# MAX2082_transceiver_V1_0.net
KiCad netlist of a schematic drawn in Altium Designer
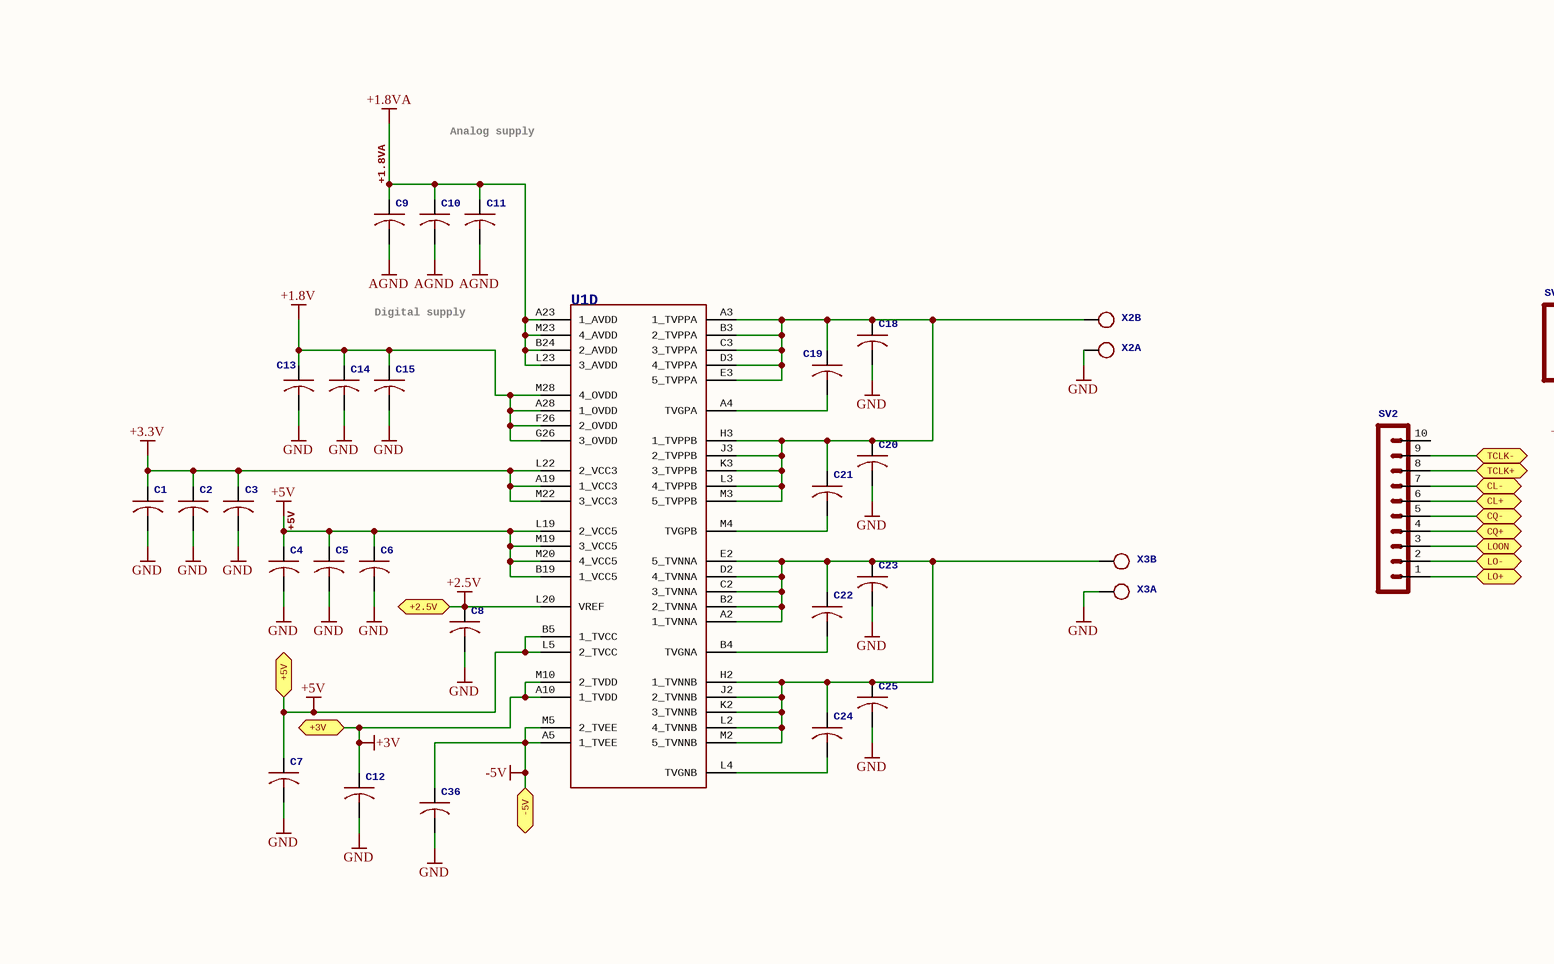
[diagram p0: MAX2082_transceiver_V1.0.SchDoc, top column 1 of 4]
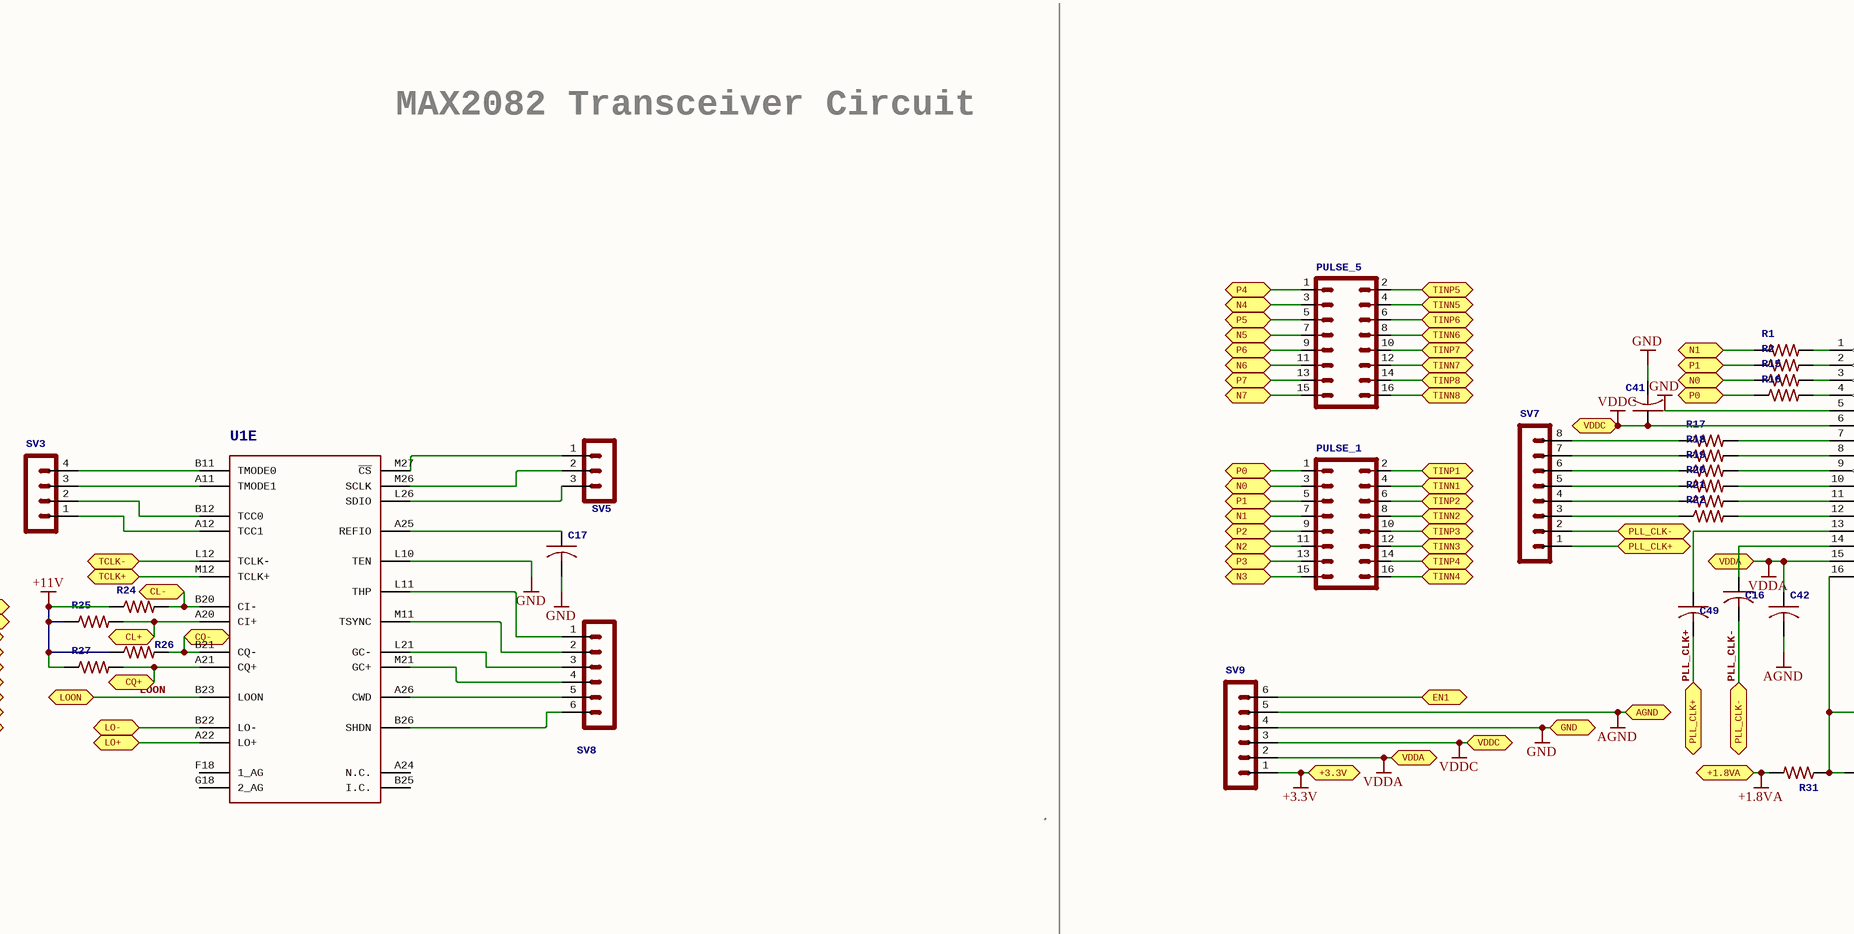
[diagram p1: MAX2082_transceiver_V1.0.SchDoc, top column 2 of 4]
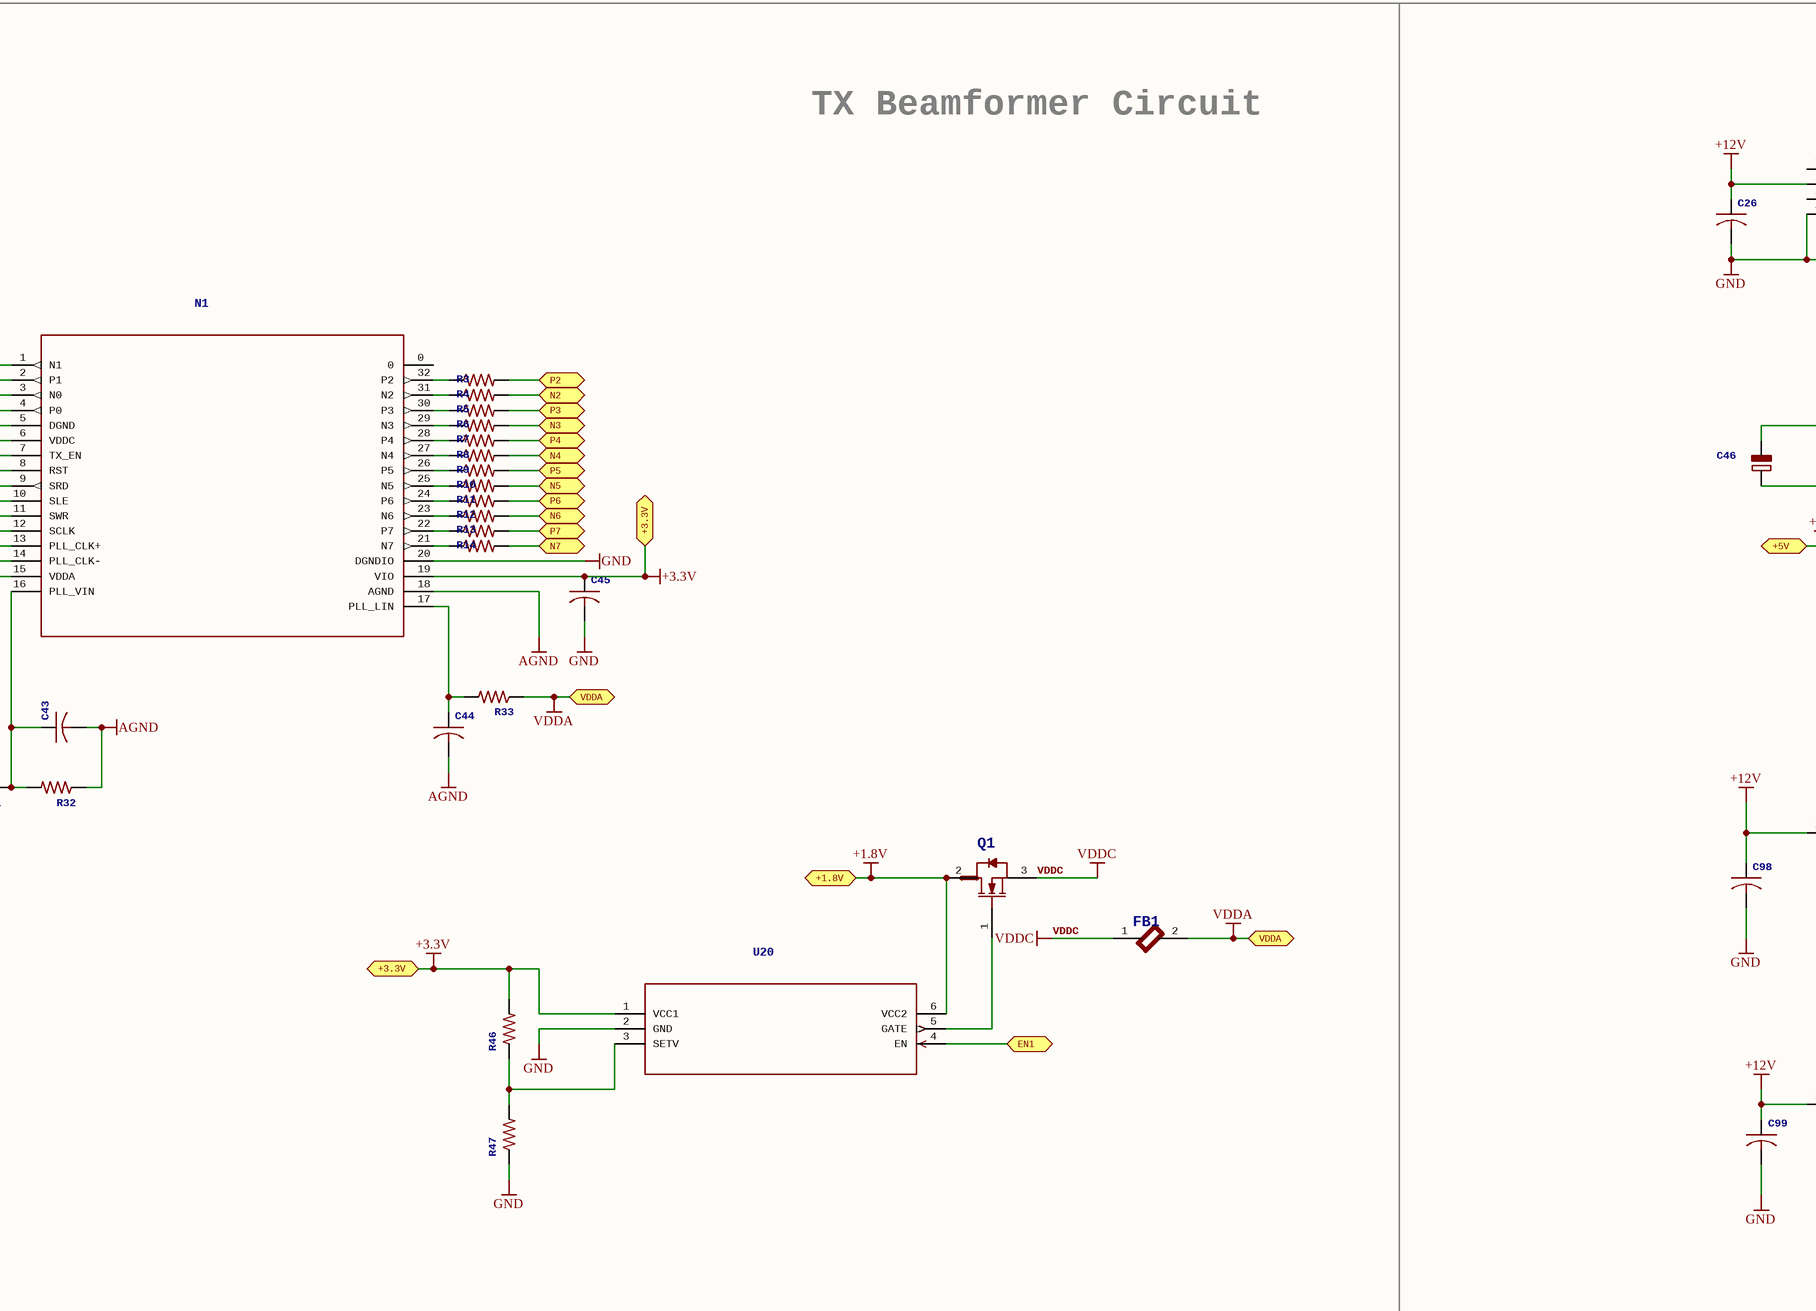
[diagram p2: MAX2082_transceiver_V1.0.SchDoc, top column 3 of 4]
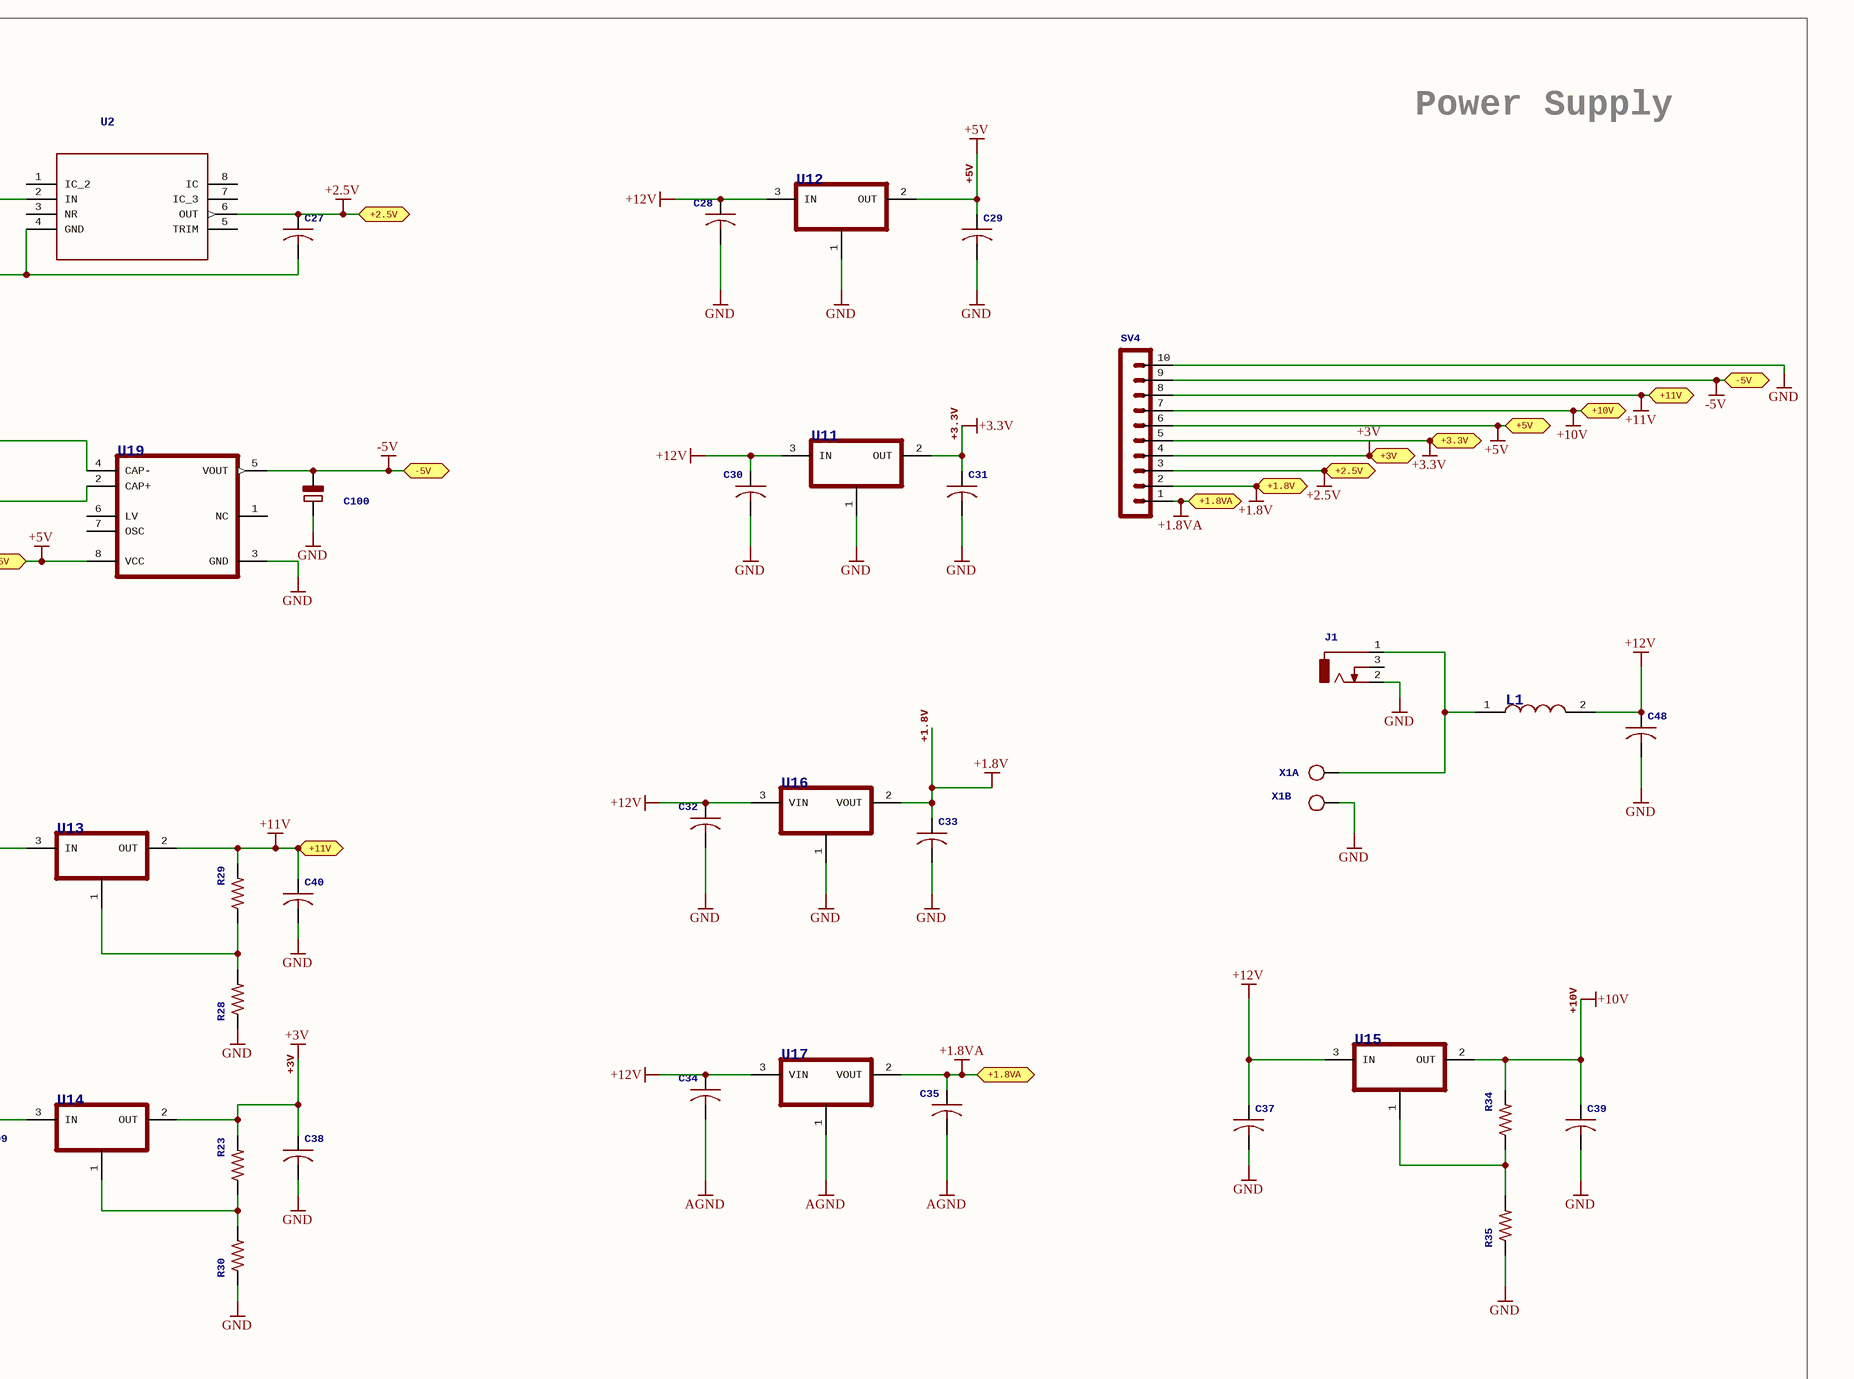
[diagram p3: MAX2082_transceiver_V1.0.SchDoc, top column 4 of 4]
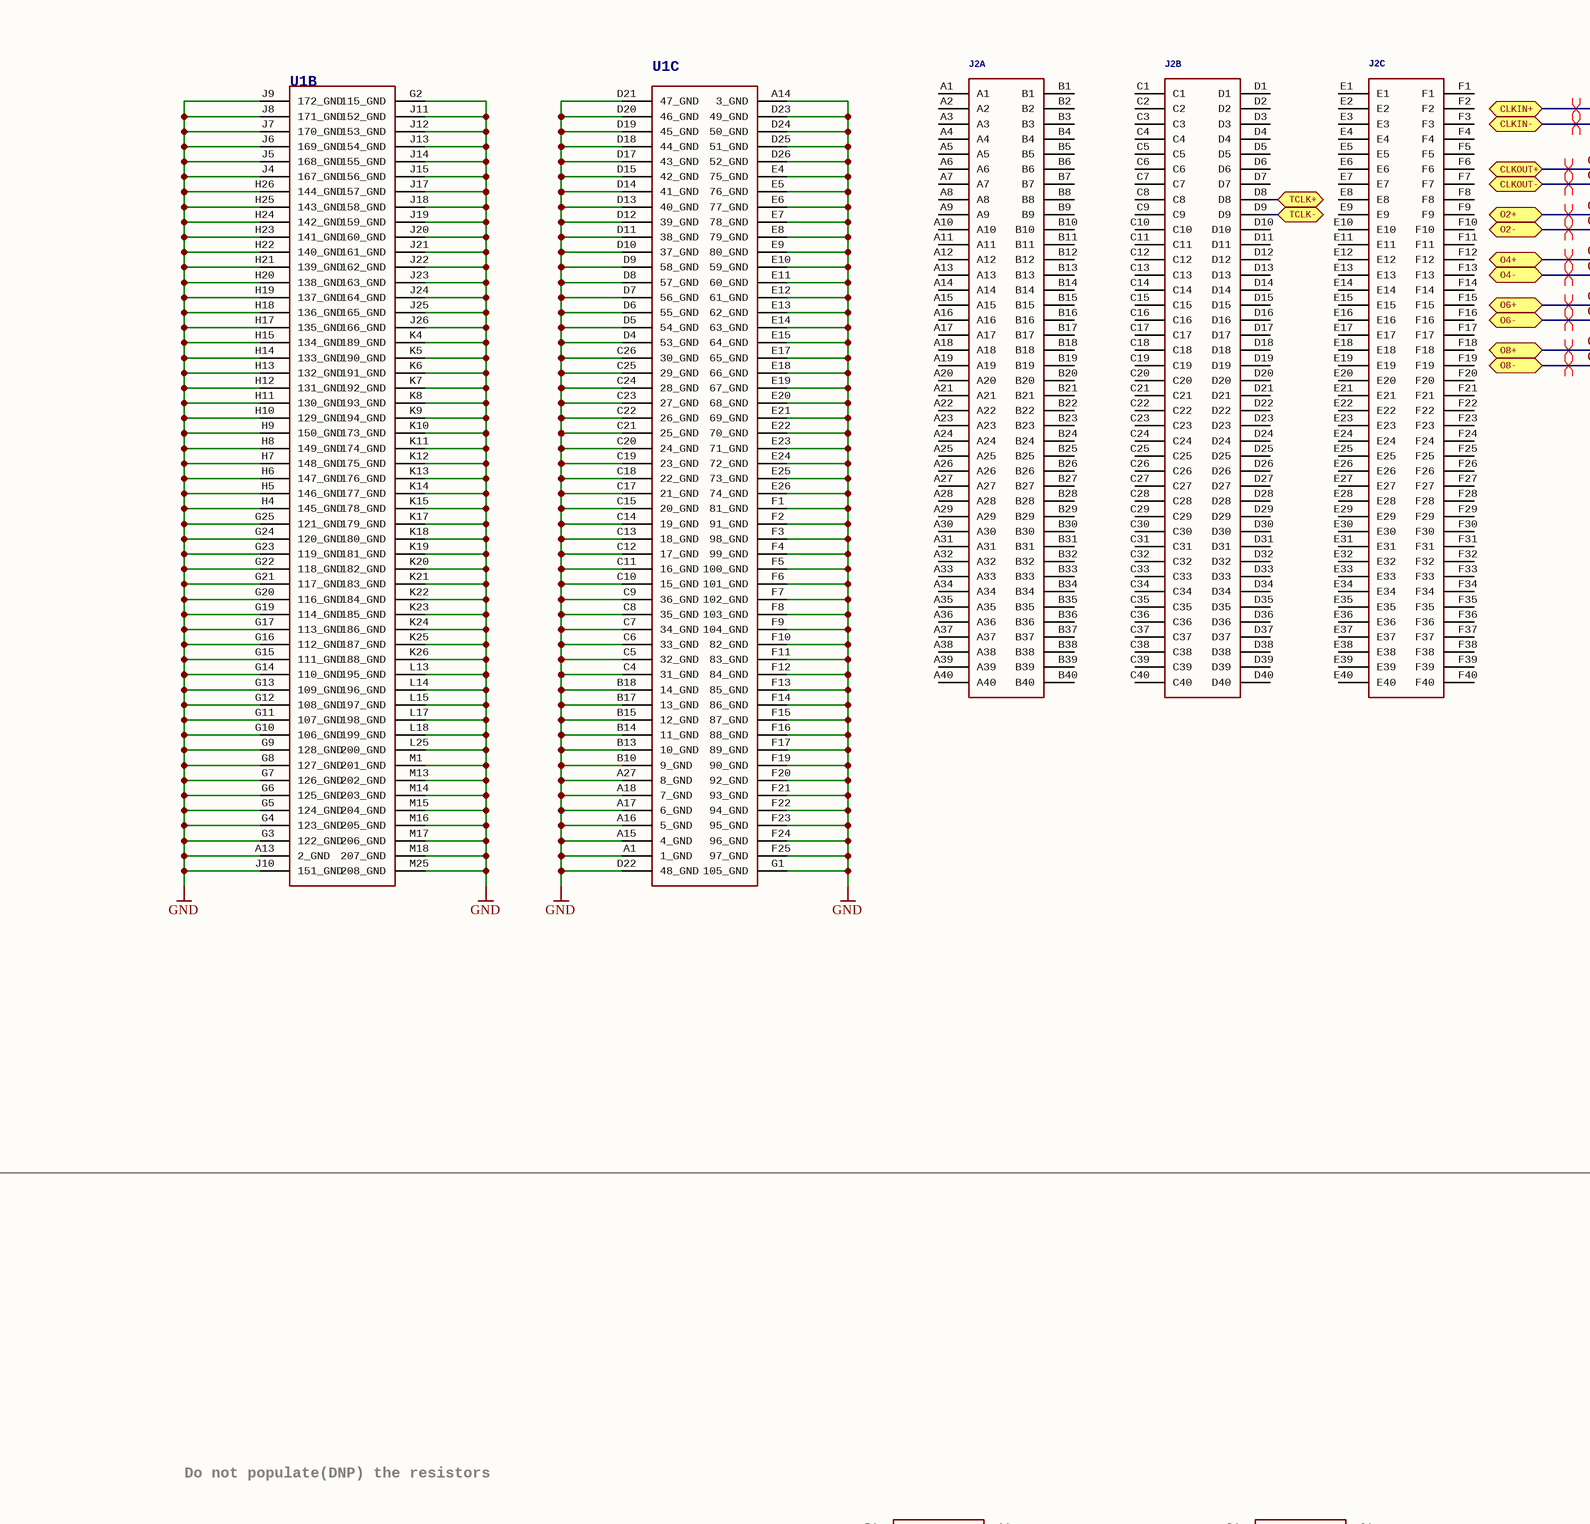
[diagram p4: MAX2082_transceiver_V1.0.SchDoc, centre column 1 of 4]
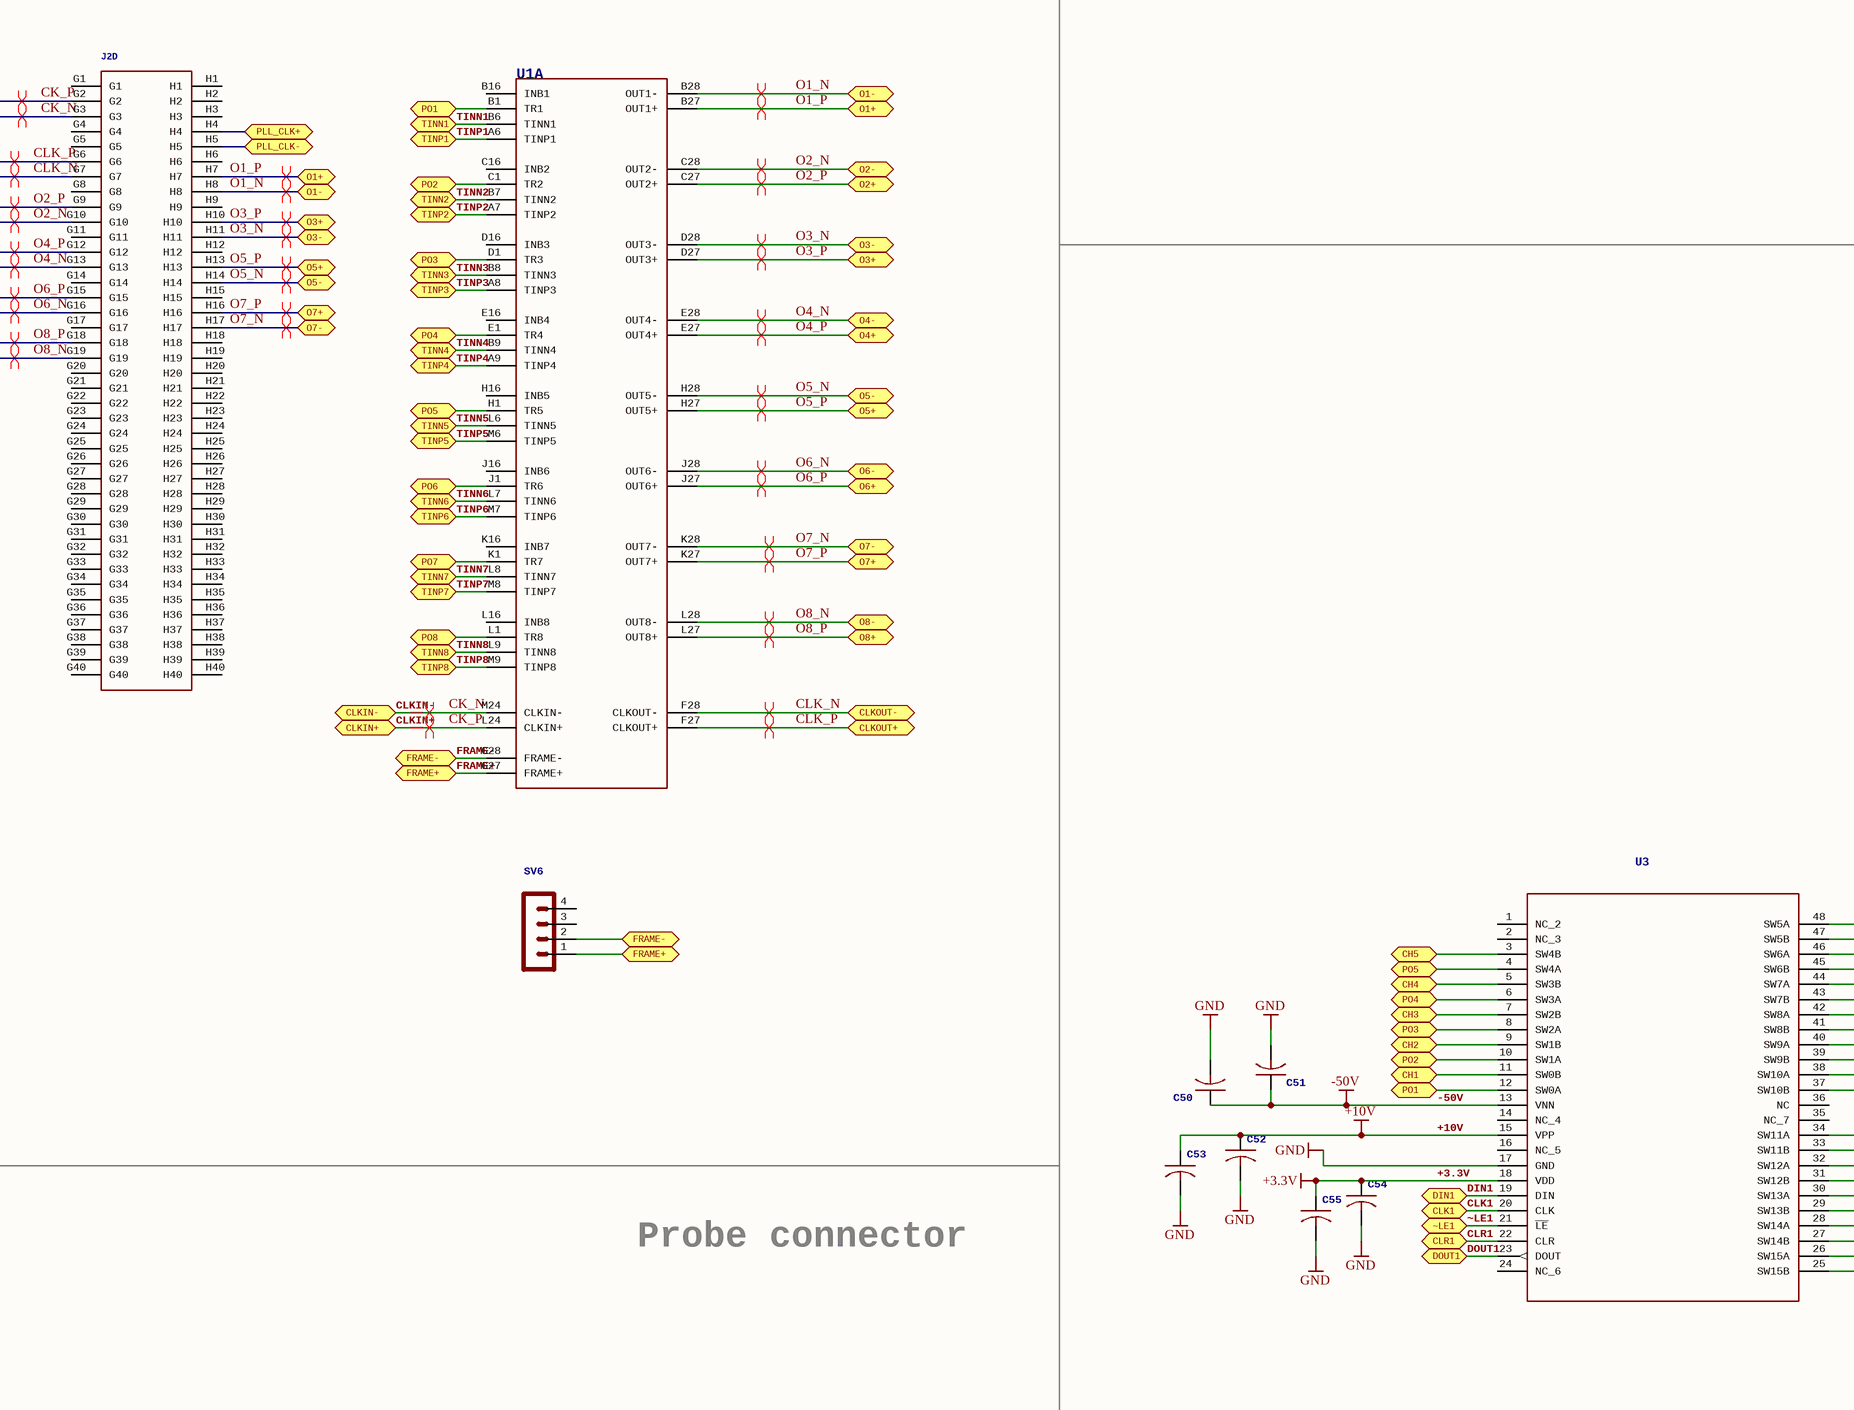
[diagram p5: MAX2082_transceiver_V1.0.SchDoc, centre column 2 of 4]
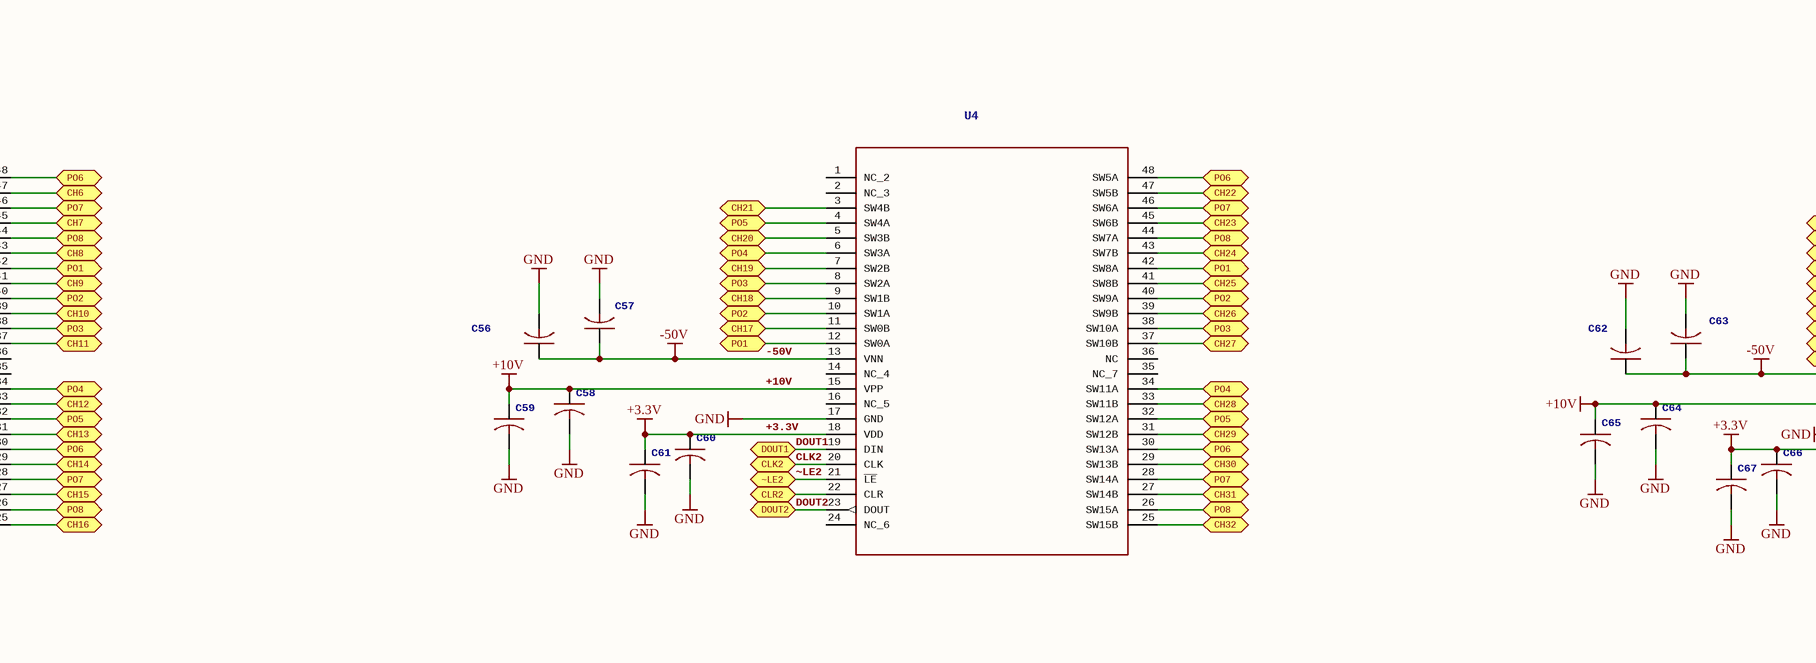
[diagram p6: MAX2082_transceiver_V1.0.SchDoc, centre column 3 of 4]
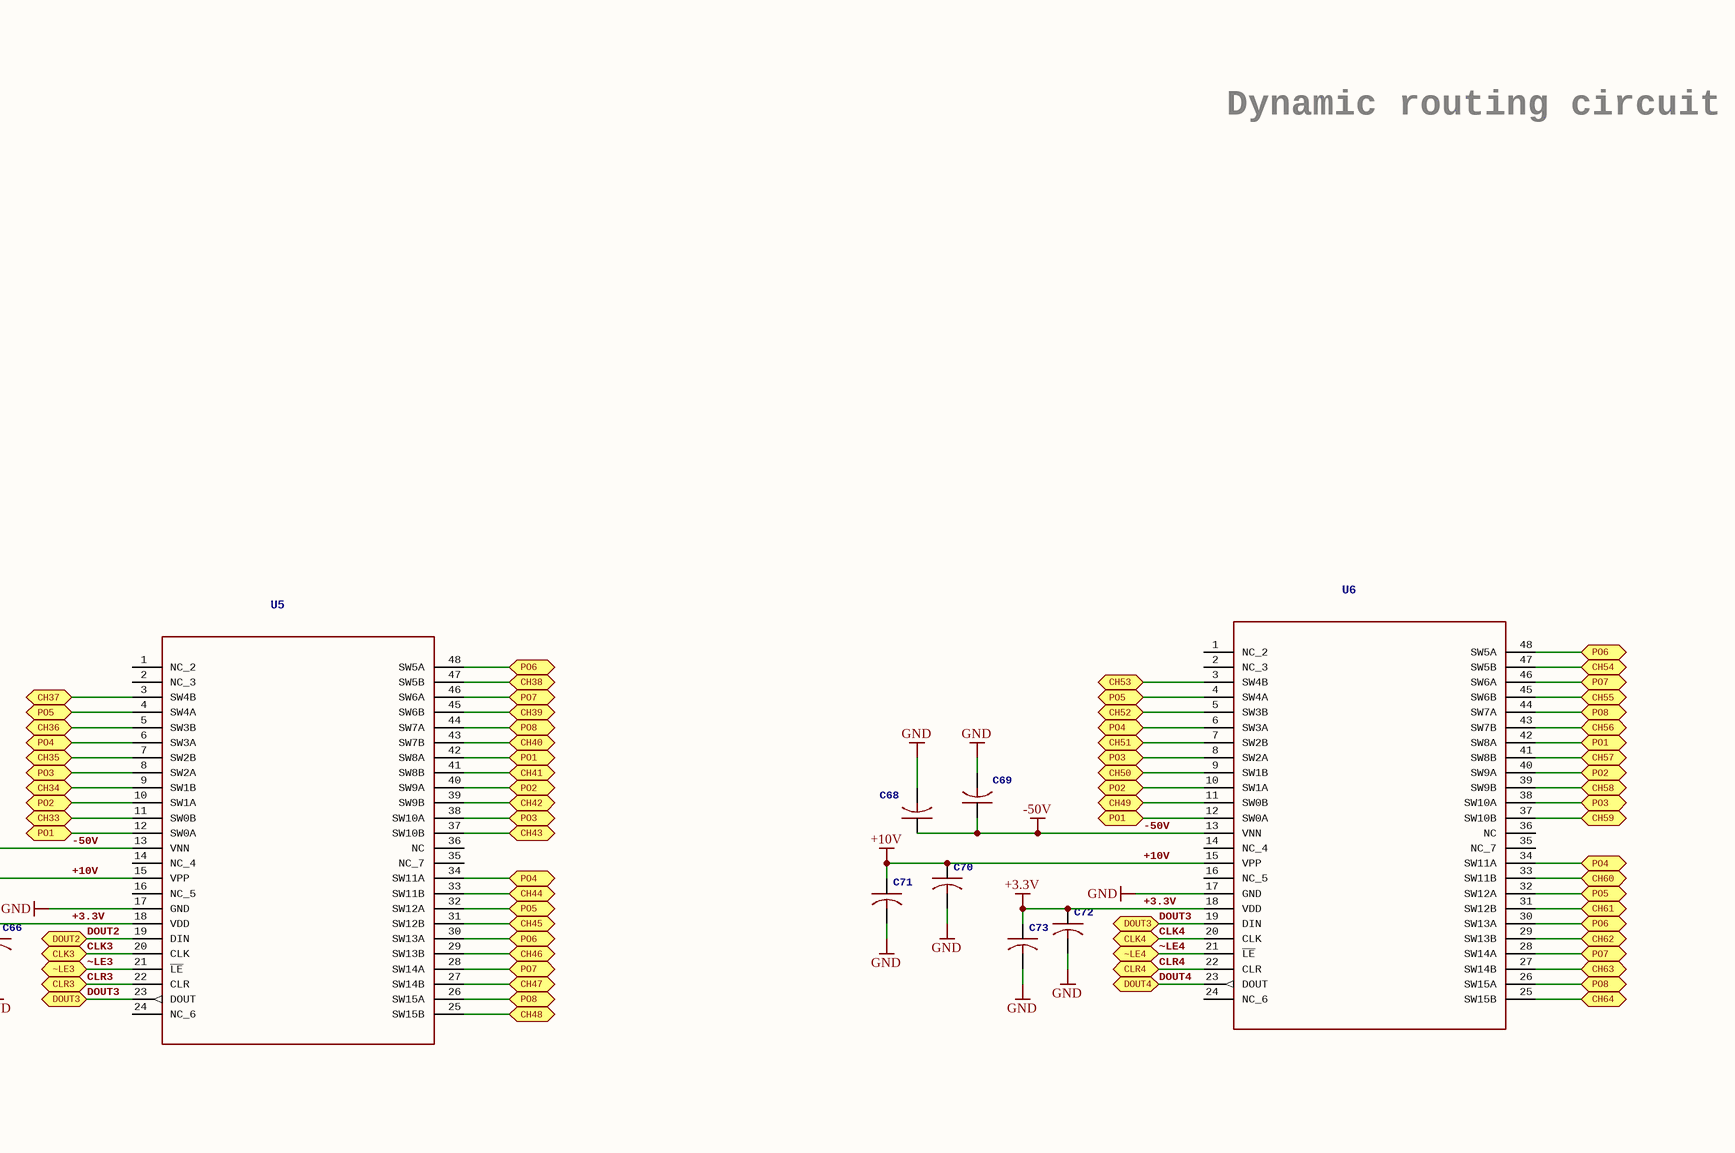
[diagram p7: MAX2082_transceiver_V1.0.SchDoc, centre column 4 of 4]
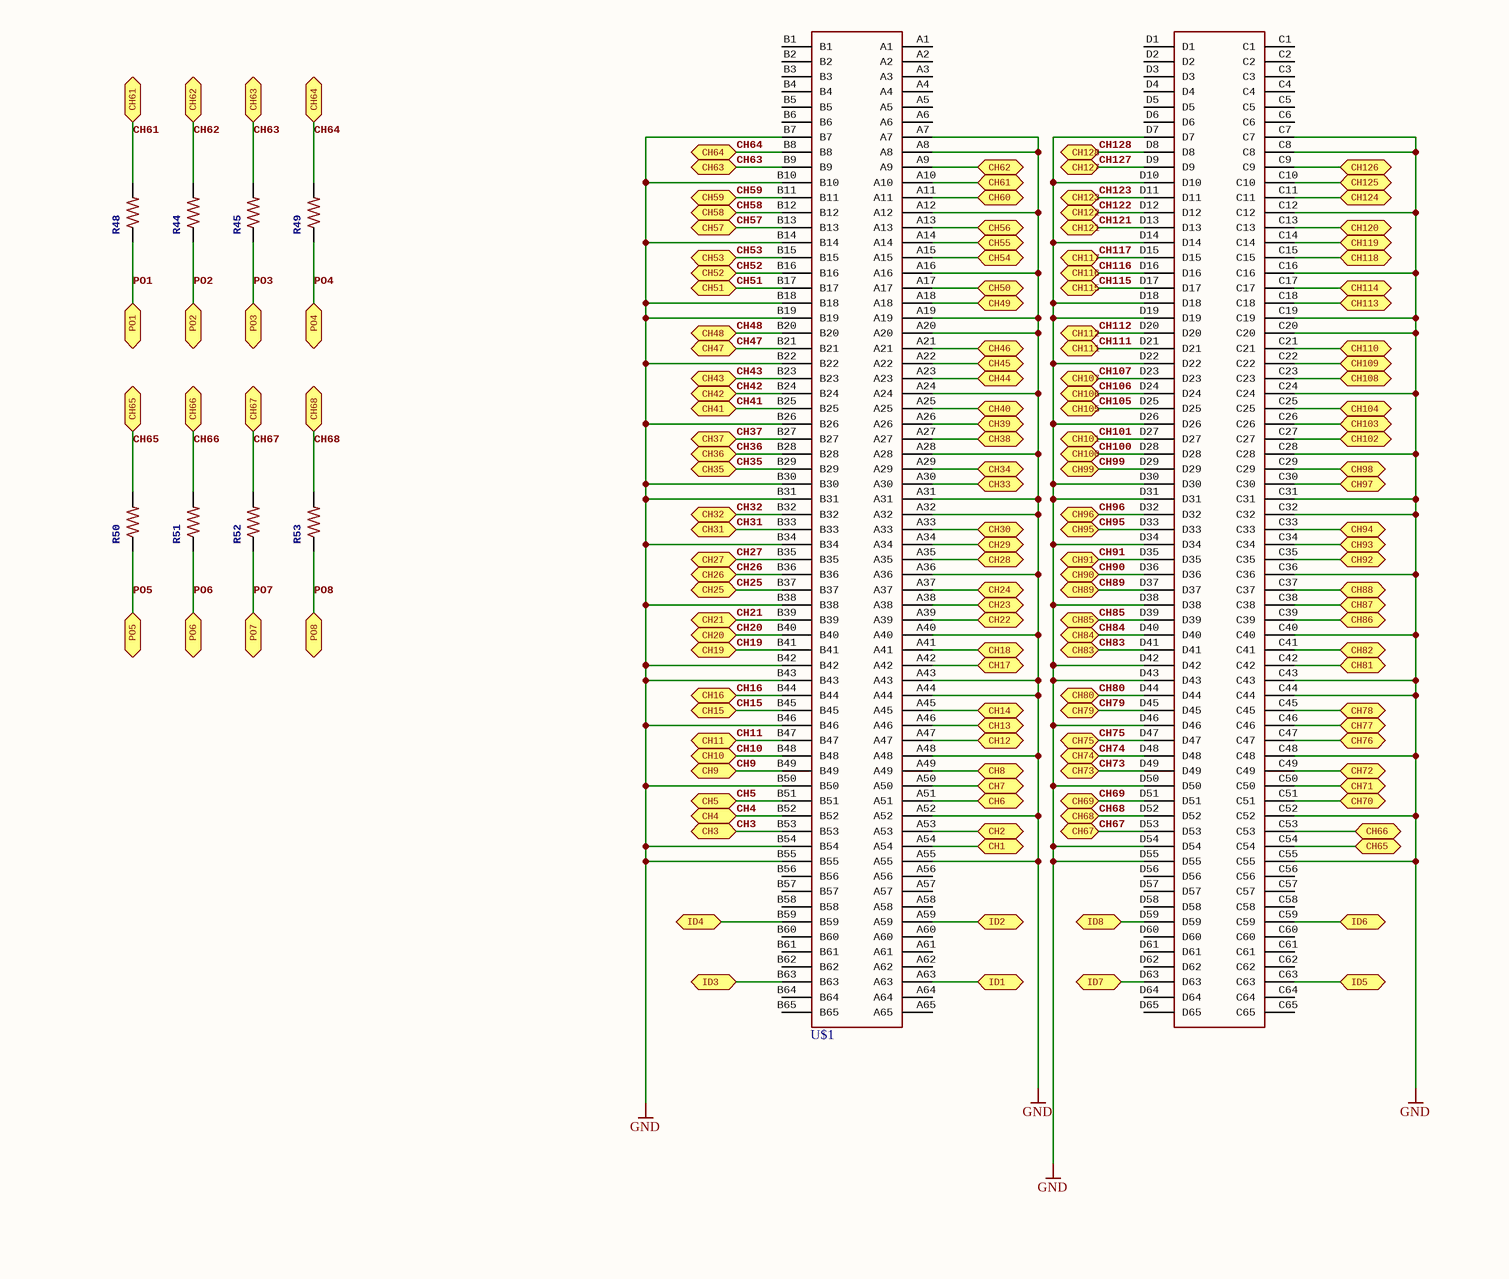
[diagram p8: MAX2082_transceiver_V1.0.SchDoc, bottom column 1 of 4]
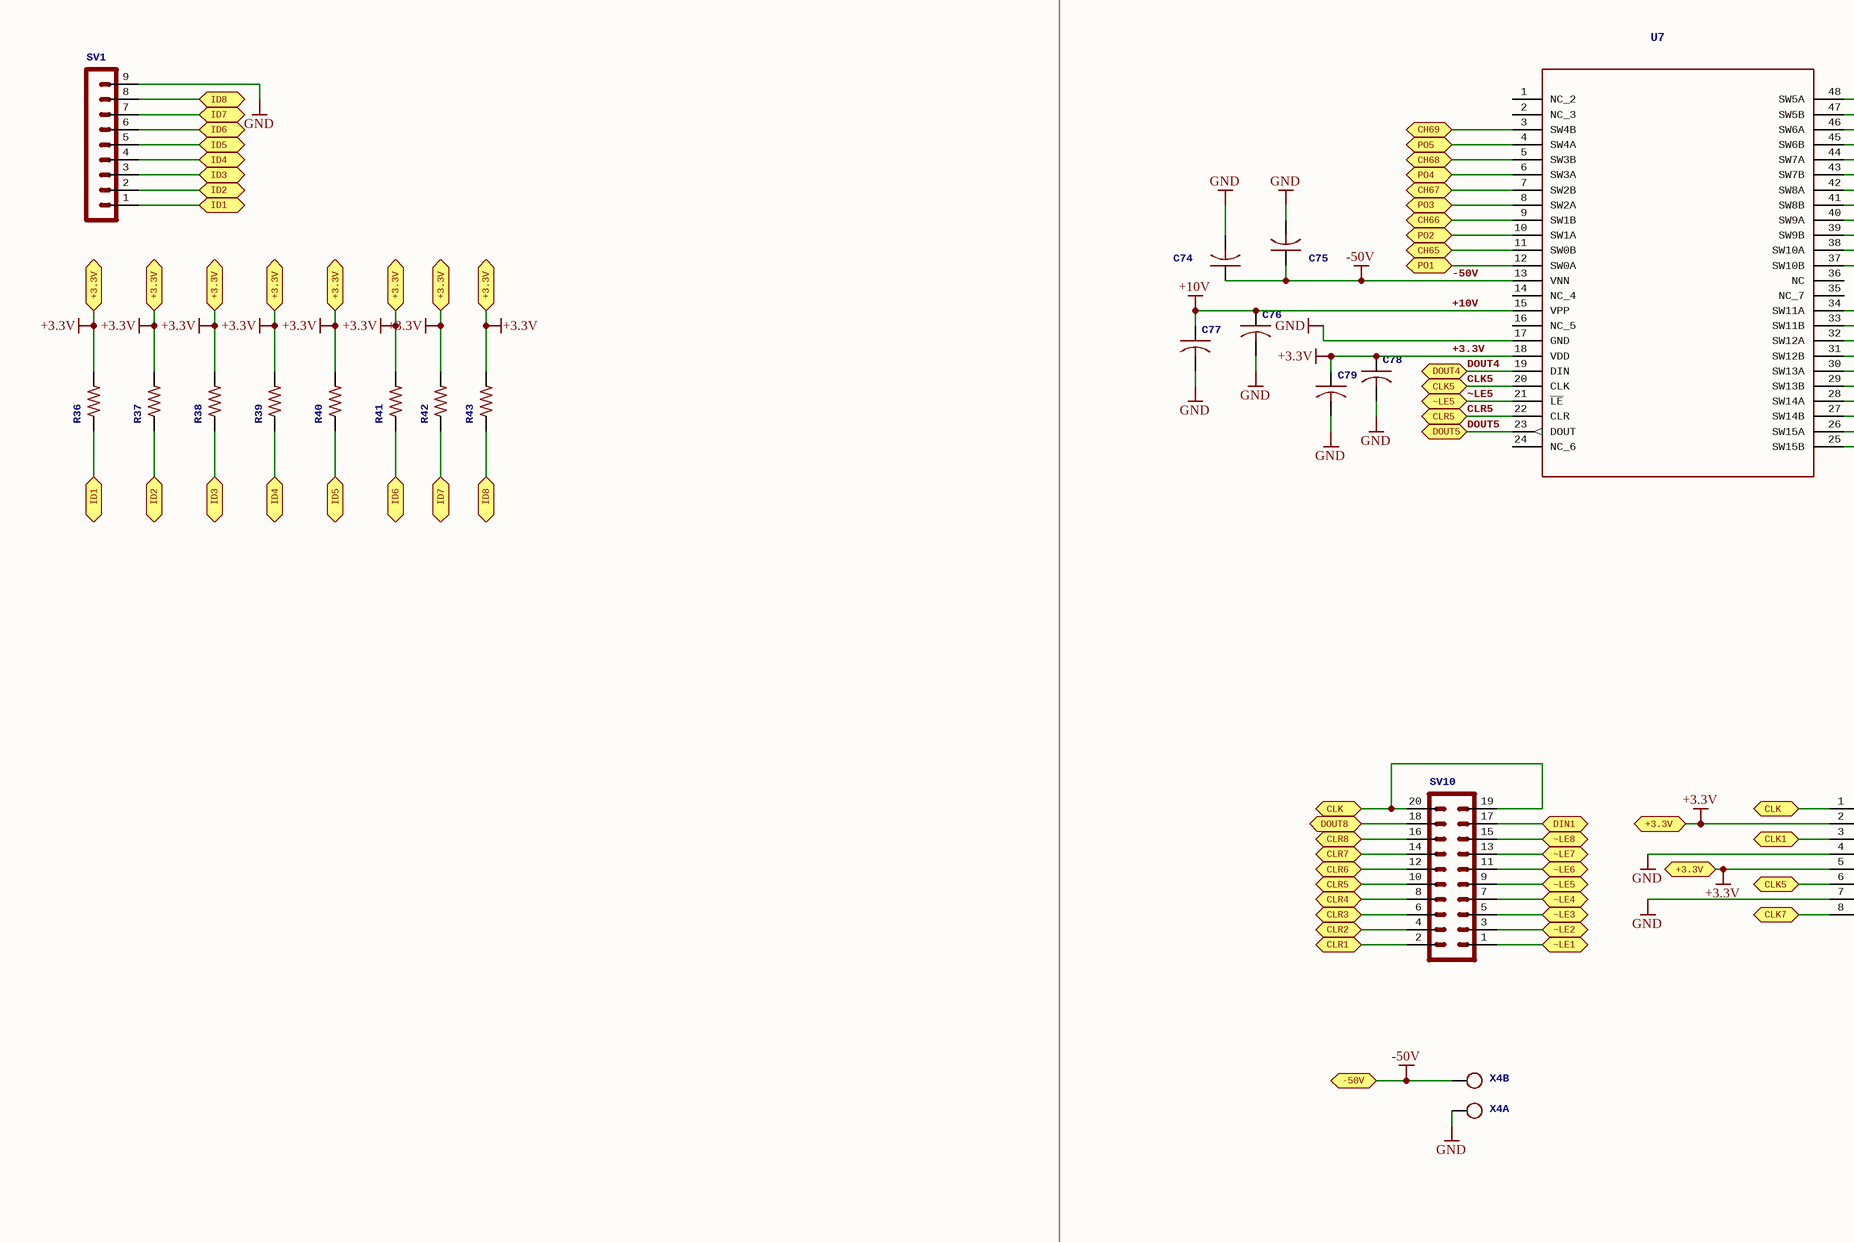
[diagram p9: MAX2082_transceiver_V1.0.SchDoc, bottom column 2 of 4]
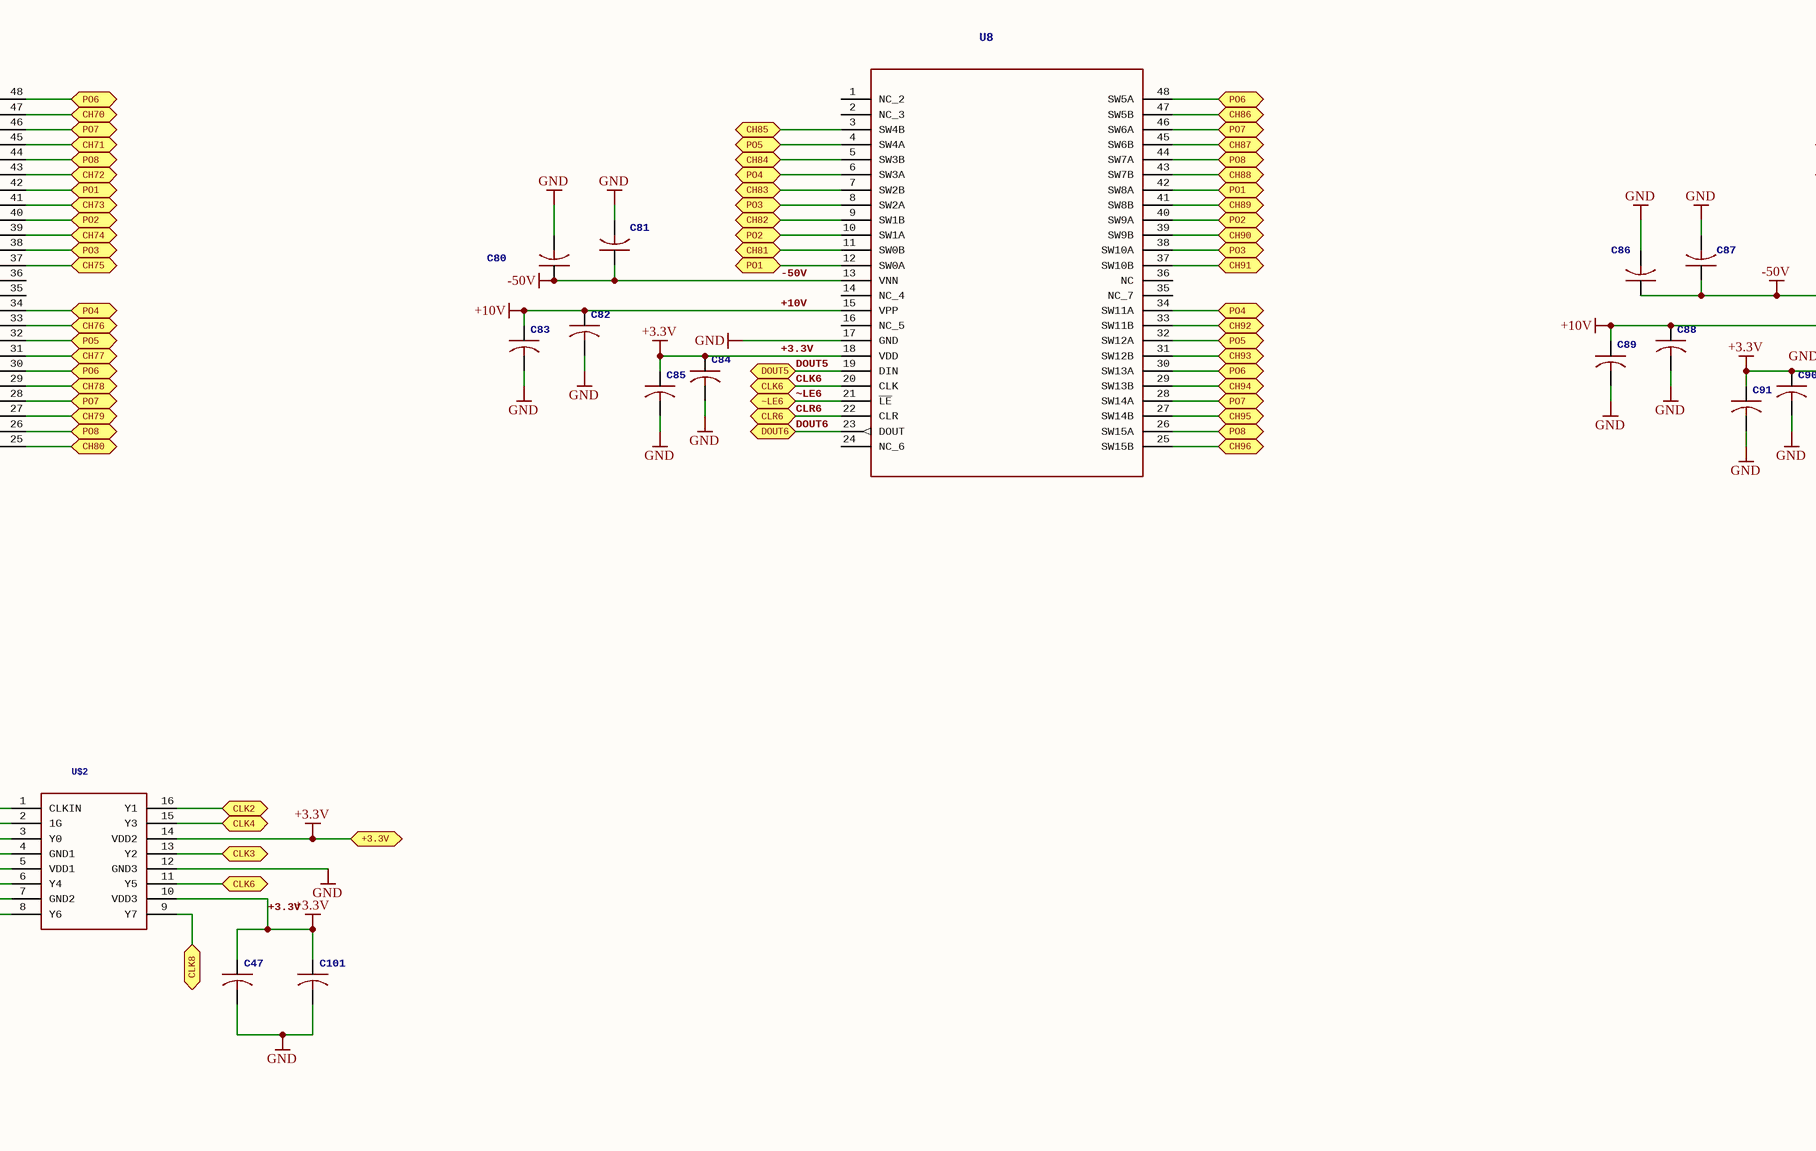
[diagram p10: MAX2082_transceiver_V1.0.SchDoc, bottom column 3 of 4]
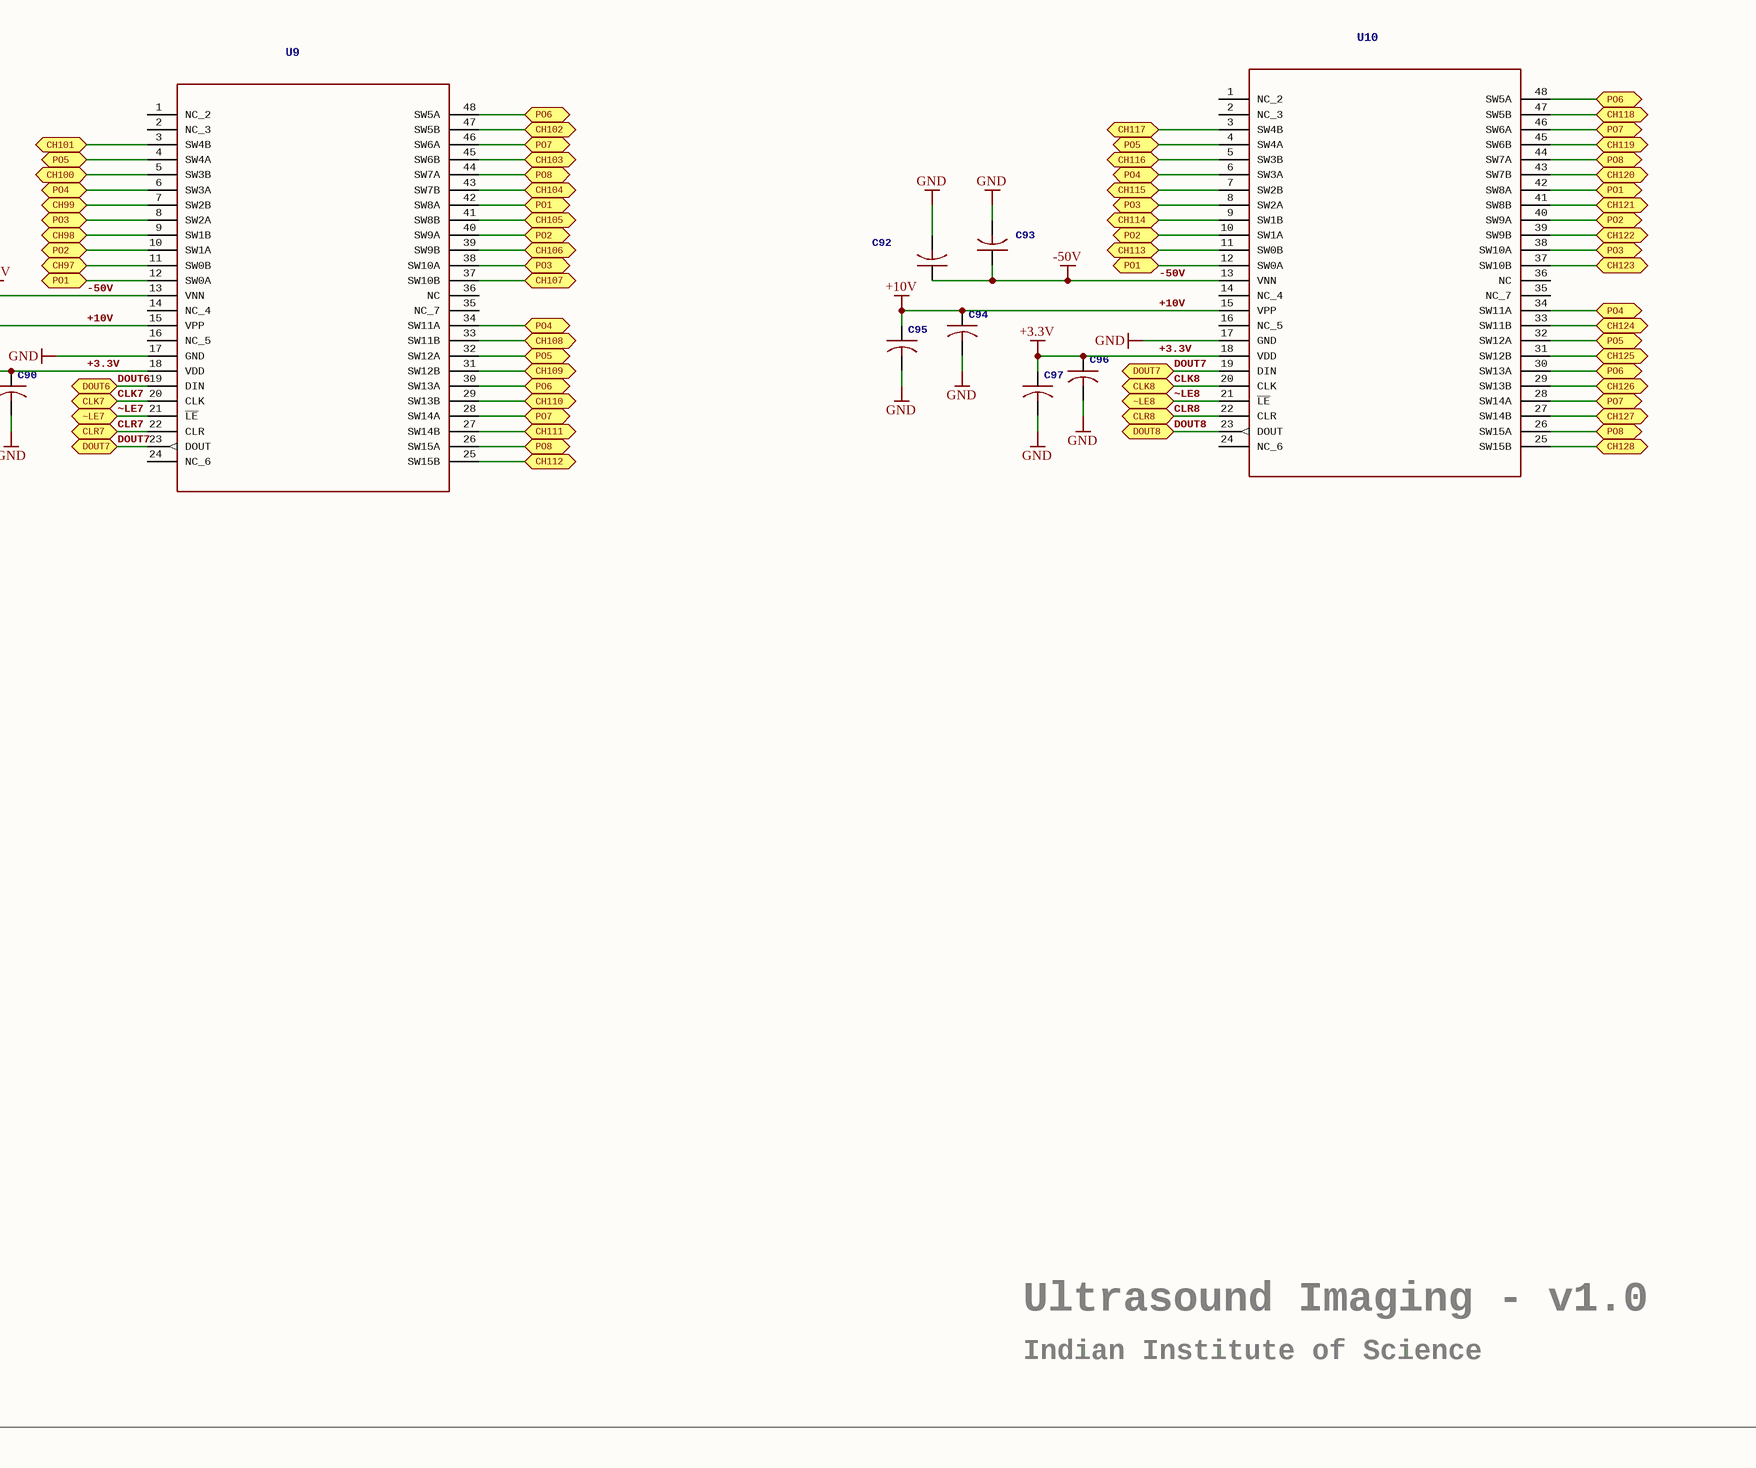
[diagram p11: MAX2082_transceiver_V1.0.SchDoc, bottom column 4 of 4]

(export (version "E")
  (design (tool "Eeschema 10.0.6"))
  (components
    (comp (ref "C1")
      (value "~")
      (footprint "C0805")
      (description "CAPACITOR, American symbol")
      (libsource (lib "rcl") (part "C-USC0805"))
    )
    (comp (ref "C2")
      (value "~")
      (footprint "C0805")
      (description "CAPACITOR, American symbol")
      (libsource (lib "rcl") (part "C-USC0805"))
    )
    (comp (ref "C3")
      (value "~")
      (footprint "C0805")
      (description "CAPACITOR, American symbol")
      (libsource (lib "rcl") (part "C-USC0805"))
    )
    (comp (ref "C4")
      (value "~")
      (footprint "C0805")
      (description "CAPACITOR, American symbol")
      (libsource (lib "rcl") (part "C-USC0805"))
    )
    (comp (ref "C5")
      (value "~")
      (footprint "C0805")
      (description "CAPACITOR, American symbol")
      (libsource (lib "rcl") (part "C-USC0805"))
    )
    (comp (ref "C6")
      (value "~")
      (footprint "C0805")
      (description "CAPACITOR, American symbol")
      (libsource (lib "rcl") (part "C-USC0805"))
    )
    (comp (ref "C7")
      (value "~")
      (footprint "C0805")
      (description "CAPACITOR, American symbol")
      (libsource (lib "rcl") (part "C-USC0805"))
    )
    (comp (ref "C8")
      (value "~")
      (footprint "C0805")
      (description "CAPACITOR, American symbol")
      (libsource (lib "rcl") (part "C-USC0805"))
    )
    (comp (ref "C9")
      (value "~")
      (footprint "C0805")
      (description "CAPACITOR, American symbol")
      (libsource (lib "rcl") (part "C-USC0805"))
    )
    (comp (ref "C10")
      (value "~")
      (footprint "C0805")
      (description "CAPACITOR, American symbol")
      (libsource (lib "rcl") (part "C-USC0805"))
    )
    (comp (ref "C11")
      (value "~")
      (footprint "C0805")
      (description "CAPACITOR, American symbol")
      (libsource (lib "rcl") (part "C-USC0805"))
    )
    (comp (ref "C12")
      (value "~")
      (footprint "C0805")
      (description "CAPACITOR, American symbol")
      (libsource (lib "rcl") (part "C-USC0805"))
    )
    (comp (ref "C13")
      (value "~")
      (footprint "C0805")
      (description "CAPACITOR, American symbol")
      (libsource (lib "rcl") (part "C-USC0805"))
    )
    (comp (ref "C14")
      (value "~")
      (footprint "C0805")
      (description "CAPACITOR, American symbol")
      (libsource (lib "rcl") (part "C-USC0805"))
    )
    (comp (ref "C15")
      (value "~")
      (footprint "C0805")
      (description "CAPACITOR, American symbol")
      (libsource (lib "rcl") (part "C-USC0805"))
    )
    (comp (ref "C16")
      (value "~")
      (footprint "C0805")
      (description "CAPACITOR, American symbol")
      (libsource (lib "rcl") (part "C-USC0805"))
    )
    (comp (ref "C17")
      (value "~")
      (footprint "C0805")
      (description "CAPACITOR, American symbol")
      (libsource (lib "rcl") (part "C-USC0805"))
    )
    (comp (ref "C18")
      (value "~")
      (footprint "C0805")
      (description "CAPACITOR, American symbol")
      (libsource (lib "rcl") (part "C-USC0805"))
    )
    (comp (ref "C19")
      (value "~")
      (footprint "C0805")
      (description "CAPACITOR, American symbol")
      (libsource (lib "rcl") (part "C-USC0805"))
    )
    (comp (ref "C20")
      (value "~")
      (footprint "C0805")
      (description "CAPACITOR, American symbol")
      (libsource (lib "rcl") (part "C-USC0805"))
    )
    (comp (ref "C21")
      (value "~")
      (footprint "C0805")
      (description "CAPACITOR, American symbol")
      (libsource (lib "rcl") (part "C-USC0805"))
    )
    (comp (ref "C22")
      (value "~")
      (footprint "C0805")
      (description "CAPACITOR, American symbol")
      (libsource (lib "rcl") (part "C-USC0805"))
    )
    (comp (ref "C23")
      (value "~")
      (footprint "C0805")
      (description "CAPACITOR, American symbol")
      (libsource (lib "rcl") (part "C-USC0805"))
    )
    (comp (ref "C24")
      (value "~")
      (footprint "C0805")
      (description "CAPACITOR, American symbol")
      (libsource (lib "rcl") (part "C-USC0805"))
    )
    (comp (ref "C25")
      (value "~")
      (footprint "C0805")
      (description "CAPACITOR, American symbol")
      (libsource (lib "rcl") (part "C-USC0805"))
    )
    (comp (ref "C26")
      (value "~")
      (footprint "C0805")
      (description "CAPACITOR, American symbol")
      (libsource (lib "rcl") (part "C-USC0805"))
    )
    (comp (ref "C27")
      (value "~")
      (footprint "C0805")
      (description "CAPACITOR, American symbol")
      (libsource (lib "rcl") (part "C-USC0805"))
    )
    (comp (ref "C28")
      (value "~")
      (footprint "C0805")
      (description "CAPACITOR, American symbol")
      (libsource (lib "") (part "C-USC0805_1"))
    )
    (comp (ref "C29")
      (value "~")
      (footprint "C0805")
      (description "CAPACITOR, American symbol")
      (libsource (lib "rcl") (part "C-USC0805"))
    )
    (comp (ref "C30")
      (value "~")
      (footprint "C0805")
      (description "CAPACITOR, American symbol")
      (libsource (lib "") (part "C-USC0805_1"))
    )
    (comp (ref "C31")
      (value "~")
      (footprint "C0805")
      (description "CAPACITOR, American symbol")
      (libsource (lib "rcl") (part "C-USC0805"))
    )
    (comp (ref "C32")
      (value "~")
      (footprint "C0805")
      (description "CAPACITOR, American symbol")
      (libsource (lib "") (part "C-USC0805_1"))
    )
    (comp (ref "C33")
      (value "~")
      (footprint "C0805")
      (description "CAPACITOR, American symbol")
      (libsource (lib "rcl") (part "C-USC0805"))
    )
    (comp (ref "C34")
      (value "~")
      (footprint "C0805")
      (description "CAPACITOR, American symbol")
      (libsource (lib "") (part "C-USC0805_1"))
    )
    (comp (ref "C35")
      (value "~")
      (footprint "C0805")
      (description "CAPACITOR, American symbol")
      (libsource (lib "") (part "C-USC0805_1"))
    )
    (comp (ref "C36")
      (value "~")
      (footprint "C0805")
      (description "CAPACITOR, American symbol")
      (libsource (lib "rcl") (part "C-USC0805"))
    )
    (comp (ref "C37")
      (value "~")
      (footprint "C0805")
      (description "CAPACITOR, American symbol")
      (libsource (lib "rcl") (part "C-USC0805"))
    )
    (comp (ref "C38")
      (value "~")
      (footprint "C0805")
      (description "CAPACITOR, American symbol")
      (libsource (lib "rcl") (part "C-USC0805"))
    )
    (comp (ref "C39")
      (value "~")
      (footprint "C0805")
      (description "CAPACITOR, American symbol")
      (libsource (lib "rcl") (part "C-USC0805"))
    )
    (comp (ref "C40")
      (value "~")
      (footprint "C0805")
      (description "CAPACITOR, American symbol")
      (libsource (lib "rcl") (part "C-USC0805"))
    )
    (comp (ref "C41")
      (value "~")
      (footprint "C0805")
      (description "CAPACITOR, American symbol")
      (libsource (lib "rcl") (part "C-USC0805"))
    )
    (comp (ref "C42")
      (value "~")
      (footprint "C0805")
      (description "CAPACITOR, American symbol")
      (libsource (lib "rcl") (part "C-USC0805"))
    )
    (comp (ref "C43")
      (value "~")
      (footprint "C0805")
      (description "CAPACITOR, American symbol")
      (libsource (lib "rcl") (part "C-USC0805"))
    )
    (comp (ref "C44")
      (value "~")
      (footprint "C0805")
      (description "CAPACITOR, American symbol")
      (libsource (lib "rcl") (part "C-USC0805"))
    )
    (comp (ref "C45")
      (value "~")
      (footprint "C0805")
      (description "CAPACITOR, American symbol")
      (libsource (lib "rcl") (part "C-USC0805"))
    )
    (comp (ref "C46")
      (value "~")
      (footprint "C46,C100")
      (description "POLARIZED CAPACITOR, European symbol")
      (libsource (lib "rcl") (part "CPOL-EUE2.5-6"))
    )
    (comp (ref "C47")
      (value "~")
      (footprint "C0805")
      (description "CAPACITOR, American symbol")
      (libsource (lib "rcl") (part "C-USC0805"))
    )
    (comp (ref "C48")
      (value "~")
      (footprint "C0805")
      (description "CAPACITOR, American symbol")
      (libsource (lib "rcl") (part "C-USC0805"))
    )
    (comp (ref "C49")
      (value "~")
      (footprint "C0805")
      (description "CAPACITOR, American symbol")
      (libsource (lib "rcl") (part "C-USC0805"))
    )
    (comp (ref "C50")
      (value "~")
      (footprint "C0805")
      (description "CAPACITOR, American symbol")
      (libsource (lib "rcl") (part "C-USC0805"))
    )
    (comp (ref "C51")
      (value "~")
      (footprint "C0805")
      (description "CAPACITOR, American symbol")
      (libsource (lib "rcl") (part "C-USC0805"))
    )
    (comp (ref "C52")
      (value "~")
      (footprint "C0805")
      (description "CAPACITOR, American symbol")
      (libsource (lib "rcl") (part "C-USC0805"))
    )
    (comp (ref "C53")
      (value "~")
      (footprint "C0805")
      (description "CAPACITOR, American symbol")
      (libsource (lib "rcl") (part "C-USC0805"))
    )
    (comp (ref "C54")
      (value "~")
      (footprint "C0805")
      (description "CAPACITOR, American symbol")
      (libsource (lib "rcl") (part "C-USC0805"))
    )
    (comp (ref "C55")
      (value "~")
      (footprint "C0805")
      (description "CAPACITOR, American symbol")
      (libsource (lib "rcl") (part "C-USC0805"))
    )
    (comp (ref "C56")
      (value "~")
      (footprint "C0805")
      (description "CAPACITOR, American symbol")
      (libsource (lib "rcl") (part "C-USC0805"))
    )
    (comp (ref "C57")
      (value "~")
      (footprint "C0805")
      (description "CAPACITOR, American symbol")
      (libsource (lib "rcl") (part "C-USC0805"))
    )
    (comp (ref "C58")
      (value "~")
      (footprint "C0805")
      (description "CAPACITOR, American symbol")
      (libsource (lib "rcl") (part "C-USC0805"))
    )
    (comp (ref "C59")
      (value "~")
      (footprint "C0805")
      (description "CAPACITOR, American symbol")
      (libsource (lib "rcl") (part "C-USC0805"))
    )
    (comp (ref "C60")
      (value "~")
      (footprint "C0805")
      (description "CAPACITOR, American symbol")
      (libsource (lib "rcl") (part "C-USC0805"))
    )
    (comp (ref "C61")
      (value "~")
      (footprint "C0805")
      (description "CAPACITOR, American symbol")
      (libsource (lib "rcl") (part "C-USC0805"))
    )
    (comp (ref "C62")
      (value "~")
      (footprint "C0805")
      (description "CAPACITOR, American symbol")
      (libsource (lib "rcl") (part "C-USC0805"))
    )
    (comp (ref "C63")
      (value "~")
      (footprint "C0805")
      (description "CAPACITOR, American symbol")
      (libsource (lib "rcl") (part "C-USC0805"))
    )
    (comp (ref "C64")
      (value "~")
      (footprint "C0805")
      (description "CAPACITOR, American symbol")
      (libsource (lib "rcl") (part "C-USC0805"))
    )
    (comp (ref "C65")
      (value "~")
      (footprint "C0805")
      (description "CAPACITOR, American symbol")
      (libsource (lib "rcl") (part "C-USC0805"))
    )
    (comp (ref "C66")
      (value "~")
      (footprint "C0805")
      (description "CAPACITOR, American symbol")
      (libsource (lib "rcl") (part "C-USC0805"))
    )
    (comp (ref "C67")
      (value "~")
      (footprint "C0805")
      (description "CAPACITOR, American symbol")
      (libsource (lib "rcl") (part "C-USC0805"))
    )
    (comp (ref "C68")
      (value "~")
      (footprint "C0805")
      (description "CAPACITOR, American symbol")
      (libsource (lib "rcl") (part "C-USC0805"))
    )
    (comp (ref "C69")
      (value "~")
      (footprint "C0805")
      (description "CAPACITOR, American symbol")
      (libsource (lib "rcl") (part "C-USC0805"))
    )
    (comp (ref "C70")
      (value "~")
      (footprint "C0805")
      (description "CAPACITOR, American symbol")
      (libsource (lib "rcl") (part "C-USC0805"))
    )
    (comp (ref "C71")
      (value "~")
      (footprint "C0805")
      (description "CAPACITOR, American symbol")
      (libsource (lib "rcl") (part "C-USC0805"))
    )
    (comp (ref "C72")
      (value "~")
      (footprint "C0805")
      (description "CAPACITOR, American symbol")
      (libsource (lib "rcl") (part "C-USC0805"))
    )
    (comp (ref "C73")
      (value "~")
      (footprint "C0805")
      (description "CAPACITOR, American symbol")
      (libsource (lib "rcl") (part "C-USC0805"))
    )
    (comp (ref "C74")
      (value "~")
      (footprint "C0805")
      (description "CAPACITOR, American symbol")
      (libsource (lib "rcl") (part "C-USC0805"))
    )
    (comp (ref "C75")
      (value "~")
      (footprint "C0805")
      (description "CAPACITOR, American symbol")
      (libsource (lib "rcl") (part "C-USC0805"))
    )
    (comp (ref "C76")
      (value "~")
      (footprint "C0805")
      (description "CAPACITOR, American symbol")
      (libsource (lib "rcl") (part "C-USC0805"))
    )
    (comp (ref "C77")
      (value "~")
      (footprint "C0805")
      (description "CAPACITOR, American symbol")
      (libsource (lib "rcl") (part "C-USC0805"))
    )
    (comp (ref "C78")
      (value "~")
      (footprint "C0805")
      (description "CAPACITOR, American symbol")
      (libsource (lib "rcl") (part "C-USC0805"))
    )
    (comp (ref "C79")
      (value "~")
      (footprint "C0805")
      (description "CAPACITOR, American symbol")
      (libsource (lib "rcl") (part "C-USC0805"))
    )
    (comp (ref "C80")
      (value "~")
      (footprint "C0805")
      (description "CAPACITOR, American symbol")
      (libsource (lib "rcl") (part "C-USC0805"))
    )
    (comp (ref "C81")
      (value "~")
      (footprint "C0805")
      (description "CAPACITOR, American symbol")
      (libsource (lib "rcl") (part "C-USC0805"))
    )
    (comp (ref "C82")
      (value "~")
      (footprint "C0805")
      (description "CAPACITOR, American symbol")
      (libsource (lib "rcl") (part "C-USC0805"))
    )
    (comp (ref "C83")
      (value "~")
      (footprint "C0805")
      (description "CAPACITOR, American symbol")
      (libsource (lib "rcl") (part "C-USC0805"))
    )
    (comp (ref "C84")
      (value "~")
      (footprint "C0805")
      (description "CAPACITOR, American symbol")
      (libsource (lib "rcl") (part "C-USC0805"))
    )
    (comp (ref "C85")
      (value "~")
      (footprint "C0805")
      (description "CAPACITOR, American symbol")
      (libsource (lib "rcl") (part "C-USC0805"))
    )
    (comp (ref "C86")
      (value "~")
      (footprint "C0805")
      (description "CAPACITOR, American symbol")
      (libsource (lib "rcl") (part "C-USC0805"))
    )
    (comp (ref "C87")
      (value "~")
      (footprint "C0805")
      (description "CAPACITOR, American symbol")
      (libsource (lib "rcl") (part "C-USC0805"))
    )
    (comp (ref "C88")
      (value "~")
      (footprint "C0805")
      (description "CAPACITOR, American symbol")
      (libsource (lib "rcl") (part "C-USC0805"))
    )
    (comp (ref "C89")
      (value "~")
      (footprint "C0805")
      (description "CAPACITOR, American symbol")
      (libsource (lib "rcl") (part "C-USC0805"))
    )
    (comp (ref "C90")
      (value "~")
      (footprint "C0805")
      (description "CAPACITOR, American symbol")
      (libsource (lib "rcl") (part "C-USC0805"))
    )
    (comp (ref "C91")
      (value "~")
      (footprint "C0805")
      (description "CAPACITOR, American symbol")
      (libsource (lib "rcl") (part "C-USC0805"))
    )
    (comp (ref "C92")
      (value "~")
      (footprint "C0805")
      (description "CAPACITOR, American symbol")
      (libsource (lib "rcl") (part "C-USC0805"))
    )
    (comp (ref "C93")
      (value "~")
      (footprint "C0805")
      (description "CAPACITOR, American symbol")
      (libsource (lib "rcl") (part "C-USC0805"))
    )
    (comp (ref "C94")
      (value "~")
      (footprint "C0805")
      (description "CAPACITOR, American symbol")
      (libsource (lib "rcl") (part "C-USC0805"))
    )
    (comp (ref "C95")
      (value "~")
      (footprint "C0805")
      (description "CAPACITOR, American symbol")
      (libsource (lib "rcl") (part "C-USC0805"))
    )
    (comp (ref "C96")
      (value "~")
      (footprint "C0805")
      (description "CAPACITOR, American symbol")
      (libsource (lib "rcl") (part "C-USC0805"))
    )
    (comp (ref "C97")
      (value "~")
      (footprint "C0805")
      (description "CAPACITOR, American symbol")
      (libsource (lib "rcl") (part "C-USC0805"))
    )
    (comp (ref "C98")
      (value "~")
      (footprint "C0805")
      (description "CAPACITOR, American symbol")
      (libsource (lib "rcl") (part "C-USC0805"))
    )
    (comp (ref "C99")
      (value "~")
      (footprint "C0805")
      (description "CAPACITOR, American symbol")
      (libsource (lib "rcl") (part "C-USC0805"))
    )
    (comp (ref "C100")
      (value "~")
      (footprint "C46,C100")
      (description "POLARIZED CAPACITOR, European symbol")
      (libsource (lib "rcl") (part "CPOL-EUE2.5-6"))
    )
    (comp (ref "C101")
      (value "~")
      (footprint "C0805")
      (description "CAPACITOR, American symbol")
      (libsource (lib "rcl") (part "C-USC0805"))
    )
    (comp (ref "FB1")
      (value "~")
      (footprint "FB1")
      (description "Chip bead for power line")
      (libsource (lib "TDK - MPZ1608S101ATAH0") (part "TDK_MPZ1608S101ATAH0TDK_MPZ1608S101ATAH0_0_0"))
    )
    (comp (ref "J1")
      (value "~")
      (footprint "J1")
      (description "DC POWER JACK   Source: DCJ0202.pdf")
      (libsource (lib "con-jack") (part "DCJ0202"))
    )
    (comp (ref "J2")
      (value "~")
      (footprint "J2")
      (description "Board-To-Board Connector, Vita 57 XMC, ASP Series, Surface Mount, Header, 400, 1.27 mm")
      (libsource (lib "ASP-134488-01") (part "ASP-134488-01"))
    )
    (comp (ref "L1")
      (value "~")
      (footprint "L1              0805")
      (description "PAS-IND-INDUCTOR-2")
      (libsource (lib "Wurth Electronics - 742792031") (part "WURTH_ELECTRONICS_742792031WURTH_ELECTRONICS_742792031_0_0"))
    )
    (comp (ref "N1") (value "~") (footprint "N1") (libsource (lib "LM96570") (part "LM96570SQE/NOPB")))
    (comp (ref "PULSE_1")
      (value "~")
      (footprint "PULSE_1,PULSE_5")
      (description "JUMPER")
      (libsource (lib "jumper") (part "JP8Q"))
    )
    (comp (ref "PULSE_5")
      (value "~")
      (footprint "PULSE_1,PULSE_5")
      (description "JUMPER")
      (libsource (lib "jumper") (part "JP8Q"))
    )
    (comp (ref "Q1")
      (value "~")
      (footprint "Q1               SOT-223")
      (description "ONSC-NMOS-G1D2S3D4-4")
      (libsource (lib "On Semiconductor - NTF3055L108T1G") (part "ON_SEMICONDUCTOR_NTF3055L108T1GON_SEMICONDUCTOR_NTF3055L108T1G_0_0"))
    )
    (comp (ref "R1")
      (value "~")
      (footprint "R0805")
      (description "RESISTOR, American symbol")
      (libsource (lib "rcl") (part "R-US_M0805"))
    )
    (comp (ref "R2")
      (value "~")
      (footprint "R0805")
      (description "RESISTOR, American symbol")
      (libsource (lib "rcl") (part "R-US_M0805"))
    )
    (comp (ref "R3")
      (value "~")
      (footprint "R0805")
      (description "RESISTOR, American symbol")
      (libsource (lib "rcl") (part "R-US_M0805"))
    )
    (comp (ref "R4")
      (value "~")
      (footprint "R0805")
      (description "RESISTOR, American symbol")
      (libsource (lib "rcl") (part "R-US_M0805"))
    )
    (comp (ref "R5")
      (value "~")
      (footprint "R0805")
      (description "RESISTOR, American symbol")
      (libsource (lib "rcl") (part "R-US_M0805"))
    )
    (comp (ref "R6")
      (value "~")
      (footprint "R0805")
      (description "RESISTOR, American symbol")
      (libsource (lib "rcl") (part "R-US_M0805"))
    )
    (comp (ref "R7")
      (value "~")
      (footprint "R0805")
      (description "RESISTOR, American symbol")
      (libsource (lib "rcl") (part "R-US_M0805"))
    )
    (comp (ref "R8")
      (value "~")
      (footprint "R0805")
      (description "RESISTOR, American symbol")
      (libsource (lib "rcl") (part "R-US_M0805"))
    )
    (comp (ref "R9")
      (value "~")
      (footprint "R0805")
      (description "RESISTOR, American symbol")
      (libsource (lib "rcl") (part "R-US_M0805"))
    )
    (comp (ref "R10")
      (value "~")
      (footprint "R0805")
      (description "RESISTOR, American symbol")
      (libsource (lib "rcl") (part "R-US_M0805"))
    )
    (comp (ref "R11")
      (value "~")
      (footprint "R0805")
      (description "RESISTOR, American symbol")
      (libsource (lib "rcl") (part "R-US_M0805"))
    )
    (comp (ref "R12")
      (value "~")
      (footprint "R0805")
      (description "RESISTOR, American symbol")
      (libsource (lib "rcl") (part "R-US_M0805"))
    )
    (comp (ref "R13")
      (value "~")
      (footprint "R0805")
      (description "RESISTOR, American symbol")
      (libsource (lib "rcl") (part "R-US_M0805"))
    )
    (comp (ref "R14")
      (value "~")
      (footprint "R0805")
      (description "RESISTOR, American symbol")
      (libsource (lib "rcl") (part "R-US_M0805"))
    )
    (comp (ref "R15")
      (value "~")
      (footprint "R0805")
      (description "RESISTOR, American symbol")
      (libsource (lib "rcl") (part "R-US_M0805"))
    )
    (comp (ref "R16")
      (value "~")
      (footprint "R0805")
      (description "RESISTOR, American symbol")
      (libsource (lib "rcl") (part "R-US_M0805"))
    )
    (comp (ref "R17")
      (value "~")
      (footprint "R0805")
      (description "RESISTOR, American symbol")
      (libsource (lib "rcl") (part "R-US_M0805"))
    )
    (comp (ref "R18")
      (value "~")
      (footprint "R0805")
      (description "RESISTOR, American symbol")
      (libsource (lib "rcl") (part "R-US_M0805"))
    )
    (comp (ref "R19")
      (value "~")
      (footprint "R0805")
      (description "RESISTOR, American symbol")
      (libsource (lib "rcl") (part "R-US_M0805"))
    )
    (comp (ref "R20")
      (value "~")
      (footprint "R0805")
      (description "RESISTOR, American symbol")
      (libsource (lib "rcl") (part "R-US_M0805"))
    )
    (comp (ref "R21")
      (value "~")
      (footprint "R0805")
      (description "RESISTOR, American symbol")
      (libsource (lib "rcl") (part "R-US_M0805"))
    )
    (comp (ref "R22")
      (value "~")
      (footprint "R0805")
      (description "RESISTOR, American symbol")
      (libsource (lib "rcl") (part "R-US_M0805"))
    )
    (comp (ref "R23")
      (value "~")
      (footprint "R0805")
      (description "RESISTOR, American symbol")
      (libsource (lib "rcl") (part "R-US_M0805"))
    )
    (comp (ref "R24")
      (value "~")
      (footprint "R0805")
      (description "RESISTOR, American symbol")
      (libsource (lib "rcl") (part "R-US_M0805"))
    )
    (comp (ref "R25")
      (value "~")
      (footprint "R0805")
      (description "RESISTOR, American symbol")
      (libsource (lib "rcl") (part "R-US_M0805"))
    )
    (comp (ref "R26")
      (value "~")
      (footprint "R0805")
      (description "RESISTOR, American symbol")
      (libsource (lib "rcl") (part "R-US_M0805"))
    )
    (comp (ref "R27")
      (value "~")
      (footprint "R0805")
      (description "RESISTOR, American symbol")
      (libsource (lib "rcl") (part "R-US_M0805"))
    )
    (comp (ref "R28")
      (value "~")
      (footprint "R0805")
      (description "RESISTOR, American symbol")
      (libsource (lib "rcl") (part "R-US_M0805"))
    )
    (comp (ref "R29")
      (value "~")
      (footprint "R0805")
      (description "RESISTOR, American symbol")
      (libsource (lib "rcl") (part "R-US_M0805"))
    )
    (comp (ref "R30")
      (value "~")
      (footprint "R0805")
      (description "RESISTOR, American symbol")
      (libsource (lib "rcl") (part "R-US_M0805"))
    )
    (comp (ref "R31")
      (value "~")
      (footprint "R0805")
      (description "RESISTOR, American symbol")
      (libsource (lib "rcl") (part "R-US_M0805"))
    )
    (comp (ref "R32")
      (value "~")
      (footprint "R0805")
      (description "RESISTOR, American symbol")
      (libsource (lib "rcl") (part "R-US_M0805"))
    )
    (comp (ref "R33")
      (value "~")
      (footprint "R0805")
      (description "RESISTOR, American symbol")
      (libsource (lib "rcl") (part "R-US_M0805"))
    )
    (comp (ref "R34")
      (value "~")
      (footprint "R0805")
      (description "RESISTOR, American symbol")
      (libsource (lib "rcl") (part "R-US_M0805"))
    )
    (comp (ref "R35")
      (value "~")
      (footprint "R0805")
      (description "RESISTOR, American symbol")
      (libsource (lib "rcl") (part "R-US_M0805"))
    )
    (comp (ref "R36")
      (value "~")
      (footprint "R0805")
      (description "RESISTOR, American symbol")
      (libsource (lib "rcl") (part "R-US_M0805"))
    )
    (comp (ref "R37")
      (value "~")
      (footprint "R0805")
      (description "RESISTOR, American symbol")
      (libsource (lib "rcl") (part "R-US_M0805"))
    )
    (comp (ref "R38")
      (value "~")
      (footprint "R0805")
      (description "RESISTOR, American symbol")
      (libsource (lib "rcl") (part "R-US_M0805"))
    )
    (comp (ref "R39")
      (value "~")
      (footprint "R0805")
      (description "RESISTOR, American symbol")
      (libsource (lib "rcl") (part "R-US_M0805"))
    )
    (comp (ref "R40")
      (value "~")
      (footprint "R0805")
      (description "RESISTOR, American symbol")
      (libsource (lib "rcl") (part "R-US_M0805"))
    )
    (comp (ref "R41")
      (value "~")
      (footprint "R0805")
      (description "RESISTOR, American symbol")
      (libsource (lib "rcl") (part "R-US_M0805"))
    )
    (comp (ref "R42")
      (value "~")
      (footprint "R0805")
      (description "RESISTOR, American symbol")
      (libsource (lib "rcl") (part "R-US_M0805"))
    )
    (comp (ref "R43")
      (value "~")
      (footprint "R0805")
      (description "RESISTOR, American symbol")
      (libsource (lib "rcl") (part "R-US_M0805"))
    )
    (comp (ref "R44")
      (value "~")
      (footprint "R0805")
      (description "RESISTOR, American symbol")
      (libsource (lib "rcl") (part "R-US_M0805"))
    )
    (comp (ref "R45")
      (value "~")
      (footprint "R0805")
      (description "RESISTOR, American symbol")
      (libsource (lib "rcl") (part "R-US_M0805"))
    )
    (comp (ref "R46")
      (value "~")
      (footprint "R0805")
      (description "RESISTOR, American symbol")
      (libsource (lib "rcl") (part "R-US_M0805"))
    )
    (comp (ref "R47")
      (value "~")
      (footprint "R0805")
      (description "RESISTOR, American symbol")
      (libsource (lib "rcl") (part "R-US_M0805"))
    )
    (comp (ref "R48")
      (value "~")
      (footprint "R0805")
      (description "RESISTOR, American symbol")
      (libsource (lib "rcl") (part "R-US_M0805"))
    )
    (comp (ref "R49")
      (value "~")
      (footprint "R0805")
      (description "RESISTOR, American symbol")
      (libsource (lib "rcl") (part "R-US_M0805"))
    )
    (comp (ref "R50")
      (value "~")
      (footprint "R0805")
      (description "RESISTOR, American symbol")
      (libsource (lib "rcl") (part "R-US_M0805"))
    )
    (comp (ref "R51")
      (value "~")
      (footprint "R0805")
      (description "RESISTOR, American symbol")
      (libsource (lib "rcl") (part "R-US_M0805"))
    )
    (comp (ref "R52")
      (value "~")
      (footprint "R0805")
      (description "RESISTOR, American symbol")
      (libsource (lib "rcl") (part "R-US_M0805"))
    )
    (comp (ref "R53")
      (value "~")
      (footprint "R0805")
      (description "RESISTOR, American symbol")
      (libsource (lib "rcl") (part "R-US_M0805"))
    )
    (comp (ref "SV1")
      (value "~")
      (footprint "SV1")
      (description "PIN HEADER")
      (libsource (lib "con-lstb") (part "MA09-1"))
    )
    (comp (ref "SV2")
      (value "~")
      (footprint "SV2,SV4")
      (description "PIN HEADER")
      (libsource (lib "con-lstb") (part "MA10-1"))
    )
    (comp (ref "SV3")
      (value "~")
      (footprint "SV3,SV6")
      (description "PIN HEADER")
      (libsource (lib "con-lstb") (part "MA04-1"))
    )
    (comp (ref "SV4")
      (value "~")
      (footprint "SV2,SV4")
      (description "PIN HEADER")
      (libsource (lib "con-lstb") (part "MA10-1"))
    )
    (comp (ref "SV5")
      (value "~")
      (footprint "SV5")
      (description "PIN HEADER")
      (libsource (lib "con-lstb") (part "MA03-1"))
    )
    (comp (ref "SV6")
      (value "~")
      (footprint "SV3,SV6")
      (description "PIN HEADER")
      (libsource (lib "con-lstb") (part "MA04-1"))
    )
    (comp (ref "SV7")
      (value "~")
      (footprint "SV7")
      (description "PIN HEADER")
      (libsource (lib "con-lstb") (part "MA08-1"))
    )
    (comp (ref "SV8")
      (value "~")
      (footprint "SV8,SV9")
      (description "PIN HEADER")
      (libsource (lib "con-lstb") (part "MA06-1"))
    )
    (comp (ref "SV9")
      (value "~")
      (footprint "SV8,SV9")
      (description "PIN HEADER")
      (libsource (lib "con-lstb") (part "MA06-1"))
    )
    (comp (ref "SV10")
      (value "~")
      (footprint "SV10")
      (description "PIN HEADER")
      (libsource (lib "con-lstb") (part "MA10-2"))
    )
    (comp (ref "U$1")
      (value "~")
      (footprint "U$1")
      (description "TE Connectivity AMP Connectors 6565204-1")
      (libsource (lib "Probe_connector") (part "PROBE_CONNECTOR"))
    )
    (comp (ref "U$2")
      (value "~")
      (footprint "U$2          TSSOP-16")
      (libsource (lib "5PB1108PGGI") (part "5PB1108PGGI"))
    )
    (comp (ref "U1")
      (value "~")
      (footprint "U1")
      (description "IC TXRX RS232 5V 336CSBGA")
      (libsource (lib "Maxim Electronics - MAX2082CXD+") (part "MAXIM_ELECTRONICS_MAX2082CXD+MAXIM_ELECTRONICS_MAX2082CXD+_0_0"))
    )
    (comp (ref "U2")
      (value "~")
      (footprint "U2")
      (libsource (lib "MAX6225") (part "MAX6225BCSA+21-0041B_8-M"))
    )
    (comp (ref "U3")
      (value "~")
      (footprint "U3 to U10                           TQFP48")
      (libsource (lib "MAX4968") (part "MAX4968AECM+21-0054G_48-M"))
    )
    (comp (ref "U4")
      (value "~")
      (footprint "U3 to U10                           TQFP48")
      (libsource (lib "MAX4968") (part "MAX4968AECM+21-0054G_48-M"))
    )
    (comp (ref "U5")
      (value "~")
      (footprint "U3 to U10                           TQFP48")
      (libsource (lib "MAX4968") (part "MAX4968AECM+21-0054G_48-M"))
    )
    (comp (ref "U6")
      (value "~")
      (footprint "U3 to U10                           TQFP48")
      (libsource (lib "MAX4968") (part "MAX4968AECM+21-0054G_48-M"))
    )
    (comp (ref "U7")
      (value "~")
      (footprint "U3 to U10                           TQFP48")
      (libsource (lib "MAX4968") (part "MAX4968AECM+21-0054G_48-M"))
    )
    (comp (ref "U8")
      (value "~")
      (footprint "U3 to U10                           TQFP48")
      (libsource (lib "MAX4968") (part "MAX4968AECM+21-0054G_48-M"))
    )
    (comp (ref "U9")
      (value "~")
      (footprint "U3 to U10                           TQFP48")
      (libsource (lib "MAX4968") (part "MAX4968AECM+21-0054G_48-M"))
    )
    (comp (ref "U10")
      (value "~")
      (footprint "U3 to U10                           TQFP48")
      (libsource (lib "MAX4968") (part "MAX4968AECM+21-0054G_48-M"))
    )
    (comp (ref "U11")
      (value "~")
      (footprint "U11 to U15 ,U16 ,U17       TO-220")
      (description "PM-REG-LM1086-SIL3")
      (libsource (lib "NOPB") (part "TI_NATIONAL_SEMICONDUCTOR_LM1117T-3.3-NOPBTI_NATIONAL_SEMICONDUCTOR_LM1117T-3.3-NOPB_0_0"))
    )
    (comp (ref "U12")
      (value "~")
      (footprint "U11 to U15 ,U16 ,U17       TO-220")
      (description "PM-REG-LM1086-SIL3")
      (libsource (lib "NOPB") (part "TI_NATIONAL_SEMICONDUCTOR_LM1117T-5.0-NOPBTI_NATIONAL_SEMICONDUCTOR_LM1117T-5.0-NOPB_0_0"))
    )
    (comp (ref "U13")
      (value "~")
      (footprint "U11 to U15 ,U16 ,U17       TO-220")
      (description "PM-REG-LM1086ADJ-SIL3")
      (libsource (lib "NOPB") (part "TI_NATIONAL_SEMICONDUCTOR_LM1117T-ADJ-NOPBTI_NATIONAL_SEMICONDUCTOR_LM1117T-ADJ-NOPB_0_0"))
    )
    (comp (ref "U14")
      (value "~")
      (footprint "U11 to U15 ,U16 ,U17       TO-220")
      (description "PM-REG-LM1086ADJ-SIL3")
      (libsource (lib "NOPB") (part "TI_NATIONAL_SEMICONDUCTOR_LM1117T-ADJ-NOPBTI_NATIONAL_SEMICONDUCTOR_LM1117T-ADJ-NOPB_0_0"))
    )
    (comp (ref "U15")
      (value "~")
      (footprint "U11 to U15 ,U16 ,U17       TO-220")
      (description "PM-REG-LM1086ADJ-SIL3")
      (libsource (lib "NOPB") (part "TI_NATIONAL_SEMICONDUCTOR_LM1117T-ADJ-NOPBTI_NATIONAL_SEMICONDUCTOR_LM1117T-ADJ-NOPB_0_0"))
    )
    (comp (ref "U16")
      (value "~")
      (footprint "U11 to U15 ,U16 ,U17       TO-220")
      (description "PM-REG-LD1117V-SIL3")
      (libsource (lib "STMicroelectronics - LD1117V18") (part "STMICROELECTRONICS_LD1117V18STMICROELECTRONICS_LD1117V18_0_0"))
    )
    (comp (ref "U17")
      (value "~")
      (footprint "U11 to U15 ,U16 ,U17       TO-220")
      (description "PM-REG-LD1117V-SIL3")
      (libsource (lib "STMicroelectronics - LD1117V18") (part "STMICROELECTRONICS_LD1117V18STMICROELECTRONICS_LD1117V18_0_0"))
    )
    (comp (ref "U19")
      (value "~")
      (footprint "U19")
      (description "TI-7660-8")
      (libsource (lib "Texas Instruments - TL7660CDGKR") (part "TEXAS_INSTRUMENTS_TL7660CDGKRTEXAS_INSTRUMENTS_TL7660CDGKR_0_1"))
    )
    (comp (ref "U20")
      (value "~")
      (footprint "U20                SOT23-6")
      (libsource (lib "MAX6819") (part "MAX6819UT+T21-0058I-L"))
    )
    (comp (ref "X1")
      (value "~")
      (footprint "X1 to X4")
      (description "CONNECTOR")
      (libsource (lib "con-ptr500") (part "AK500/2"))
    )
    (comp (ref "X2")
      (value "~")
      (footprint "X1 to X4")
      (description "CONNECTOR")
      (libsource (lib "") (part "AK500/2_1"))
    )
    (comp (ref "X3")
      (value "~")
      (footprint "X1 to X4")
      (description "CONNECTOR")
      (libsource (lib "") (part "AK500/2_1"))
    )
    (comp (ref "X4")
      (value "~")
      (footprint "X1 to X4")
      (description "CONNECTOR")
      (libsource (lib "") (part "AK500/2_2"))
    )
  )
  (nets
    (net (code "1") (name "+1.8V") (class "Default")
      (node (ref "C13") (pin "1") (pinfunction "1_1") (pintype "passive"))
      (node (ref "C14") (pin "1") (pinfunction "1_1") (pintype "passive"))
      (node (ref "C15") (pin "1") (pinfunction "1_1") (pintype "passive"))
      (node (ref "C33") (pin "1") (pinfunction "1_1") (pintype "passive"))
      (node (ref "Q1") (pin "2") (pinfunction "1_D_2") (pintype "passive"))
      (node (ref "SV4") (pin "2") (pinfunction "2_2") (pintype "passive"))
      (node (ref "U1") (pin "A28") (pinfunction "1_OVDD_A28") (pintype "passive"))
      (node (ref "U1") (pin "F26") (pinfunction "2_OVDD_F26") (pintype "passive"))
      (node (ref "U1") (pin "G26") (pinfunction "3_OVDD_G26") (pintype "passive"))
      (node (ref "U1") (pin "M28") (pinfunction "4_OVDD_M28") (pintype "passive"))
      (node (ref "U16") (pin "2") (pinfunction "VOUT_2") (pintype "power_in"))
      (node (ref "U20") (pin "6") (pinfunction "VCC2_6") (pintype "power_in"))
    )
    (net (code "2") (name "+1.8VA") (class "Default")
      (node (ref "C10") (pin "1") (pinfunction "1_1") (pintype "passive"))
      (node (ref "C11") (pin "1") (pinfunction "1_1") (pintype "passive"))
      (node (ref "C35") (pin "1") (pinfunction "1_1") (pintype "passive"))
      (node (ref "C9") (pin "1") (pinfunction "1_1") (pintype "passive"))
      (node (ref "R31") (pin "2") (pinfunction "2_2") (pintype "passive"))
      (node (ref "SV4") (pin "1") (pinfunction "1_1") (pintype "passive"))
      (node (ref "U1") (pin "A23") (pinfunction "1_AVDD_A23") (pintype "passive"))
      (node (ref "U1") (pin "B24") (pinfunction "2_AVDD_B24") (pintype "passive"))
      (node (ref "U1") (pin "L23") (pinfunction "3_AVDD_L23") (pintype "passive"))
      (node (ref "U1") (pin "M23") (pinfunction "4_AVDD_M23") (pintype "passive"))
      (node (ref "U17") (pin "2") (pinfunction "VOUT_2") (pintype "power_in"))
    )
    (net (code "3") (name "+2.5V") (class "Default")
      (node (ref "C27") (pin "1") (pinfunction "1_1") (pintype "passive"))
      (node (ref "C8") (pin "1") (pinfunction "1_1") (pintype "passive"))
      (node (ref "SV4") (pin "3") (pinfunction "3_3") (pintype "passive"))
      (node (ref "U1") (pin "L20") (pinfunction "VREF_L20") (pintype "passive"))
      (node (ref "U2") (pin "6") (pinfunction "OUT_6") (pintype "output"))
    )
    (net (code "4") (name "+3.3V") (class "Default")
      (node (ref "C1") (pin "1") (pinfunction "1_1") (pintype "passive"))
      (node (ref "C101") (pin "1") (pinfunction "1_1") (pintype "passive"))
      (node (ref "C2") (pin "1") (pinfunction "1_1") (pintype "passive"))
      (node (ref "C3") (pin "1") (pinfunction "1_1") (pintype "passive"))
      (node (ref "C31") (pin "1") (pinfunction "1_1") (pintype "passive"))
      (node (ref "C45") (pin "1") (pinfunction "1_1") (pintype "passive"))
      (node (ref "C47") (pin "1") (pinfunction "1_1") (pintype "passive"))
      (node (ref "C54") (pin "1") (pinfunction "1_1") (pintype "passive"))
      (node (ref "C55") (pin "1") (pinfunction "1_1") (pintype "passive"))
      (node (ref "C60") (pin "1") (pinfunction "1_1") (pintype "passive"))
      (node (ref "C61") (pin "1") (pinfunction "1_1") (pintype "passive"))
      (node (ref "C66") (pin "1") (pinfunction "1_1") (pintype "passive"))
      (node (ref "C67") (pin "1") (pinfunction "1_1") (pintype "passive"))
      (node (ref "C72") (pin "1") (pinfunction "1_1") (pintype "passive"))
      (node (ref "C73") (pin "1") (pinfunction "1_1") (pintype "passive"))
      (node (ref "C78") (pin "1") (pinfunction "1_1") (pintype "passive"))
      (node (ref "C79") (pin "1") (pinfunction "1_1") (pintype "passive"))
      (node (ref "C84") (pin "1") (pinfunction "1_1") (pintype "passive"))
      (node (ref "C85") (pin "1") (pinfunction "1_1") (pintype "passive"))
      (node (ref "C90") (pin "1") (pinfunction "1_1") (pintype "passive"))
      (node (ref "C91") (pin "1") (pinfunction "1_1") (pintype "passive"))
      (node (ref "C96") (pin "1") (pinfunction "1_1") (pintype "passive"))
      (node (ref "C97") (pin "1") (pinfunction "1_1") (pintype "passive"))
      (node (ref "N1") (pin "19") (pinfunction "VIO_19") (pintype "power_in"))
      (node (ref "R36") (pin "2") (pinfunction "2_2") (pintype "passive"))
      (node (ref "R37") (pin "2") (pinfunction "2_2") (pintype "passive"))
      (node (ref "R38") (pin "2") (pinfunction "2_2") (pintype "passive"))
      (node (ref "R39") (pin "2") (pinfunction "2_2") (pintype "passive"))
      (node (ref "R40") (pin "2") (pinfunction "2_2") (pintype "passive"))
      (node (ref "R41") (pin "2") (pinfunction "2_2") (pintype "passive"))
      (node (ref "R42") (pin "2") (pinfunction "2_2") (pintype "passive"))
      (node (ref "R43") (pin "2") (pinfunction "2_2") (pintype "passive"))
      (node (ref "R46") (pin "2") (pinfunction "2_2") (pintype "passive"))
      (node (ref "SV4") (pin "5") (pinfunction "5_5") (pintype "passive"))
      (node (ref "SV9") (pin "1") (pinfunction "1_1") (pintype "passive"))
      (node (ref "U$2") (pin "10") (pinfunction "VDD3_10") (pintype "passive"))
      (node (ref "U$2") (pin "14") (pinfunction "VDD2_14") (pintype "passive"))
      (node (ref "U$2") (pin "2") (pinfunction "1G_2") (pintype "passive"))
      (node (ref "U$2") (pin "5") (pinfunction "VDD1_5") (pintype "passive"))
      (node (ref "U1") (pin "A19") (pinfunction "1_VCC3_A19") (pintype "passive"))
      (node (ref "U1") (pin "L22") (pinfunction "2_VCC3_L22") (pintype "passive"))
      (node (ref "U1") (pin "M22") (pinfunction "3_VCC3_M22") (pintype "passive"))
      (node (ref "U10") (pin "18") (pinfunction "VDD_18") (pintype "power_in"))
      (node (ref "U11") (pin "2") (pinfunction "OUT_2") (pintype "power_in"))
      (node (ref "U20") (pin "1") (pinfunction "VCC1_1") (pintype "power_in"))
      (node (ref "U3") (pin "18") (pinfunction "VDD_18") (pintype "power_in"))
      (node (ref "U4") (pin "18") (pinfunction "VDD_18") (pintype "power_in"))
      (node (ref "U5") (pin "18") (pinfunction "VDD_18") (pintype "power_in"))
      (node (ref "U6") (pin "18") (pinfunction "VDD_18") (pintype "power_in"))
      (node (ref "U7") (pin "18") (pinfunction "VDD_18") (pintype "power_in"))
      (node (ref "U8") (pin "18") (pinfunction "VDD_18") (pintype "power_in"))
      (node (ref "U9") (pin "18") (pinfunction "VDD_18") (pintype "power_in"))
    )
    (net (code "5") (name "+3V") (class "Default")
      (node (ref "C12") (pin "1") (pinfunction "1_1") (pintype "passive"))
      (node (ref "C38") (pin "1") (pinfunction "1_1") (pintype "passive"))
      (node (ref "R23") (pin "2") (pinfunction "2_2") (pintype "passive"))
      (node (ref "SV4") (pin "4") (pinfunction "4_4") (pintype "passive"))
      (node (ref "U1") (pin "A10") (pinfunction "1_TVDD_A10") (pintype "passive"))
      (node (ref "U1") (pin "M10") (pinfunction "2_TVDD_M10") (pintype "passive"))
      (node (ref "U14") (pin "2") (pinfunction "OUT_2") (pintype "power_in"))
    )
    (net (code "6") (name "+5V") (class "Default")
      (node (ref "C29") (pin "1") (pinfunction "1_1") (pintype "passive"))
      (node (ref "C4") (pin "1") (pinfunction "1_1") (pintype "passive"))
      (node (ref "C5") (pin "1") (pinfunction "1_1") (pintype "passive"))
      (node (ref "C6") (pin "1") (pinfunction "1_1") (pintype "passive"))
      (node (ref "C7") (pin "1") (pinfunction "1_1") (pintype "passive"))
      (node (ref "SV4") (pin "6") (pinfunction "6_6") (pintype "passive"))
      (node (ref "U1") (pin "B19") (pinfunction "1_VCC5_B19") (pintype "passive"))
      (node (ref "U1") (pin "B5") (pinfunction "1_TVCC_B5") (pintype "passive"))
      (node (ref "U1") (pin "L19") (pinfunction "2_VCC5_L19") (pintype "passive"))
      (node (ref "U1") (pin "L5") (pinfunction "2_TVCC_L5") (pintype "passive"))
      (node (ref "U1") (pin "M19") (pinfunction "3_VCC5_M19") (pintype "passive"))
      (node (ref "U1") (pin "M20") (pinfunction "4_VCC5_M20") (pintype "passive"))
      (node (ref "U12") (pin "2") (pinfunction "OUT_2") (pintype "power_in"))
      (node (ref "U19") (pin "8") (pinfunction "VCC_8") (pintype "power_in"))
    )
    (net (code "7") (name "+10V") (class "Default")
      (node (ref "C39") (pin "1") (pinfunction "1_1") (pintype "passive"))
      (node (ref "C52") (pin "1") (pinfunction "1_1") (pintype "passive"))
      (node (ref "C53") (pin "1") (pinfunction "1_1") (pintype "passive"))
      (node (ref "C58") (pin "1") (pinfunction "1_1") (pintype "passive"))
      (node (ref "C59") (pin "1") (pinfunction "1_1") (pintype "passive"))
      (node (ref "C64") (pin "1") (pinfunction "1_1") (pintype "passive"))
      (node (ref "C65") (pin "1") (pinfunction "1_1") (pintype "passive"))
      (node (ref "C70") (pin "1") (pinfunction "1_1") (pintype "passive"))
      (node (ref "C71") (pin "1") (pinfunction "1_1") (pintype "passive"))
      (node (ref "C76") (pin "1") (pinfunction "1_1") (pintype "passive"))
      (node (ref "C77") (pin "1") (pinfunction "1_1") (pintype "passive"))
      (node (ref "C82") (pin "1") (pinfunction "1_1") (pintype "passive"))
      (node (ref "C83") (pin "1") (pinfunction "1_1") (pintype "passive"))
      (node (ref "C88") (pin "1") (pinfunction "1_1") (pintype "passive"))
      (node (ref "C89") (pin "1") (pinfunction "1_1") (pintype "passive"))
      (node (ref "C94") (pin "1") (pinfunction "1_1") (pintype "passive"))
      (node (ref "C95") (pin "1") (pinfunction "1_1") (pintype "passive"))
      (node (ref "R34") (pin "2") (pinfunction "2_2") (pintype "passive"))
      (node (ref "SV4") (pin "7") (pinfunction "7_7") (pintype "passive"))
      (node (ref "U10") (pin "15") (pinfunction "VPP_15") (pintype "power_in"))
      (node (ref "U15") (pin "2") (pinfunction "OUT_2") (pintype "power_in"))
      (node (ref "U3") (pin "15") (pinfunction "VPP_15") (pintype "power_in"))
      (node (ref "U4") (pin "15") (pinfunction "VPP_15") (pintype "power_in"))
      (node (ref "U5") (pin "15") (pinfunction "VPP_15") (pintype "power_in"))
      (node (ref "U6") (pin "15") (pinfunction "VPP_15") (pintype "power_in"))
      (node (ref "U7") (pin "15") (pinfunction "VPP_15") (pintype "power_in"))
      (node (ref "U8") (pin "15") (pinfunction "VPP_15") (pintype "power_in"))
      (node (ref "U9") (pin "15") (pinfunction "VPP_15") (pintype "power_in"))
    )
    (net (code "8") (name "+11V") (class "Default")
      (node (ref "C40") (pin "1") (pinfunction "1_1") (pintype "passive"))
      (node (ref "R24") (pin "1") (pinfunction "1_1") (pintype "passive"))
      (node (ref "R25") (pin "1") (pinfunction "1_1") (pintype "passive"))
      (node (ref "R26") (pin "1") (pinfunction "1_1") (pintype "passive"))
      (node (ref "R27") (pin "1") (pinfunction "1_1") (pintype "passive"))
      (node (ref "R29") (pin "2") (pinfunction "2_2") (pintype "passive"))
      (node (ref "SV4") (pin "8") (pinfunction "8_8") (pintype "passive"))
      (node (ref "U13") (pin "2") (pinfunction "OUT_2") (pintype "power_in"))
    )
    (net (code "9") (name "+12V") (class "Default")
      (node (ref "C26") (pin "1") (pinfunction "1_1") (pintype "passive"))
      (node (ref "C28") (pin "1") (pinfunction "1_1") (pintype "passive"))
      (node (ref "C30") (pin "1") (pinfunction "1_1") (pintype "passive"))
      (node (ref "C32") (pin "1") (pinfunction "1_1") (pintype "passive"))
      (node (ref "C34") (pin "1") (pinfunction "1_1") (pintype "passive"))
      (node (ref "C37") (pin "1") (pinfunction "1_1") (pintype "passive"))
      (node (ref "C48") (pin "1") (pinfunction "1_1") (pintype "passive"))
      (node (ref "C98") (pin "1") (pinfunction "1_1") (pintype "passive"))
      (node (ref "C99") (pin "1") (pinfunction "1_1") (pintype "passive"))
      (node (ref "L1") (pin "2") (pinfunction "2_2") (pintype "passive"))
      (node (ref "U11") (pin "3") (pinfunction "IN_3") (pintype "power_in"))
      (node (ref "U12") (pin "3") (pinfunction "IN_3") (pintype "power_in"))
      (node (ref "U13") (pin "3") (pinfunction "IN_3") (pintype "power_in"))
      (node (ref "U14") (pin "3") (pinfunction "IN_3") (pintype "power_in"))
      (node (ref "U15") (pin "3") (pinfunction "IN_3") (pintype "power_in"))
      (node (ref "U16") (pin "3") (pinfunction "VIN_3") (pintype "power_in"))
      (node (ref "U17") (pin "3") (pinfunction "VIN_3") (pintype "power_in"))
      (node (ref "U2") (pin "2") (pinfunction "IN_2") (pintype "passive"))
    )
    (net (code "10") (name "-5V") (class "Default")
      (node (ref "C100") (pin "2") (pinfunction "-_2") (pintype "passive"))
      (node (ref "C36") (pin "1") (pinfunction "1_1") (pintype "passive"))
      (node (ref "SV4") (pin "9") (pinfunction "9_9") (pintype "passive"))
      (node (ref "U1") (pin "A5") (pinfunction "1_TVEE_A5") (pintype "passive"))
      (node (ref "U1") (pin "M5") (pinfunction "2_TVEE_M5") (pintype "passive"))
      (node (ref "U19") (pin "5") (pinfunction "VOUT_5") (pintype "output"))
    )
    (net (code "11") (name "-50V") (class "Default")
      (node (ref "C50") (pin "1") (pinfunction "1_1") (pintype "passive"))
      (node (ref "C51") (pin "1") (pinfunction "1_1") (pintype "passive"))
      (node (ref "C56") (pin "1") (pinfunction "1_1") (pintype "passive"))
      (node (ref "C57") (pin "1") (pinfunction "1_1") (pintype "passive"))
      (node (ref "C62") (pin "1") (pinfunction "1_1") (pintype "passive"))
      (node (ref "C63") (pin "1") (pinfunction "1_1") (pintype "passive"))
      (node (ref "C68") (pin "1") (pinfunction "1_1") (pintype "passive"))
      (node (ref "C69") (pin "1") (pinfunction "1_1") (pintype "passive"))
      (node (ref "C74") (pin "1") (pinfunction "1_1") (pintype "passive"))
      (node (ref "C75") (pin "1") (pinfunction "1_1") (pintype "passive"))
      (node (ref "C80") (pin "1") (pinfunction "1_1") (pintype "passive"))
      (node (ref "C81") (pin "1") (pinfunction "1_1") (pintype "passive"))
      (node (ref "C86") (pin "1") (pinfunction "1_1") (pintype "passive"))
      (node (ref "C87") (pin "1") (pinfunction "1_1") (pintype "passive"))
      (node (ref "C92") (pin "1") (pinfunction "1_1") (pintype "passive"))
      (node (ref "C93") (pin "1") (pinfunction "1_1") (pintype "passive"))
      (node (ref "U10") (pin "13") (pinfunction "VNN_13") (pintype "passive"))
      (node (ref "U3") (pin "13") (pinfunction "VNN_13") (pintype "passive"))
      (node (ref "U4") (pin "13") (pinfunction "VNN_13") (pintype "passive"))
      (node (ref "U5") (pin "13") (pinfunction "VNN_13") (pintype "passive"))
      (node (ref "U6") (pin "13") (pinfunction "VNN_13") (pintype "passive"))
      (node (ref "U7") (pin "13") (pinfunction "VNN_13") (pintype "passive"))
      (node (ref "U8") (pin "13") (pinfunction "VNN_13") (pintype "passive"))
      (node (ref "U9") (pin "13") (pinfunction "VNN_13") (pintype "passive"))
      (node (ref "X4") (pin "2") (pinfunction "KL_2") (pintype "passive"))
    )
    (net (code "12") (name "/CH1") (class "Default")
      (node (ref "U$1") (pin "A54") (pinfunction "A54_A54") (pintype "passive"))
      (node (ref "U3") (pin "11") (pinfunction "SW0B_11") (pintype "passive"))
    )
    (net (code "13") (name "/CH2") (class "Default")
      (node (ref "U$1") (pin "A53") (pinfunction "A53_A53") (pintype "passive"))
      (node (ref "U3") (pin "9") (pinfunction "SW1B_9") (pintype "passive"))
    )
    (net (code "14") (name "/CH3") (class "Default")
      (node (ref "U$1") (pin "B53") (pinfunction "B53_B53") (pintype "passive"))
      (node (ref "U3") (pin "7") (pinfunction "SW2B_7") (pintype "passive"))
    )
    (net (code "15") (name "/CH4") (class "Default")
      (node (ref "U$1") (pin "B52") (pinfunction "B52_B52") (pintype "passive"))
      (node (ref "U3") (pin "5") (pinfunction "SW3B_5") (pintype "passive"))
    )
    (net (code "16") (name "/CH5") (class "Default")
      (node (ref "U$1") (pin "B51") (pinfunction "B51_B51") (pintype "passive"))
      (node (ref "U3") (pin "3") (pinfunction "SW4B_3") (pintype "passive"))
    )
    (net (code "17") (name "/CH6") (class "Default")
      (node (ref "U$1") (pin "A51") (pinfunction "A51_A51") (pintype "passive"))
      (node (ref "U3") (pin "47") (pinfunction "SW5B_47") (pintype "passive"))
    )
    (net (code "18") (name "/CH7") (class "Default")
      (node (ref "U$1") (pin "A50") (pinfunction "A50_A50") (pintype "passive"))
      (node (ref "U3") (pin "45") (pinfunction "SW6B_45") (pintype "passive"))
    )
    (net (code "19") (name "/CH8") (class "Default")
      (node (ref "U$1") (pin "A49") (pinfunction "A49_A49") (pintype "passive"))
      (node (ref "U3") (pin "43") (pinfunction "SW7B_43") (pintype "passive"))
    )
    (net (code "20") (name "/CH9") (class "Default")
      (node (ref "U$1") (pin "B49") (pinfunction "B49_B49") (pintype "passive"))
      (node (ref "U3") (pin "41") (pinfunction "SW8B_41") (pintype "passive"))
    )
    (net (code "21") (name "/CH10") (class "Default")
      (node (ref "U$1") (pin "B48") (pinfunction "B48_B48") (pintype "passive"))
      (node (ref "U3") (pin "39") (pinfunction "SW9B_39") (pintype "passive"))
    )
    (net (code "22") (name "/CH11") (class "Default")
      (node (ref "U$1") (pin "B47") (pinfunction "B47_B47") (pintype "passive"))
      (node (ref "U3") (pin "37") (pinfunction "SW10B_37") (pintype "passive"))
    )
    (net (code "23") (name "/CH12") (class "Default")
      (node (ref "U$1") (pin "A47") (pinfunction "A47_A47") (pintype "passive"))
      (node (ref "U3") (pin "33") (pinfunction "SW11B_33") (pintype "passive"))
    )
    (net (code "24") (name "/CH13") (class "Default")
      (node (ref "U$1") (pin "A46") (pinfunction "A46_A46") (pintype "passive"))
      (node (ref "U3") (pin "31") (pinfunction "SW12B_31") (pintype "passive"))
    )
    (net (code "25") (name "/CH14") (class "Default")
      (node (ref "U$1") (pin "A45") (pinfunction "A45_A45") (pintype "passive"))
      (node (ref "U3") (pin "29") (pinfunction "SW13B_29") (pintype "passive"))
    )
    (net (code "26") (name "/CH15") (class "Default")
      (node (ref "U$1") (pin "B45") (pinfunction "B45_B45") (pintype "passive"))
      (node (ref "U3") (pin "27") (pinfunction "SW14B_27") (pintype "passive"))
    )
    (net (code "27") (name "/CH16") (class "Default")
      (node (ref "U$1") (pin "B44") (pinfunction "B44_B44") (pintype "passive"))
      (node (ref "U3") (pin "25") (pinfunction "SW15B_25") (pintype "passive"))
    )
    (net (code "28") (name "/CH17") (class "Default")
      (node (ref "U$1") (pin "A42") (pinfunction "A42_A42") (pintype "passive"))
      (node (ref "U4") (pin "11") (pinfunction "SW0B_11") (pintype "passive"))
    )
    (net (code "29") (name "/CH18") (class "Default")
      (node (ref "U$1") (pin "A41") (pinfunction "A41_A41") (pintype "passive"))
      (node (ref "U4") (pin "9") (pinfunction "SW1B_9") (pintype "passive"))
    )
    (net (code "30") (name "/CH19") (class "Default")
      (node (ref "U$1") (pin "B41") (pinfunction "B41_B41") (pintype "passive"))
      (node (ref "U4") (pin "7") (pinfunction "SW2B_7") (pintype "passive"))
    )
    (net (code "31") (name "/CH20") (class "Default")
      (node (ref "U$1") (pin "B40") (pinfunction "B40_B40") (pintype "passive"))
      (node (ref "U4") (pin "5") (pinfunction "SW3B_5") (pintype "passive"))
    )
    (net (code "32") (name "/CH21") (class "Default")
      (node (ref "U$1") (pin "B39") (pinfunction "B39_B39") (pintype "passive"))
      (node (ref "U4") (pin "3") (pinfunction "SW4B_3") (pintype "passive"))
    )
    (net (code "33") (name "/CH22") (class "Default")
      (node (ref "U$1") (pin "A39") (pinfunction "A39_A39") (pintype "passive"))
      (node (ref "U4") (pin "47") (pinfunction "SW5B_47") (pintype "passive"))
    )
    (net (code "34") (name "/CH23") (class "Default")
      (node (ref "U$1") (pin "A38") (pinfunction "A38_A38") (pintype "passive"))
      (node (ref "U4") (pin "45") (pinfunction "SW6B_45") (pintype "passive"))
    )
    (net (code "35") (name "/CH24") (class "Default")
      (node (ref "U$1") (pin "A37") (pinfunction "A37_A37") (pintype "passive"))
      (node (ref "U4") (pin "43") (pinfunction "SW7B_43") (pintype "passive"))
    )
    (net (code "36") (name "/CH25") (class "Default")
      (node (ref "U$1") (pin "B37") (pinfunction "B37_B37") (pintype "passive"))
      (node (ref "U4") (pin "41") (pinfunction "SW8B_41") (pintype "passive"))
    )
    (net (code "37") (name "/CH26") (class "Default")
      (node (ref "U$1") (pin "B36") (pinfunction "B36_B36") (pintype "passive"))
      (node (ref "U4") (pin "39") (pinfunction "SW9B_39") (pintype "passive"))
    )
    (net (code "38") (name "/CH27") (class "Default")
      (node (ref "U$1") (pin "B35") (pinfunction "B35_B35") (pintype "passive"))
      (node (ref "U4") (pin "37") (pinfunction "SW10B_37") (pintype "passive"))
    )
    (net (code "39") (name "/CH28") (class "Default")
      (node (ref "U$1") (pin "A35") (pinfunction "A35_A35") (pintype "passive"))
      (node (ref "U4") (pin "33") (pinfunction "SW11B_33") (pintype "passive"))
    )
    (net (code "40") (name "/CH29") (class "Default")
      (node (ref "U$1") (pin "A34") (pinfunction "A34_A34") (pintype "passive"))
      (node (ref "U4") (pin "31") (pinfunction "SW12B_31") (pintype "passive"))
    )
    (net (code "41") (name "/CH30") (class "Default")
      (node (ref "U$1") (pin "A33") (pinfunction "A33_A33") (pintype "passive"))
      (node (ref "U4") (pin "29") (pinfunction "SW13B_29") (pintype "passive"))
    )
    (net (code "42") (name "/CH31") (class "Default")
      (node (ref "U$1") (pin "B33") (pinfunction "B33_B33") (pintype "passive"))
      (node (ref "U4") (pin "27") (pinfunction "SW14B_27") (pintype "passive"))
    )
    (net (code "43") (name "/CH32") (class "Default")
      (node (ref "U$1") (pin "B32") (pinfunction "B32_B32") (pintype "passive"))
      (node (ref "U4") (pin "25") (pinfunction "SW15B_25") (pintype "passive"))
    )
    (net (code "44") (name "/CH33") (class "Default")
      (node (ref "U$1") (pin "A30") (pinfunction "A30_A30") (pintype "passive"))
      (node (ref "U5") (pin "11") (pinfunction "SW0B_11") (pintype "passive"))
    )
    (net (code "45") (name "/CH34") (class "Default")
      (node (ref "U$1") (pin "A29") (pinfunction "A29_A29") (pintype "passive"))
      (node (ref "U5") (pin "9") (pinfunction "SW1B_9") (pintype "passive"))
    )
    (net (code "46") (name "/CH35") (class "Default")
      (node (ref "U$1") (pin "B29") (pinfunction "B29_B29") (pintype "passive"))
      (node (ref "U5") (pin "7") (pinfunction "SW2B_7") (pintype "passive"))
    )
    (net (code "47") (name "/CH36") (class "Default")
      (node (ref "U$1") (pin "B28") (pinfunction "B28_B28") (pintype "passive"))
      (node (ref "U5") (pin "5") (pinfunction "SW3B_5") (pintype "passive"))
    )
    (net (code "48") (name "/CH37") (class "Default")
      (node (ref "U$1") (pin "B27") (pinfunction "B27_B27") (pintype "passive"))
      (node (ref "U5") (pin "3") (pinfunction "SW4B_3") (pintype "passive"))
    )
    (net (code "49") (name "/CH38") (class "Default")
      (node (ref "U$1") (pin "A27") (pinfunction "A27_A27") (pintype "passive"))
      (node (ref "U5") (pin "47") (pinfunction "SW5B_47") (pintype "passive"))
    )
    (net (code "50") (name "/CH39") (class "Default")
      (node (ref "U$1") (pin "A26") (pinfunction "A26_A26") (pintype "passive"))
      (node (ref "U5") (pin "45") (pinfunction "SW6B_45") (pintype "passive"))
    )
    (net (code "51") (name "/CH40") (class "Default")
      (node (ref "U$1") (pin "A25") (pinfunction "A25_A25") (pintype "passive"))
      (node (ref "U5") (pin "43") (pinfunction "SW7B_43") (pintype "passive"))
    )
    (net (code "52") (name "/CH41") (class "Default")
      (node (ref "U$1") (pin "B25") (pinfunction "B25_B25") (pintype "passive"))
      (node (ref "U5") (pin "41") (pinfunction "SW8B_41") (pintype "passive"))
    )
    (net (code "53") (name "/CH42") (class "Default")
      (node (ref "U$1") (pin "B24") (pinfunction "B24_B24") (pintype "passive"))
      (node (ref "U5") (pin "39") (pinfunction "SW9B_39") (pintype "passive"))
    )
    (net (code "54") (name "/CH43") (class "Default")
      (node (ref "U$1") (pin "B23") (pinfunction "B23_B23") (pintype "passive"))
      (node (ref "U5") (pin "37") (pinfunction "SW10B_37") (pintype "passive"))
    )
    (net (code "55") (name "/CH44") (class "Default")
      (node (ref "U$1") (pin "A23") (pinfunction "A23_A23") (pintype "passive"))
      (node (ref "U5") (pin "33") (pinfunction "SW11B_33") (pintype "passive"))
    )
    (net (code "56") (name "/CH45") (class "Default")
      (node (ref "U$1") (pin "A22") (pinfunction "A22_A22") (pintype "passive"))
      (node (ref "U5") (pin "31") (pinfunction "SW12B_31") (pintype "passive"))
    )
    (net (code "57") (name "/CH46") (class "Default")
      (node (ref "U$1") (pin "A21") (pinfunction "A21_A21") (pintype "passive"))
      (node (ref "U5") (pin "29") (pinfunction "SW13B_29") (pintype "passive"))
    )
    (net (code "58") (name "/CH47") (class "Default")
      (node (ref "U$1") (pin "B21") (pinfunction "B21_B21") (pintype "passive"))
      (node (ref "U5") (pin "27") (pinfunction "SW14B_27") (pintype "passive"))
    )
    (net (code "59") (name "/CH48") (class "Default")
      (node (ref "U$1") (pin "B20") (pinfunction "B20_B20") (pintype "passive"))
      (node (ref "U5") (pin "25") (pinfunction "SW15B_25") (pintype "passive"))
    )
    (net (code "60") (name "/CH49") (class "Default")
      (node (ref "U$1") (pin "A18") (pinfunction "A18_A18") (pintype "passive"))
      (node (ref "U6") (pin "11") (pinfunction "SW0B_11") (pintype "passive"))
    )
    (net (code "61") (name "/CH50") (class "Default")
      (node (ref "U$1") (pin "A17") (pinfunction "A17_A17") (pintype "passive"))
      (node (ref "U6") (pin "9") (pinfunction "SW1B_9") (pintype "passive"))
    )
    (net (code "62") (name "/CH51") (class "Default")
      (node (ref "U$1") (pin "B17") (pinfunction "B17_B17") (pintype "passive"))
      (node (ref "U6") (pin "7") (pinfunction "SW2B_7") (pintype "passive"))
    )
    (net (code "63") (name "/CH52") (class "Default")
      (node (ref "U$1") (pin "B16") (pinfunction "B16_B16") (pintype "passive"))
      (node (ref "U6") (pin "5") (pinfunction "SW3B_5") (pintype "passive"))
    )
    (net (code "64") (name "/CH53") (class "Default")
      (node (ref "U$1") (pin "B15") (pinfunction "B15_B15") (pintype "passive"))
      (node (ref "U6") (pin "3") (pinfunction "SW4B_3") (pintype "passive"))
    )
    (net (code "65") (name "/CH54") (class "Default")
      (node (ref "U$1") (pin "A15") (pinfunction "A15_A15") (pintype "passive"))
      (node (ref "U6") (pin "47") (pinfunction "SW5B_47") (pintype "passive"))
    )
    (net (code "66") (name "/CH55") (class "Default")
      (node (ref "U$1") (pin "A14") (pinfunction "A14_A14") (pintype "passive"))
      (node (ref "U6") (pin "45") (pinfunction "SW6B_45") (pintype "passive"))
    )
    (net (code "67") (name "/CH56") (class "Default")
      (node (ref "U$1") (pin "A13") (pinfunction "A13_A13") (pintype "passive"))
      (node (ref "U6") (pin "43") (pinfunction "SW7B_43") (pintype "passive"))
    )
    (net (code "68") (name "/CH57") (class "Default")
      (node (ref "U$1") (pin "B13") (pinfunction "B13_B13") (pintype "passive"))
      (node (ref "U6") (pin "41") (pinfunction "SW8B_41") (pintype "passive"))
    )
    (net (code "69") (name "/CH58") (class "Default")
      (node (ref "U$1") (pin "B12") (pinfunction "B12_B12") (pintype "passive"))
      (node (ref "U6") (pin "39") (pinfunction "SW9B_39") (pintype "passive"))
    )
    (net (code "70") (name "/CH59") (class "Default")
      (node (ref "U$1") (pin "B11") (pinfunction "B11_B11") (pintype "passive"))
      (node (ref "U6") (pin "37") (pinfunction "SW10B_37") (pintype "passive"))
    )
    (net (code "71") (name "/CH60") (class "Default")
      (node (ref "U$1") (pin "A11") (pinfunction "A11_A11") (pintype "passive"))
      (node (ref "U6") (pin "33") (pinfunction "SW11B_33") (pintype "passive"))
    )
    (net (code "72") (name "/CH61") (class "Default")
      (node (ref "R48") (pin "2") (pinfunction "2_2") (pintype "passive"))
      (node (ref "U$1") (pin "A10") (pinfunction "A10_A10") (pintype "passive"))
      (node (ref "U6") (pin "31") (pinfunction "SW12B_31") (pintype "passive"))
    )
    (net (code "73") (name "/CH62") (class "Default")
      (node (ref "R44") (pin "2") (pinfunction "2_2") (pintype "passive"))
      (node (ref "U$1") (pin "A9") (pinfunction "A9_A9") (pintype "passive"))
      (node (ref "U6") (pin "29") (pinfunction "SW13B_29") (pintype "passive"))
    )
    (net (code "74") (name "/CH63") (class "Default")
      (node (ref "R45") (pin "2") (pinfunction "2_2") (pintype "passive"))
      (node (ref "U$1") (pin "B9") (pinfunction "B9_B9") (pintype "passive"))
      (node (ref "U6") (pin "27") (pinfunction "SW14B_27") (pintype "passive"))
    )
    (net (code "75") (name "/CH64") (class "Default")
      (node (ref "R49") (pin "2") (pinfunction "2_2") (pintype "passive"))
      (node (ref "U$1") (pin "B8") (pinfunction "B8_B8") (pintype "passive"))
      (node (ref "U6") (pin "25") (pinfunction "SW15B_25") (pintype "passive"))
    )
    (net (code "76") (name "/CH65") (class "Default")
      (node (ref "R50") (pin "2") (pinfunction "2_2") (pintype "passive"))
      (node (ref "U$1") (pin "C54") (pinfunction "C54_C54") (pintype "passive"))
      (node (ref "U7") (pin "11") (pinfunction "SW0B_11") (pintype "passive"))
    )
    (net (code "77") (name "/CH66") (class "Default")
      (node (ref "R51") (pin "2") (pinfunction "2_2") (pintype "passive"))
      (node (ref "U$1") (pin "C53") (pinfunction "C53_C53") (pintype "passive"))
      (node (ref "U7") (pin "9") (pinfunction "SW1B_9") (pintype "passive"))
    )
    (net (code "78") (name "/CH67") (class "Default")
      (node (ref "R52") (pin "2") (pinfunction "2_2") (pintype "passive"))
      (node (ref "U$1") (pin "D53") (pinfunction "D53_D53") (pintype "passive"))
      (node (ref "U7") (pin "7") (pinfunction "SW2B_7") (pintype "passive"))
    )
    (net (code "79") (name "/CH68") (class "Default")
      (node (ref "R53") (pin "2") (pinfunction "2_2") (pintype "passive"))
      (node (ref "U$1") (pin "D52") (pinfunction "D52_D52") (pintype "passive"))
      (node (ref "U7") (pin "5") (pinfunction "SW3B_5") (pintype "passive"))
    )
    (net (code "80") (name "/CH69") (class "Default")
      (node (ref "U$1") (pin "D51") (pinfunction "D51_D51") (pintype "passive"))
      (node (ref "U7") (pin "3") (pinfunction "SW4B_3") (pintype "passive"))
    )
    (net (code "81") (name "/CH70") (class "Default")
      (node (ref "U$1") (pin "C51") (pinfunction "C51_C51") (pintype "passive"))
      (node (ref "U7") (pin "47") (pinfunction "SW5B_47") (pintype "passive"))
    )
    (net (code "82") (name "/CH71") (class "Default")
      (node (ref "U$1") (pin "C50") (pinfunction "C50_C50") (pintype "passive"))
      (node (ref "U7") (pin "45") (pinfunction "SW6B_45") (pintype "passive"))
    )
    (net (code "83") (name "/CH72") (class "Default")
      (node (ref "U$1") (pin "C49") (pinfunction "C49_C49") (pintype "passive"))
      (node (ref "U7") (pin "43") (pinfunction "SW7B_43") (pintype "passive"))
    )
    (net (code "84") (name "/CH73") (class "Default")
      (node (ref "U$1") (pin "D49") (pinfunction "D49_D49") (pintype "passive"))
      (node (ref "U7") (pin "41") (pinfunction "SW8B_41") (pintype "passive"))
    )
    (net (code "85") (name "/CH74") (class "Default")
      (node (ref "U$1") (pin "D48") (pinfunction "D48_D48") (pintype "passive"))
      (node (ref "U7") (pin "39") (pinfunction "SW9B_39") (pintype "passive"))
    )
    (net (code "86") (name "/CH75") (class "Default")
      (node (ref "U$1") (pin "D47") (pinfunction "D47_D47") (pintype "passive"))
      (node (ref "U7") (pin "37") (pinfunction "SW10B_37") (pintype "passive"))
    )
    (net (code "87") (name "/CH76") (class "Default")
      (node (ref "U$1") (pin "C47") (pinfunction "C47_C47") (pintype "passive"))
      (node (ref "U7") (pin "33") (pinfunction "SW11B_33") (pintype "passive"))
    )
    (net (code "88") (name "/CH77") (class "Default")
      (node (ref "U$1") (pin "C46") (pinfunction "C46_C46") (pintype "passive"))
      (node (ref "U7") (pin "31") (pinfunction "SW12B_31") (pintype "passive"))
    )
    (net (code "89") (name "/CH78") (class "Default")
      (node (ref "U$1") (pin "C45") (pinfunction "C45_C45") (pintype "passive"))
      (node (ref "U7") (pin "29") (pinfunction "SW13B_29") (pintype "passive"))
    )
    (net (code "90") (name "/CH79") (class "Default")
      (node (ref "U$1") (pin "D45") (pinfunction "D45_D45") (pintype "passive"))
      (node (ref "U7") (pin "27") (pinfunction "SW14B_27") (pintype "passive"))
    )
    (net (code "91") (name "/CH80") (class "Default")
      (node (ref "U$1") (pin "D44") (pinfunction "D44_D44") (pintype "passive"))
      (node (ref "U7") (pin "25") (pinfunction "SW15B_25") (pintype "passive"))
    )
    (net (code "92") (name "/CH81") (class "Default")
      (node (ref "U$1") (pin "C42") (pinfunction "C42_C42") (pintype "passive"))
      (node (ref "U8") (pin "11") (pinfunction "SW0B_11") (pintype "passive"))
    )
    (net (code "93") (name "/CH82") (class "Default")
      (node (ref "U$1") (pin "C41") (pinfunction "C41_C41") (pintype "passive"))
      (node (ref "U8") (pin "9") (pinfunction "SW1B_9") (pintype "passive"))
    )
    (net (code "94") (name "/CH83") (class "Default")
      (node (ref "U$1") (pin "D41") (pinfunction "D41_D41") (pintype "passive"))
      (node (ref "U8") (pin "7") (pinfunction "SW2B_7") (pintype "passive"))
    )
    (net (code "95") (name "/CH84") (class "Default")
      (node (ref "U$1") (pin "D40") (pinfunction "D40_D40") (pintype "passive"))
      (node (ref "U8") (pin "5") (pinfunction "SW3B_5") (pintype "passive"))
    )
    (net (code "96") (name "/CH85") (class "Default")
      (node (ref "U$1") (pin "D39") (pinfunction "D39_D39") (pintype "passive"))
      (node (ref "U8") (pin "3") (pinfunction "SW4B_3") (pintype "passive"))
    )
    (net (code "97") (name "/CH86") (class "Default")
      (node (ref "U$1") (pin "C39") (pinfunction "C39_C39") (pintype "passive"))
      (node (ref "U8") (pin "47") (pinfunction "SW5B_47") (pintype "passive"))
    )
    (net (code "98") (name "/CH87") (class "Default")
      (node (ref "U$1") (pin "C38") (pinfunction "C38_C38") (pintype "passive"))
      (node (ref "U8") (pin "45") (pinfunction "SW6B_45") (pintype "passive"))
    )
    (net (code "99") (name "/CH88") (class "Default")
      (node (ref "U$1") (pin "C37") (pinfunction "C37_C37") (pintype "passive"))
      (node (ref "U8") (pin "43") (pinfunction "SW7B_43") (pintype "passive"))
    )
    (net (code "100") (name "/CH89") (class "Default")
      (node (ref "U$1") (pin "D37") (pinfunction "D37_D37") (pintype "passive"))
      (node (ref "U8") (pin "41") (pinfunction "SW8B_41") (pintype "passive"))
    )
    (net (code "101") (name "/CH90") (class "Default")
      (node (ref "U$1") (pin "D36") (pinfunction "D36_D36") (pintype "passive"))
      (node (ref "U8") (pin "39") (pinfunction "SW9B_39") (pintype "passive"))
    )
    (net (code "102") (name "/CH91") (class "Default")
      (node (ref "U$1") (pin "D35") (pinfunction "D35_D35") (pintype "passive"))
      (node (ref "U8") (pin "37") (pinfunction "SW10B_37") (pintype "passive"))
    )
    (net (code "103") (name "/CH92") (class "Default")
      (node (ref "U$1") (pin "C35") (pinfunction "C35_C35") (pintype "passive"))
      (node (ref "U8") (pin "33") (pinfunction "SW11B_33") (pintype "passive"))
    )
    (net (code "104") (name "/CH93") (class "Default")
      (node (ref "U$1") (pin "C34") (pinfunction "C34_C34") (pintype "passive"))
      (node (ref "U8") (pin "31") (pinfunction "SW12B_31") (pintype "passive"))
    )
    (net (code "105") (name "/CH94") (class "Default")
      (node (ref "U$1") (pin "C33") (pinfunction "C33_C33") (pintype "passive"))
      (node (ref "U8") (pin "29") (pinfunction "SW13B_29") (pintype "passive"))
    )
    (net (code "106") (name "/CH95") (class "Default")
      (node (ref "U$1") (pin "D33") (pinfunction "D33_D33") (pintype "passive"))
      (node (ref "U8") (pin "27") (pinfunction "SW14B_27") (pintype "passive"))
    )
    (net (code "107") (name "/CH96") (class "Default")
      (node (ref "U$1") (pin "D32") (pinfunction "D32_D32") (pintype "passive"))
      (node (ref "U8") (pin "25") (pinfunction "SW15B_25") (pintype "passive"))
    )
    (net (code "108") (name "/CH97") (class "Default")
      (node (ref "U$1") (pin "C30") (pinfunction "C30_C30") (pintype "passive"))
      (node (ref "U9") (pin "11") (pinfunction "SW0B_11") (pintype "passive"))
    )
    (net (code "109") (name "/CH98") (class "Default")
      (node (ref "U$1") (pin "C29") (pinfunction "C29_C29") (pintype "passive"))
      (node (ref "U9") (pin "9") (pinfunction "SW1B_9") (pintype "passive"))
    )
    (net (code "110") (name "/CH99") (class "Default")
      (node (ref "U$1") (pin "D29") (pinfunction "D29_D29") (pintype "passive"))
      (node (ref "U9") (pin "7") (pinfunction "SW2B_7") (pintype "passive"))
    )
    (net (code "111") (name "/CH100") (class "Default")
      (node (ref "U$1") (pin "D28") (pinfunction "D28_D28") (pintype "passive"))
      (node (ref "U9") (pin "5") (pinfunction "SW3B_5") (pintype "passive"))
    )
    (net (code "112") (name "/CH101") (class "Default")
      (node (ref "U$1") (pin "D27") (pinfunction "D27_D27") (pintype "passive"))
      (node (ref "U9") (pin "3") (pinfunction "SW4B_3") (pintype "passive"))
    )
    (net (code "113") (name "/CH102") (class "Default")
      (node (ref "U$1") (pin "C27") (pinfunction "C27_C27") (pintype "passive"))
      (node (ref "U9") (pin "47") (pinfunction "SW5B_47") (pintype "passive"))
    )
    (net (code "114") (name "/CH103") (class "Default")
      (node (ref "U$1") (pin "C26") (pinfunction "C26_C26") (pintype "passive"))
      (node (ref "U9") (pin "45") (pinfunction "SW6B_45") (pintype "passive"))
    )
    (net (code "115") (name "/CH104") (class "Default")
      (node (ref "U$1") (pin "C25") (pinfunction "C25_C25") (pintype "passive"))
      (node (ref "U9") (pin "43") (pinfunction "SW7B_43") (pintype "passive"))
    )
    (net (code "116") (name "/CH105") (class "Default")
      (node (ref "U$1") (pin "D25") (pinfunction "D25_D25") (pintype "passive"))
      (node (ref "U9") (pin "41") (pinfunction "SW8B_41") (pintype "passive"))
    )
    (net (code "117") (name "/CH106") (class "Default")
      (node (ref "U$1") (pin "D24") (pinfunction "D24_D24") (pintype "passive"))
      (node (ref "U9") (pin "39") (pinfunction "SW9B_39") (pintype "passive"))
    )
    (net (code "118") (name "/CH107") (class "Default")
      (node (ref "U$1") (pin "D23") (pinfunction "D23_D23") (pintype "passive"))
      (node (ref "U9") (pin "37") (pinfunction "SW10B_37") (pintype "passive"))
    )
    (net (code "119") (name "/CH108") (class "Default")
      (node (ref "U$1") (pin "C23") (pinfunction "C23_C23") (pintype "passive"))
      (node (ref "U9") (pin "33") (pinfunction "SW11B_33") (pintype "passive"))
    )
    (net (code "120") (name "/CH109") (class "Default")
      (node (ref "U$1") (pin "C22") (pinfunction "C22_C22") (pintype "passive"))
      (node (ref "U9") (pin "31") (pinfunction "SW12B_31") (pintype "passive"))
    )
    (net (code "121") (name "/CH110") (class "Default")
      (node (ref "U$1") (pin "C21") (pinfunction "C21_C21") (pintype "passive"))
      (node (ref "U9") (pin "29") (pinfunction "SW13B_29") (pintype "passive"))
    )
    (net (code "122") (name "/CH111") (class "Default")
      (node (ref "U$1") (pin "D21") (pinfunction "D21_D21") (pintype "passive"))
      (node (ref "U9") (pin "27") (pinfunction "SW14B_27") (pintype "passive"))
    )
    (net (code "123") (name "/CH112") (class "Default")
      (node (ref "U$1") (pin "D20") (pinfunction "D20_D20") (pintype "passive"))
      (node (ref "U9") (pin "25") (pinfunction "SW15B_25") (pintype "passive"))
    )
    (net (code "124") (name "/CH113") (class "Default")
      (node (ref "U$1") (pin "C18") (pinfunction "C18_C18") (pintype "passive"))
      (node (ref "U10") (pin "11") (pinfunction "SW0B_11") (pintype "passive"))
    )
    (net (code "125") (name "/CH114") (class "Default")
      (node (ref "U$1") (pin "C17") (pinfunction "C17_C17") (pintype "passive"))
      (node (ref "U10") (pin "9") (pinfunction "SW1B_9") (pintype "passive"))
    )
    (net (code "126") (name "/CH115") (class "Default")
      (node (ref "U$1") (pin "D17") (pinfunction "D17_D17") (pintype "passive"))
      (node (ref "U10") (pin "7") (pinfunction "SW2B_7") (pintype "passive"))
    )
    (net (code "127") (name "/CH116") (class "Default")
      (node (ref "U$1") (pin "D16") (pinfunction "D16_D16") (pintype "passive"))
      (node (ref "U10") (pin "5") (pinfunction "SW3B_5") (pintype "passive"))
    )
    (net (code "128") (name "/CH117") (class "Default")
      (node (ref "U$1") (pin "D15") (pinfunction "D15_D15") (pintype "passive"))
      (node (ref "U10") (pin "3") (pinfunction "SW4B_3") (pintype "passive"))
    )
    (net (code "129") (name "/CH118") (class "Default")
      (node (ref "U$1") (pin "C15") (pinfunction "C15_C15") (pintype "passive"))
      (node (ref "U10") (pin "47") (pinfunction "SW5B_47") (pintype "passive"))
    )
    (net (code "130") (name "/CH119") (class "Default")
      (node (ref "U$1") (pin "C14") (pinfunction "C14_C14") (pintype "passive"))
      (node (ref "U10") (pin "45") (pinfunction "SW6B_45") (pintype "passive"))
    )
    (net (code "131") (name "/CH120") (class "Default")
      (node (ref "U$1") (pin "C13") (pinfunction "C13_C13") (pintype "passive"))
      (node (ref "U10") (pin "43") (pinfunction "SW7B_43") (pintype "passive"))
    )
    (net (code "132") (name "/CH121") (class "Default")
      (node (ref "U$1") (pin "D13") (pinfunction "D13_D13") (pintype "passive"))
      (node (ref "U10") (pin "41") (pinfunction "SW8B_41") (pintype "passive"))
    )
    (net (code "133") (name "/CH122") (class "Default")
      (node (ref "U$1") (pin "D12") (pinfunction "D12_D12") (pintype "passive"))
      (node (ref "U10") (pin "39") (pinfunction "SW9B_39") (pintype "passive"))
    )
    (net (code "134") (name "/CH123") (class "Default")
      (node (ref "U$1") (pin "D11") (pinfunction "D11_D11") (pintype "passive"))
      (node (ref "U10") (pin "37") (pinfunction "SW10B_37") (pintype "passive"))
    )
    (net (code "135") (name "/CH124") (class "Default")
      (node (ref "U$1") (pin "C11") (pinfunction "C11_C11") (pintype "passive"))
      (node (ref "U10") (pin "33") (pinfunction "SW11B_33") (pintype "passive"))
    )
    (net (code "136") (name "/CH125") (class "Default")
      (node (ref "U$1") (pin "C10") (pinfunction "C10_C10") (pintype "passive"))
      (node (ref "U10") (pin "31") (pinfunction "SW12B_31") (pintype "passive"))
    )
    (net (code "137") (name "/CH126") (class "Default")
      (node (ref "U$1") (pin "C9") (pinfunction "C9_C9") (pintype "passive"))
      (node (ref "U10") (pin "29") (pinfunction "SW13B_29") (pintype "passive"))
    )
    (net (code "138") (name "/CH127") (class "Default")
      (node (ref "U$1") (pin "D9") (pinfunction "D9_D9") (pintype "passive"))
      (node (ref "U10") (pin "27") (pinfunction "SW14B_27") (pintype "passive"))
    )
    (net (code "139") (name "/CH128") (class "Default")
      (node (ref "U$1") (pin "D8") (pinfunction "D8_D8") (pintype "passive"))
      (node (ref "U10") (pin "25") (pinfunction "SW15B_25") (pintype "passive"))
    )
    (net (code "140") (name "/CK_N") (class "Default")
      (node (ref "J2") (pin "G3") (pinfunction "G3_G3") (pintype "passive"))
      (node (ref "U1") (pin "M24") (pinfunction "CLKIN-_M24") (pintype "passive"))
    )
    (net (code "141") (name "/CK_P") (class "Default")
      (node (ref "J2") (pin "G2") (pinfunction "G2_G2") (pintype "passive"))
      (node (ref "U1") (pin "L24") (pinfunction "CLKIN+_L24") (pintype "passive"))
    )
    (net (code "142") (name "/CL+") (class "Default")
      (node (ref "R25") (pin "2") (pinfunction "2_2") (pintype "passive"))
      (node (ref "SV2") (pin "6") (pinfunction "6_6") (pintype "passive"))
      (node (ref "U1") (pin "A20") (pinfunction "CI+_A20") (pintype "passive"))
    )
    (net (code "143") (name "/CL-") (class "Default")
      (node (ref "R24") (pin "2") (pinfunction "2_2") (pintype "passive"))
      (node (ref "SV2") (pin "7") (pinfunction "7_7") (pintype "passive"))
      (node (ref "U1") (pin "B20") (pinfunction "CI-_B20") (pintype "passive"))
    )
    (net (code "144") (name "/CLK") (class "Default")
      (node (ref "SV10") (pin "19") (pinfunction "19_19") (pintype "passive"))
      (node (ref "SV10") (pin "20") (pinfunction "20_20") (pintype "passive"))
      (node (ref "U$2") (pin "1") (pinfunction "CLKIN_1") (pintype "passive"))
    )
    (net (code "145") (name "/CLK1") (class "Default")
      (node (ref "U$2") (pin "3") (pinfunction "Y0_3") (pintype "passive"))
      (node (ref "U3") (pin "20") (pinfunction "CLK_20") (pintype "passive"))
    )
    (net (code "146") (name "/CLK2") (class "Default")
      (node (ref "U$2") (pin "16") (pinfunction "Y1_16") (pintype "passive"))
      (node (ref "U4") (pin "20") (pinfunction "CLK_20") (pintype "passive"))
    )
    (net (code "147") (name "/CLK3") (class "Default")
      (node (ref "U$2") (pin "13") (pinfunction "Y2_13") (pintype "passive"))
      (node (ref "U5") (pin "20") (pinfunction "CLK_20") (pintype "passive"))
    )
    (net (code "148") (name "/CLK4") (class "Default")
      (node (ref "U$2") (pin "15") (pinfunction "Y3_15") (pintype "passive"))
      (node (ref "U6") (pin "20") (pinfunction "CLK_20") (pintype "passive"))
    )
    (net (code "149") (name "/CLK5") (class "Default")
      (node (ref "U$2") (pin "6") (pinfunction "Y4_6") (pintype "passive"))
      (node (ref "U7") (pin "20") (pinfunction "CLK_20") (pintype "passive"))
    )
    (net (code "150") (name "/CLK6") (class "Default")
      (node (ref "U$2") (pin "11") (pinfunction "Y5_11") (pintype "passive"))
      (node (ref "U8") (pin "20") (pinfunction "CLK_20") (pintype "passive"))
    )
    (net (code "151") (name "/CLK7") (class "Default")
      (node (ref "U$2") (pin "8") (pinfunction "Y6_8") (pintype "passive"))
      (node (ref "U9") (pin "20") (pinfunction "CLK_20") (pintype "passive"))
    )
    (net (code "152") (name "/CLK8") (class "Default")
      (node (ref "U$2") (pin "9") (pinfunction "Y7_9") (pintype "passive"))
      (node (ref "U10") (pin "20") (pinfunction "CLK_20") (pintype "passive"))
    )
    (net (code "153") (name "/CLK_N") (class "Default")
      (node (ref "J2") (pin "G7") (pinfunction "G7_G7") (pintype "passive"))
      (node (ref "U1") (pin "F28") (pinfunction "CLKOUT-_F28") (pintype "passive"))
    )
    (net (code "154") (name "/CLK_P") (class "Default")
      (node (ref "J2") (pin "G6") (pinfunction "G6_G6") (pintype "passive"))
      (node (ref "U1") (pin "F27") (pinfunction "CLKOUT+_F27") (pintype "passive"))
    )
    (net (code "155") (name "/CLR1") (class "Default")
      (node (ref "SV10") (pin "2") (pinfunction "2_2") (pintype "passive"))
      (node (ref "U3") (pin "22") (pinfunction "CLR_22") (pintype "passive"))
    )
    (net (code "156") (name "/CLR2") (class "Default")
      (node (ref "SV10") (pin "4") (pinfunction "4_4") (pintype "passive"))
      (node (ref "U4") (pin "22") (pinfunction "CLR_22") (pintype "passive"))
    )
    (net (code "157") (name "/CLR3") (class "Default")
      (node (ref "SV10") (pin "6") (pinfunction "6_6") (pintype "passive"))
      (node (ref "U5") (pin "22") (pinfunction "CLR_22") (pintype "passive"))
    )
    (net (code "158") (name "/CLR4") (class "Default")
      (node (ref "SV10") (pin "8") (pinfunction "8_8") (pintype "passive"))
      (node (ref "U6") (pin "22") (pinfunction "CLR_22") (pintype "passive"))
    )
    (net (code "159") (name "/CLR5") (class "Default")
      (node (ref "SV10") (pin "10") (pinfunction "10_10") (pintype "passive"))
      (node (ref "U7") (pin "22") (pinfunction "CLR_22") (pintype "passive"))
    )
    (net (code "160") (name "/CLR6") (class "Default")
      (node (ref "SV10") (pin "12") (pinfunction "12_12") (pintype "passive"))
      (node (ref "U8") (pin "22") (pinfunction "CLR_22") (pintype "passive"))
    )
    (net (code "161") (name "/CLR7") (class "Default")
      (node (ref "SV10") (pin "14") (pinfunction "14_14") (pintype "passive"))
      (node (ref "U9") (pin "22") (pinfunction "CLR_22") (pintype "passive"))
    )
    (net (code "162") (name "/CLR8") (class "Default")
      (node (ref "SV10") (pin "16") (pinfunction "16_16") (pintype "passive"))
      (node (ref "U10") (pin "22") (pinfunction "CLR_22") (pintype "passive"))
    )
    (net (code "163") (name "/CQ+") (class "Default")
      (node (ref "R27") (pin "2") (pinfunction "2_2") (pintype "passive"))
      (node (ref "SV2") (pin "4") (pinfunction "4_4") (pintype "passive"))
      (node (ref "U1") (pin "A21") (pinfunction "CQ+_A21") (pintype "passive"))
    )
    (net (code "164") (name "/CQ-") (class "Default")
      (node (ref "R26") (pin "2") (pinfunction "2_2") (pintype "passive"))
      (node (ref "SV2") (pin "5") (pinfunction "5_5") (pintype "passive"))
      (node (ref "U1") (pin "B21") (pinfunction "CQ-_B21") (pintype "passive"))
    )
    (net (code "165") (name "/DIN1") (class "Default")
      (node (ref "SV10") (pin "17") (pinfunction "17_17") (pintype "passive"))
      (node (ref "U3") (pin "19") (pinfunction "DIN_19") (pintype "passive"))
    )
    (net (code "166") (name "/DOUT1") (class "Default")
      (node (ref "U3") (pin "23") (pinfunction "DOUT_23") (pintype "output"))
      (node (ref "U4") (pin "19") (pinfunction "DIN_19") (pintype "passive"))
    )
    (net (code "167") (name "/DOUT2") (class "Default")
      (node (ref "U4") (pin "23") (pinfunction "DOUT_23") (pintype "output"))
      (node (ref "U5") (pin "19") (pinfunction "DIN_19") (pintype "passive"))
    )
    (net (code "168") (name "/DOUT3") (class "Default")
      (node (ref "U5") (pin "23") (pinfunction "DOUT_23") (pintype "output"))
      (node (ref "U6") (pin "19") (pinfunction "DIN_19") (pintype "passive"))
    )
    (net (code "169") (name "/DOUT4") (class "Default")
      (node (ref "U6") (pin "23") (pinfunction "DOUT_23") (pintype "output"))
      (node (ref "U7") (pin "19") (pinfunction "DIN_19") (pintype "passive"))
    )
    (net (code "170") (name "/DOUT5") (class "Default")
      (node (ref "U7") (pin "23") (pinfunction "DOUT_23") (pintype "output"))
      (node (ref "U8") (pin "19") (pinfunction "DIN_19") (pintype "passive"))
    )
    (net (code "171") (name "/DOUT6") (class "Default")
      (node (ref "U8") (pin "23") (pinfunction "DOUT_23") (pintype "output"))
      (node (ref "U9") (pin "19") (pinfunction "DIN_19") (pintype "passive"))
    )
    (net (code "172") (name "/DOUT7") (class "Default")
      (node (ref "U10") (pin "19") (pinfunction "DIN_19") (pintype "passive"))
      (node (ref "U9") (pin "23") (pinfunction "DOUT_23") (pintype "output"))
    )
    (net (code "173") (name "/DOUT8") (class "Default")
      (node (ref "SV10") (pin "18") (pinfunction "18_18") (pintype "passive"))
      (node (ref "U10") (pin "23") (pinfunction "DOUT_23") (pintype "output"))
    )
    (net (code "174") (name "/EN1") (class "Default")
      (node (ref "SV9") (pin "6") (pinfunction "6_6") (pintype "passive"))
      (node (ref "U20") (pin "4") (pinfunction "EN_4") (pintype "passive"))
    )
    (net (code "175") (name "/FRAME+") (class "Default")
      (node (ref "SV6") (pin "1") (pinfunction "1_1") (pintype "passive"))
      (node (ref "U1") (pin "G27") (pinfunction "FRAME+_G27") (pintype "passive"))
    )
    (net (code "176") (name "/FRAME-") (class "Default")
      (node (ref "SV6") (pin "2") (pinfunction "2_2") (pintype "passive"))
      (node (ref "U1") (pin "G28") (pinfunction "FRAME-_G28") (pintype "passive"))
    )
    (net (code "177") (name "/ID1") (class "Default")
      (node (ref "R36") (pin "1") (pinfunction "1_1") (pintype "passive"))
      (node (ref "SV1") (pin "1") (pinfunction "1_1") (pintype "passive"))
      (node (ref "U$1") (pin "A63") (pinfunction "A63_A63") (pintype "passive"))
    )
    (net (code "178") (name "/ID2") (class "Default")
      (node (ref "R37") (pin "1") (pinfunction "1_1") (pintype "passive"))
      (node (ref "SV1") (pin "2") (pinfunction "2_2") (pintype "passive"))
      (node (ref "U$1") (pin "A59") (pinfunction "A59_A59") (pintype "passive"))
    )
    (net (code "179") (name "/ID3") (class "Default")
      (node (ref "R38") (pin "1") (pinfunction "1_1") (pintype "passive"))
      (node (ref "SV1") (pin "3") (pinfunction "3_3") (pintype "passive"))
      (node (ref "U$1") (pin "B63") (pinfunction "B63_B63") (pintype "passive"))
    )
    (net (code "180") (name "/ID4") (class "Default")
      (node (ref "R39") (pin "1") (pinfunction "1_1") (pintype "passive"))
      (node (ref "SV1") (pin "4") (pinfunction "4_4") (pintype "passive"))
      (node (ref "U$1") (pin "B59") (pinfunction "B59_B59") (pintype "passive"))
    )
    (net (code "181") (name "/ID5") (class "Default")
      (node (ref "R40") (pin "1") (pinfunction "1_1") (pintype "passive"))
      (node (ref "SV1") (pin "5") (pinfunction "5_5") (pintype "passive"))
      (node (ref "U$1") (pin "C63") (pinfunction "C63_C63") (pintype "passive"))
    )
    (net (code "182") (name "/ID6") (class "Default")
      (node (ref "R41") (pin "1") (pinfunction "1_1") (pintype "passive"))
      (node (ref "SV1") (pin "6") (pinfunction "6_6") (pintype "passive"))
      (node (ref "U$1") (pin "C59") (pinfunction "C59_C59") (pintype "passive"))
    )
    (net (code "183") (name "/ID7") (class "Default")
      (node (ref "R42") (pin "1") (pinfunction "1_1") (pintype "passive"))
      (node (ref "SV1") (pin "7") (pinfunction "7_7") (pintype "passive"))
      (node (ref "U$1") (pin "D63") (pinfunction "D63_D63") (pintype "passive"))
    )
    (net (code "184") (name "/ID8") (class "Default")
      (node (ref "R43") (pin "1") (pinfunction "1_1") (pintype "passive"))
      (node (ref "SV1") (pin "8") (pinfunction "8_8") (pintype "passive"))
      (node (ref "U$1") (pin "D59") (pinfunction "D59_D59") (pintype "passive"))
    )
    (net (code "185") (name "/LO+") (class "Default")
      (node (ref "SV2") (pin "1") (pinfunction "1_1") (pintype "passive"))
      (node (ref "U1") (pin "A22") (pinfunction "LO+_A22") (pintype "passive"))
    )
    (net (code "186") (name "/LO-") (class "Default")
      (node (ref "SV2") (pin "2") (pinfunction "2_2") (pintype "passive"))
      (node (ref "U1") (pin "B22") (pinfunction "LO-_B22") (pintype "passive"))
    )
    (net (code "187") (name "/LOON") (class "Default")
      (node (ref "SV2") (pin "3") (pinfunction "3_3") (pintype "passive"))
      (node (ref "U1") (pin "B23") (pinfunction "LOON_B23") (pintype "passive"))
    )
    (net (code "188") (name "/N0") (class "Default")
      (node (ref "PULSE_1") (pin "3") (pinfunction "3_3") (pintype "passive"))
      (node (ref "R15") (pin "1") (pinfunction "1_1") (pintype "passive"))
    )
    (net (code "189") (name "/N1") (class "Default")
      (node (ref "PULSE_1") (pin "7") (pinfunction "7_7") (pintype "passive"))
      (node (ref "R1") (pin "1") (pinfunction "1_1") (pintype "passive"))
    )
    (net (code "190") (name "/N2") (class "Default")
      (node (ref "PULSE_1") (pin "11") (pinfunction "11_11") (pintype "passive"))
      (node (ref "R4") (pin "2") (pinfunction "2_2") (pintype "passive"))
    )
    (net (code "191") (name "/N3") (class "Default")
      (node (ref "PULSE_1") (pin "15") (pinfunction "15_15") (pintype "passive"))
      (node (ref "R6") (pin "2") (pinfunction "2_2") (pintype "passive"))
    )
    (net (code "192") (name "/N4") (class "Default")
      (node (ref "PULSE_5") (pin "3") (pinfunction "3_3") (pintype "passive"))
      (node (ref "R8") (pin "2") (pinfunction "2_2") (pintype "passive"))
    )
    (net (code "193") (name "/N5") (class "Default")
      (node (ref "PULSE_5") (pin "7") (pinfunction "7_7") (pintype "passive"))
      (node (ref "R10") (pin "2") (pinfunction "2_2") (pintype "passive"))
    )
    (net (code "194") (name "/N6") (class "Default")
      (node (ref "PULSE_5") (pin "11") (pinfunction "11_11") (pintype "passive"))
      (node (ref "R12") (pin "2") (pinfunction "2_2") (pintype "passive"))
    )
    (net (code "195") (name "/N7") (class "Default")
      (node (ref "PULSE_5") (pin "15") (pinfunction "15_15") (pintype "passive"))
      (node (ref "R14") (pin "2") (pinfunction "2_2") (pintype "passive"))
    )
    (net (code "196") (name "/O1_N") (class "Default")
      (node (ref "J2") (pin "H8") (pinfunction "H8_H8") (pintype "passive"))
      (node (ref "U1") (pin "B28") (pinfunction "OUT1-_B28") (pintype "passive"))
    )
    (net (code "197") (name "/O1_P") (class "Default")
      (node (ref "J2") (pin "H7") (pinfunction "H7_H7") (pintype "passive"))
      (node (ref "U1") (pin "B27") (pinfunction "OUT1+_B27") (pintype "passive"))
    )
    (net (code "198") (name "/O2_N") (class "Default")
      (node (ref "J2") (pin "G10") (pinfunction "G10_G10") (pintype "passive"))
      (node (ref "U1") (pin "C28") (pinfunction "OUT2-_C28") (pintype "passive"))
    )
    (net (code "199") (name "/O2_P") (class "Default")
      (node (ref "J2") (pin "G9") (pinfunction "G9_G9") (pintype "passive"))
      (node (ref "U1") (pin "C27") (pinfunction "OUT2+_C27") (pintype "passive"))
    )
    (net (code "200") (name "/O3_N") (class "Default")
      (node (ref "J2") (pin "H11") (pinfunction "H11_H11") (pintype "passive"))
      (node (ref "U1") (pin "D28") (pinfunction "OUT3-_D28") (pintype "passive"))
    )
    (net (code "201") (name "/O3_P") (class "Default")
      (node (ref "J2") (pin "H10") (pinfunction "H10_H10") (pintype "passive"))
      (node (ref "U1") (pin "D27") (pinfunction "OUT3+_D27") (pintype "passive"))
    )
    (net (code "202") (name "/O4_N") (class "Default")
      (node (ref "J2") (pin "G13") (pinfunction "G13_G13") (pintype "passive"))
      (node (ref "U1") (pin "E28") (pinfunction "OUT4-_E28") (pintype "passive"))
    )
    (net (code "203") (name "/O4_P") (class "Default")
      (node (ref "J2") (pin "G12") (pinfunction "G12_G12") (pintype "passive"))
      (node (ref "U1") (pin "E27") (pinfunction "OUT4+_E27") (pintype "passive"))
    )
    (net (code "204") (name "/O5_N") (class "Default")
      (node (ref "J2") (pin "H14") (pinfunction "H14_H14") (pintype "passive"))
      (node (ref "U1") (pin "H28") (pinfunction "OUT5-_H28") (pintype "passive"))
    )
    (net (code "205") (name "/O5_P") (class "Default")
      (node (ref "J2") (pin "H13") (pinfunction "H13_H13") (pintype "passive"))
      (node (ref "U1") (pin "H27") (pinfunction "OUT5+_H27") (pintype "passive"))
    )
    (net (code "206") (name "/O6_N") (class "Default")
      (node (ref "J2") (pin "G16") (pinfunction "G16_G16") (pintype "passive"))
      (node (ref "U1") (pin "J28") (pinfunction "OUT6-_J28") (pintype "passive"))
    )
    (net (code "207") (name "/O6_P") (class "Default")
      (node (ref "J2") (pin "G15") (pinfunction "G15_G15") (pintype "passive"))
      (node (ref "U1") (pin "J27") (pinfunction "OUT6+_J27") (pintype "passive"))
    )
    (net (code "208") (name "/O7_N") (class "Default")
      (node (ref "J2") (pin "H17") (pinfunction "H17_H17") (pintype "passive"))
      (node (ref "U1") (pin "K28") (pinfunction "OUT7-_K28") (pintype "passive"))
    )
    (net (code "209") (name "/O7_P") (class "Default")
      (node (ref "J2") (pin "H16") (pinfunction "H16_H16") (pintype "passive"))
      (node (ref "U1") (pin "K27") (pinfunction "OUT7+_K27") (pintype "passive"))
    )
    (net (code "210") (name "/O8_N") (class "Default")
      (node (ref "J2") (pin "G19") (pinfunction "G19_G19") (pintype "passive"))
      (node (ref "U1") (pin "L28") (pinfunction "OUT8-_L28") (pintype "passive"))
    )
    (net (code "211") (name "/O8_P") (class "Default")
      (node (ref "J2") (pin "G18") (pinfunction "G18_G18") (pintype "passive"))
      (node (ref "U1") (pin "L27") (pinfunction "OUT8+_L27") (pintype "passive"))
    )
    (net (code "212") (name "/P0") (class "Default")
      (node (ref "PULSE_1") (pin "1") (pinfunction "1_1") (pintype "passive"))
      (node (ref "R16") (pin "1") (pinfunction "1_1") (pintype "passive"))
    )
    (net (code "213") (name "/P1") (class "Default")
      (node (ref "PULSE_1") (pin "5") (pinfunction "5_5") (pintype "passive"))
      (node (ref "R2") (pin "1") (pinfunction "1_1") (pintype "passive"))
    )
    (net (code "214") (name "/P2") (class "Default")
      (node (ref "PULSE_1") (pin "9") (pinfunction "9_9") (pintype "passive"))
      (node (ref "R3") (pin "2") (pinfunction "2_2") (pintype "passive"))
    )
    (net (code "215") (name "/P3") (class "Default")
      (node (ref "PULSE_1") (pin "13") (pinfunction "13_13") (pintype "passive"))
      (node (ref "R5") (pin "2") (pinfunction "2_2") (pintype "passive"))
    )
    (net (code "216") (name "/P4") (class "Default")
      (node (ref "PULSE_5") (pin "1") (pinfunction "1_1") (pintype "passive"))
      (node (ref "R7") (pin "2") (pinfunction "2_2") (pintype "passive"))
    )
    (net (code "217") (name "/P5") (class "Default")
      (node (ref "PULSE_5") (pin "5") (pinfunction "5_5") (pintype "passive"))
      (node (ref "R9") (pin "2") (pinfunction "2_2") (pintype "passive"))
    )
    (net (code "218") (name "/P6") (class "Default")
      (node (ref "PULSE_5") (pin "9") (pinfunction "9_9") (pintype "passive"))
      (node (ref "R11") (pin "2") (pinfunction "2_2") (pintype "passive"))
    )
    (net (code "219") (name "/P7") (class "Default")
      (node (ref "PULSE_5") (pin "13") (pinfunction "13_13") (pintype "passive"))
      (node (ref "R13") (pin "2") (pinfunction "2_2") (pintype "passive"))
    )
    (net (code "220") (name "/PLL_CLK+") (class "Default")
      (node (ref "C49") (pin "2") (pinfunction "2_2") (pintype "passive"))
      (node (ref "J2") (pin "H4") (pinfunction "H4_H4") (pintype "passive"))
      (node (ref "SV7") (pin "1") (pinfunction "1_1") (pintype "passive"))
    )
    (net (code "221") (name "/PLL_CLK-") (class "Default")
      (node (ref "C16") (pin "2") (pinfunction "2_2") (pintype "passive"))
      (node (ref "J2") (pin "H5") (pinfunction "H5_H5") (pintype "passive"))
      (node (ref "SV7") (pin "2") (pinfunction "2_2") (pintype "passive"))
    )
    (net (code "222") (name "/PO1") (class "Default")
      (node (ref "R48") (pin "1") (pinfunction "1_1") (pintype "passive"))
      (node (ref "U1") (pin "B1") (pinfunction "TR1_B1") (pintype "passive"))
      (node (ref "U10") (pin "12") (pinfunction "SW0A_12") (pintype "passive"))
      (node (ref "U10") (pin "42") (pinfunction "SW8A_42") (pintype "passive"))
      (node (ref "U3") (pin "12") (pinfunction "SW0A_12") (pintype "passive"))
      (node (ref "U3") (pin "42") (pinfunction "SW8A_42") (pintype "passive"))
      (node (ref "U4") (pin "12") (pinfunction "SW0A_12") (pintype "passive"))
      (node (ref "U4") (pin "42") (pinfunction "SW8A_42") (pintype "passive"))
      (node (ref "U5") (pin "12") (pinfunction "SW0A_12") (pintype "passive"))
      (node (ref "U5") (pin "42") (pinfunction "SW8A_42") (pintype "passive"))
      (node (ref "U6") (pin "12") (pinfunction "SW0A_12") (pintype "passive"))
      (node (ref "U6") (pin "42") (pinfunction "SW8A_42") (pintype "passive"))
      (node (ref "U7") (pin "12") (pinfunction "SW0A_12") (pintype "passive"))
      (node (ref "U7") (pin "42") (pinfunction "SW8A_42") (pintype "passive"))
      (node (ref "U8") (pin "12") (pinfunction "SW0A_12") (pintype "passive"))
      (node (ref "U8") (pin "42") (pinfunction "SW8A_42") (pintype "passive"))
      (node (ref "U9") (pin "12") (pinfunction "SW0A_12") (pintype "passive"))
      (node (ref "U9") (pin "42") (pinfunction "SW8A_42") (pintype "passive"))
    )
    (net (code "223") (name "/PO2") (class "Default")
      (node (ref "R44") (pin "1") (pinfunction "1_1") (pintype "passive"))
      (node (ref "U1") (pin "C1") (pinfunction "TR2_C1") (pintype "passive"))
      (node (ref "U10") (pin "10") (pinfunction "SW1A_10") (pintype "passive"))
      (node (ref "U10") (pin "40") (pinfunction "SW9A_40") (pintype "passive"))
      (node (ref "U3") (pin "10") (pinfunction "SW1A_10") (pintype "passive"))
      (node (ref "U3") (pin "40") (pinfunction "SW9A_40") (pintype "passive"))
      (node (ref "U4") (pin "10") (pinfunction "SW1A_10") (pintype "passive"))
      (node (ref "U4") (pin "40") (pinfunction "SW9A_40") (pintype "passive"))
      (node (ref "U5") (pin "10") (pinfunction "SW1A_10") (pintype "passive"))
      (node (ref "U5") (pin "40") (pinfunction "SW9A_40") (pintype "passive"))
      (node (ref "U6") (pin "10") (pinfunction "SW1A_10") (pintype "passive"))
      (node (ref "U6") (pin "40") (pinfunction "SW9A_40") (pintype "passive"))
      (node (ref "U7") (pin "10") (pinfunction "SW1A_10") (pintype "passive"))
      (node (ref "U7") (pin "40") (pinfunction "SW9A_40") (pintype "passive"))
      (node (ref "U8") (pin "10") (pinfunction "SW1A_10") (pintype "passive"))
      (node (ref "U8") (pin "40") (pinfunction "SW9A_40") (pintype "passive"))
      (node (ref "U9") (pin "10") (pinfunction "SW1A_10") (pintype "passive"))
      (node (ref "U9") (pin "40") (pinfunction "SW9A_40") (pintype "passive"))
    )
    (net (code "224") (name "/PO3") (class "Default")
      (node (ref "R45") (pin "1") (pinfunction "1_1") (pintype "passive"))
      (node (ref "U1") (pin "D1") (pinfunction "TR3_D1") (pintype "passive"))
      (node (ref "U10") (pin "38") (pinfunction "SW10A_38") (pintype "passive"))
      (node (ref "U10") (pin "8") (pinfunction "SW2A_8") (pintype "passive"))
      (node (ref "U3") (pin "38") (pinfunction "SW10A_38") (pintype "passive"))
      (node (ref "U3") (pin "8") (pinfunction "SW2A_8") (pintype "passive"))
      (node (ref "U4") (pin "38") (pinfunction "SW10A_38") (pintype "passive"))
      (node (ref "U4") (pin "8") (pinfunction "SW2A_8") (pintype "passive"))
      (node (ref "U5") (pin "38") (pinfunction "SW10A_38") (pintype "passive"))
      (node (ref "U5") (pin "8") (pinfunction "SW2A_8") (pintype "passive"))
      (node (ref "U6") (pin "38") (pinfunction "SW10A_38") (pintype "passive"))
      (node (ref "U6") (pin "8") (pinfunction "SW2A_8") (pintype "passive"))
      (node (ref "U7") (pin "38") (pinfunction "SW10A_38") (pintype "passive"))
      (node (ref "U7") (pin "8") (pinfunction "SW2A_8") (pintype "passive"))
      (node (ref "U8") (pin "38") (pinfunction "SW10A_38") (pintype "passive"))
      (node (ref "U8") (pin "8") (pinfunction "SW2A_8") (pintype "passive"))
      (node (ref "U9") (pin "38") (pinfunction "SW10A_38") (pintype "passive"))
      (node (ref "U9") (pin "8") (pinfunction "SW2A_8") (pintype "passive"))
    )
    (net (code "225") (name "/PO4") (class "Default")
      (node (ref "R49") (pin "1") (pinfunction "1_1") (pintype "passive"))
      (node (ref "U1") (pin "E1") (pinfunction "TR4_E1") (pintype "passive"))
      (node (ref "U10") (pin "34") (pinfunction "SW11A_34") (pintype "passive"))
      (node (ref "U10") (pin "6") (pinfunction "SW3A_6") (pintype "passive"))
      (node (ref "U3") (pin "34") (pinfunction "SW11A_34") (pintype "passive"))
      (node (ref "U3") (pin "6") (pinfunction "SW3A_6") (pintype "passive"))
      (node (ref "U4") (pin "34") (pinfunction "SW11A_34") (pintype "passive"))
      (node (ref "U4") (pin "6") (pinfunction "SW3A_6") (pintype "passive"))
      (node (ref "U5") (pin "34") (pinfunction "SW11A_34") (pintype "passive"))
      (node (ref "U5") (pin "6") (pinfunction "SW3A_6") (pintype "passive"))
      (node (ref "U6") (pin "34") (pinfunction "SW11A_34") (pintype "passive"))
      (node (ref "U6") (pin "6") (pinfunction "SW3A_6") (pintype "passive"))
      (node (ref "U7") (pin "34") (pinfunction "SW11A_34") (pintype "passive"))
      (node (ref "U7") (pin "6") (pinfunction "SW3A_6") (pintype "passive"))
      (node (ref "U8") (pin "34") (pinfunction "SW11A_34") (pintype "passive"))
      (node (ref "U8") (pin "6") (pinfunction "SW3A_6") (pintype "passive"))
      (node (ref "U9") (pin "34") (pinfunction "SW11A_34") (pintype "passive"))
      (node (ref "U9") (pin "6") (pinfunction "SW3A_6") (pintype "passive"))
    )
    (net (code "226") (name "/PO5") (class "Default")
      (node (ref "R50") (pin "1") (pinfunction "1_1") (pintype "passive"))
      (node (ref "U1") (pin "H1") (pinfunction "TR5_H1") (pintype "passive"))
      (node (ref "U10") (pin "32") (pinfunction "SW12A_32") (pintype "passive"))
      (node (ref "U10") (pin "4") (pinfunction "SW4A_4") (pintype "passive"))
      (node (ref "U3") (pin "32") (pinfunction "SW12A_32") (pintype "passive"))
      (node (ref "U3") (pin "4") (pinfunction "SW4A_4") (pintype "passive"))
      (node (ref "U4") (pin "32") (pinfunction "SW12A_32") (pintype "passive"))
      (node (ref "U4") (pin "4") (pinfunction "SW4A_4") (pintype "passive"))
      (node (ref "U5") (pin "32") (pinfunction "SW12A_32") (pintype "passive"))
      (node (ref "U5") (pin "4") (pinfunction "SW4A_4") (pintype "passive"))
      (node (ref "U6") (pin "32") (pinfunction "SW12A_32") (pintype "passive"))
      (node (ref "U6") (pin "4") (pinfunction "SW4A_4") (pintype "passive"))
      (node (ref "U7") (pin "32") (pinfunction "SW12A_32") (pintype "passive"))
      (node (ref "U7") (pin "4") (pinfunction "SW4A_4") (pintype "passive"))
      (node (ref "U8") (pin "32") (pinfunction "SW12A_32") (pintype "passive"))
      (node (ref "U8") (pin "4") (pinfunction "SW4A_4") (pintype "passive"))
      (node (ref "U9") (pin "32") (pinfunction "SW12A_32") (pintype "passive"))
      (node (ref "U9") (pin "4") (pinfunction "SW4A_4") (pintype "passive"))
    )
    (net (code "227") (name "/PO6") (class "Default")
      (node (ref "R51") (pin "1") (pinfunction "1_1") (pintype "passive"))
      (node (ref "U1") (pin "J1") (pinfunction "TR6_J1") (pintype "passive"))
      (node (ref "U10") (pin "30") (pinfunction "SW13A_30") (pintype "passive"))
      (node (ref "U10") (pin "48") (pinfunction "SW5A_48") (pintype "passive"))
      (node (ref "U3") (pin "30") (pinfunction "SW13A_30") (pintype "passive"))
      (node (ref "U3") (pin "48") (pinfunction "SW5A_48") (pintype "passive"))
      (node (ref "U4") (pin "30") (pinfunction "SW13A_30") (pintype "passive"))
      (node (ref "U4") (pin "48") (pinfunction "SW5A_48") (pintype "passive"))
      (node (ref "U5") (pin "30") (pinfunction "SW13A_30") (pintype "passive"))
      (node (ref "U5") (pin "48") (pinfunction "SW5A_48") (pintype "passive"))
      (node (ref "U6") (pin "30") (pinfunction "SW13A_30") (pintype "passive"))
      (node (ref "U6") (pin "48") (pinfunction "SW5A_48") (pintype "passive"))
      (node (ref "U7") (pin "30") (pinfunction "SW13A_30") (pintype "passive"))
      (node (ref "U7") (pin "48") (pinfunction "SW5A_48") (pintype "passive"))
      (node (ref "U8") (pin "30") (pinfunction "SW13A_30") (pintype "passive"))
      (node (ref "U8") (pin "48") (pinfunction "SW5A_48") (pintype "passive"))
      (node (ref "U9") (pin "30") (pinfunction "SW13A_30") (pintype "passive"))
      (node (ref "U9") (pin "48") (pinfunction "SW5A_48") (pintype "passive"))
    )
    (net (code "228") (name "/PO7") (class "Default")
      (node (ref "R52") (pin "1") (pinfunction "1_1") (pintype "passive"))
      (node (ref "U1") (pin "K1") (pinfunction "TR7_K1") (pintype "passive"))
      (node (ref "U10") (pin "28") (pinfunction "SW14A_28") (pintype "passive"))
      (node (ref "U10") (pin "46") (pinfunction "SW6A_46") (pintype "passive"))
      (node (ref "U3") (pin "28") (pinfunction "SW14A_28") (pintype "passive"))
      (node (ref "U3") (pin "46") (pinfunction "SW6A_46") (pintype "passive"))
      (node (ref "U4") (pin "28") (pinfunction "SW14A_28") (pintype "passive"))
      (node (ref "U4") (pin "46") (pinfunction "SW6A_46") (pintype "passive"))
      (node (ref "U5") (pin "28") (pinfunction "SW14A_28") (pintype "passive"))
      (node (ref "U5") (pin "46") (pinfunction "SW6A_46") (pintype "passive"))
      (node (ref "U6") (pin "28") (pinfunction "SW14A_28") (pintype "passive"))
      (node (ref "U6") (pin "46") (pinfunction "SW6A_46") (pintype "passive"))
      (node (ref "U7") (pin "28") (pinfunction "SW14A_28") (pintype "passive"))
      (node (ref "U7") (pin "46") (pinfunction "SW6A_46") (pintype "passive"))
      (node (ref "U8") (pin "28") (pinfunction "SW14A_28") (pintype "passive"))
      (node (ref "U8") (pin "46") (pinfunction "SW6A_46") (pintype "passive"))
      (node (ref "U9") (pin "28") (pinfunction "SW14A_28") (pintype "passive"))
      (node (ref "U9") (pin "46") (pinfunction "SW6A_46") (pintype "passive"))
    )
    (net (code "229") (name "/PO8") (class "Default")
      (node (ref "R53") (pin "1") (pinfunction "1_1") (pintype "passive"))
      (node (ref "U1") (pin "L1") (pinfunction "TR8_L1") (pintype "passive"))
      (node (ref "U10") (pin "26") (pinfunction "SW15A_26") (pintype "passive"))
      (node (ref "U10") (pin "44") (pinfunction "SW7A_44") (pintype "passive"))
      (node (ref "U3") (pin "26") (pinfunction "SW15A_26") (pintype "passive"))
      (node (ref "U3") (pin "44") (pinfunction "SW7A_44") (pintype "passive"))
      (node (ref "U4") (pin "26") (pinfunction "SW15A_26") (pintype "passive"))
      (node (ref "U4") (pin "44") (pinfunction "SW7A_44") (pintype "passive"))
      (node (ref "U5") (pin "26") (pinfunction "SW15A_26") (pintype "passive"))
      (node (ref "U5") (pin "44") (pinfunction "SW7A_44") (pintype "passive"))
      (node (ref "U6") (pin "26") (pinfunction "SW15A_26") (pintype "passive"))
      (node (ref "U6") (pin "44") (pinfunction "SW7A_44") (pintype "passive"))
      (node (ref "U7") (pin "26") (pinfunction "SW15A_26") (pintype "passive"))
      (node (ref "U7") (pin "44") (pinfunction "SW7A_44") (pintype "passive"))
      (node (ref "U8") (pin "26") (pinfunction "SW15A_26") (pintype "passive"))
      (node (ref "U8") (pin "44") (pinfunction "SW7A_44") (pintype "passive"))
      (node (ref "U9") (pin "26") (pinfunction "SW15A_26") (pintype "passive"))
      (node (ref "U9") (pin "44") (pinfunction "SW7A_44") (pintype "passive"))
    )
    (net (code "230") (name "/TCLK+") (class "Default")
      (node (ref "J2") (pin "D8") (pinfunction "D8_D8") (pintype "passive"))
      (node (ref "SV2") (pin "8") (pinfunction "8_8") (pintype "passive"))
      (node (ref "U1") (pin "M12") (pinfunction "TCLK+_M12") (pintype "passive"))
    )
    (net (code "231") (name "/TCLK-") (class "Default")
      (node (ref "J2") (pin "D9") (pinfunction "D9_D9") (pintype "passive"))
      (node (ref "SV2") (pin "9") (pinfunction "9_9") (pintype "passive"))
      (node (ref "U1") (pin "L12") (pinfunction "TCLK-_L12") (pintype "passive"))
    )
    (net (code "232") (name "/TINN1") (class "Default")
      (node (ref "PULSE_1") (pin "4") (pinfunction "4_4") (pintype "passive"))
      (node (ref "U1") (pin "B6") (pinfunction "TINN1_B6") (pintype "passive"))
    )
    (net (code "233") (name "/TINN2") (class "Default")
      (node (ref "PULSE_1") (pin "8") (pinfunction "8_8") (pintype "passive"))
      (node (ref "U1") (pin "B7") (pinfunction "TINN2_B7") (pintype "passive"))
    )
    (net (code "234") (name "/TINN3") (class "Default")
      (node (ref "PULSE_1") (pin "12") (pinfunction "12_12") (pintype "passive"))
      (node (ref "U1") (pin "B8") (pinfunction "TINN3_B8") (pintype "passive"))
    )
    (net (code "235") (name "/TINN4") (class "Default")
      (node (ref "PULSE_1") (pin "16") (pinfunction "16_16") (pintype "passive"))
      (node (ref "U1") (pin "B9") (pinfunction "TINN4_B9") (pintype "passive"))
    )
    (net (code "236") (name "/TINN5") (class "Default")
      (node (ref "PULSE_5") (pin "4") (pinfunction "4_4") (pintype "passive"))
      (node (ref "U1") (pin "L6") (pinfunction "TINN5_L6") (pintype "passive"))
    )
    (net (code "237") (name "/TINN6") (class "Default")
      (node (ref "PULSE_5") (pin "8") (pinfunction "8_8") (pintype "passive"))
      (node (ref "U1") (pin "L7") (pinfunction "TINN6_L7") (pintype "passive"))
    )
    (net (code "238") (name "/TINN7") (class "Default")
      (node (ref "PULSE_5") (pin "12") (pinfunction "12_12") (pintype "passive"))
      (node (ref "U1") (pin "L8") (pinfunction "TINN7_L8") (pintype "passive"))
    )
    (net (code "239") (name "/TINN8") (class "Default")
      (node (ref "PULSE_5") (pin "16") (pinfunction "16_16") (pintype "passive"))
      (node (ref "U1") (pin "L9") (pinfunction "TINN8_L9") (pintype "passive"))
    )
    (net (code "240") (name "/TINP1") (class "Default")
      (node (ref "PULSE_1") (pin "2") (pinfunction "2_2") (pintype "passive"))
      (node (ref "U1") (pin "A6") (pinfunction "TINP1_A6") (pintype "passive"))
    )
    (net (code "241") (name "/TINP2") (class "Default")
      (node (ref "PULSE_1") (pin "6") (pinfunction "6_6") (pintype "passive"))
      (node (ref "U1") (pin "A7") (pinfunction "TINP2_A7") (pintype "passive"))
    )
    (net (code "242") (name "/TINP3") (class "Default")
      (node (ref "PULSE_1") (pin "10") (pinfunction "10_10") (pintype "passive"))
      (node (ref "U1") (pin "A8") (pinfunction "TINP3_A8") (pintype "passive"))
    )
    (net (code "243") (name "/TINP4") (class "Default")
      (node (ref "PULSE_1") (pin "14") (pinfunction "14_14") (pintype "passive"))
      (node (ref "U1") (pin "A9") (pinfunction "TINP4_A9") (pintype "passive"))
    )
    (net (code "244") (name "/TINP5") (class "Default")
      (node (ref "PULSE_5") (pin "2") (pinfunction "2_2") (pintype "passive"))
      (node (ref "U1") (pin "M6") (pinfunction "TINP5_M6") (pintype "passive"))
    )
    (net (code "245") (name "/TINP6") (class "Default")
      (node (ref "PULSE_5") (pin "6") (pinfunction "6_6") (pintype "passive"))
      (node (ref "U1") (pin "M7") (pinfunction "TINP6_M7") (pintype "passive"))
    )
    (net (code "246") (name "/TINP7") (class "Default")
      (node (ref "PULSE_5") (pin "10") (pinfunction "10_10") (pintype "passive"))
      (node (ref "U1") (pin "M8") (pinfunction "TINP7_M8") (pintype "passive"))
    )
    (net (code "247") (name "/TINP8") (class "Default")
      (node (ref "PULSE_5") (pin "14") (pinfunction "14_14") (pintype "passive"))
      (node (ref "U1") (pin "M9") (pinfunction "TINP8_M9") (pintype "passive"))
    )
    (net (code "248") (name "/~LE1") (class "Default")
      (node (ref "SV10") (pin "1") (pinfunction "1_1") (pintype "passive"))
      (node (ref "U3") (pin "21") (pinfunction "~{LE}_21") (pintype "passive"))
    )
    (net (code "249") (name "/~LE2") (class "Default")
      (node (ref "SV10") (pin "3") (pinfunction "3_3") (pintype "passive"))
      (node (ref "U4") (pin "21") (pinfunction "~{LE}_21") (pintype "passive"))
    )
    (net (code "250") (name "/~LE3") (class "Default")
      (node (ref "SV10") (pin "5") (pinfunction "5_5") (pintype "passive"))
      (node (ref "U5") (pin "21") (pinfunction "~{LE}_21") (pintype "passive"))
    )
    (net (code "251") (name "/~LE4") (class "Default")
      (node (ref "SV10") (pin "7") (pinfunction "7_7") (pintype "passive"))
      (node (ref "U6") (pin "21") (pinfunction "~{LE}_21") (pintype "passive"))
    )
    (net (code "252") (name "/~LE5") (class "Default")
      (node (ref "SV10") (pin "9") (pinfunction "9_9") (pintype "passive"))
      (node (ref "U7") (pin "21") (pinfunction "~{LE}_21") (pintype "passive"))
    )
    (net (code "253") (name "/~LE6") (class "Default")
      (node (ref "SV10") (pin "11") (pinfunction "11_11") (pintype "passive"))
      (node (ref "U8") (pin "21") (pinfunction "~{LE}_21") (pintype "passive"))
    )
    (net (code "254") (name "/~LE7") (class "Default")
      (node (ref "SV10") (pin "13") (pinfunction "13_13") (pintype "passive"))
      (node (ref "U9") (pin "21") (pinfunction "~{LE}_21") (pintype "passive"))
    )
    (net (code "255") (name "/~LE8") (class "Default")
      (node (ref "SV10") (pin "15") (pinfunction "15_15") (pintype "passive"))
      (node (ref "U10") (pin "21") (pinfunction "~{LE}_21") (pintype "passive"))
    )
    (net (code "256") (name "AGND") (class "Default")
      (node (ref "C10") (pin "2") (pinfunction "2_2") (pintype "passive"))
      (node (ref "C11") (pin "2") (pinfunction "2_2") (pintype "passive"))
      (node (ref "C34") (pin "2") (pinfunction "2_2") (pintype "passive"))
      (node (ref "C35") (pin "2") (pinfunction "2_2") (pintype "passive"))
      (node (ref "C42") (pin "2") (pinfunction "2_2") (pintype "passive"))
      (node (ref "C43") (pin "2") (pinfunction "2_2") (pintype "passive"))
      (node (ref "C44") (pin "2") (pinfunction "2_2") (pintype "passive"))
      (node (ref "C9") (pin "2") (pinfunction "2_2") (pintype "passive"))
      (node (ref "N1") (pin "18") (pinfunction "AGND_18") (pintype "power_in"))
      (node (ref "R32") (pin "1") (pinfunction "1_1") (pintype "passive"))
      (node (ref "SV9") (pin "5") (pinfunction "5_5") (pintype "passive"))
      (node (ref "U17") (pin "1") (pinfunction "GND_1") (pintype "power_in"))
    )
    (net (code "257") (name "GND") (class "Default")
      (node (ref "C1") (pin "2") (pinfunction "2_2") (pintype "passive"))
      (node (ref "C100") (pin "1") (pinfunction "+_1") (pintype "passive"))
      (node (ref "C101") (pin "2") (pinfunction "2_2") (pintype "passive"))
      (node (ref "C12") (pin "2") (pinfunction "2_2") (pintype "passive"))
      (node (ref "C13") (pin "2") (pinfunction "2_2") (pintype "passive"))
      (node (ref "C14") (pin "2") (pinfunction "2_2") (pintype "passive"))
      (node (ref "C15") (pin "2") (pinfunction "2_2") (pintype "passive"))
      (node (ref "C17") (pin "2") (pinfunction "2_2") (pintype "passive"))
      (node (ref "C18") (pin "2") (pinfunction "2_2") (pintype "passive"))
      (node (ref "C2") (pin "2") (pinfunction "2_2") (pintype "passive"))
      (node (ref "C20") (pin "2") (pinfunction "2_2") (pintype "passive"))
      (node (ref "C23") (pin "2") (pinfunction "2_2") (pintype "passive"))
      (node (ref "C25") (pin "2") (pinfunction "2_2") (pintype "passive"))
      (node (ref "C26") (pin "2") (pinfunction "2_2") (pintype "passive"))
      (node (ref "C27") (pin "2") (pinfunction "2_2") (pintype "passive"))
      (node (ref "C28") (pin "2") (pinfunction "2_2") (pintype "passive"))
      (node (ref "C29") (pin "2") (pinfunction "2_2") (pintype "passive"))
      (node (ref "C3") (pin "2") (pinfunction "2_2") (pintype "passive"))
      (node (ref "C30") (pin "2") (pinfunction "2_2") (pintype "passive"))
      (node (ref "C31") (pin "2") (pinfunction "2_2") (pintype "passive"))
      (node (ref "C32") (pin "2") (pinfunction "2_2") (pintype "passive"))
      (node (ref "C33") (pin "2") (pinfunction "2_2") (pintype "passive"))
      (node (ref "C36") (pin "2") (pinfunction "2_2") (pintype "passive"))
      (node (ref "C37") (pin "2") (pinfunction "2_2") (pintype "passive"))
      (node (ref "C38") (pin "2") (pinfunction "2_2") (pintype "passive"))
      (node (ref "C39") (pin "2") (pinfunction "2_2") (pintype "passive"))
      (node (ref "C4") (pin "2") (pinfunction "2_2") (pintype "passive"))
      (node (ref "C40") (pin "2") (pinfunction "2_2") (pintype "passive"))
      (node (ref "C41") (pin "2") (pinfunction "2_2") (pintype "passive"))
      (node (ref "C45") (pin "2") (pinfunction "2_2") (pintype "passive"))
      (node (ref "C47") (pin "2") (pinfunction "2_2") (pintype "passive"))
      (node (ref "C48") (pin "2") (pinfunction "2_2") (pintype "passive"))
      (node (ref "C5") (pin "2") (pinfunction "2_2") (pintype "passive"))
      (node (ref "C50") (pin "2") (pinfunction "2_2") (pintype "passive"))
      (node (ref "C51") (pin "2") (pinfunction "2_2") (pintype "passive"))
      (node (ref "C52") (pin "2") (pinfunction "2_2") (pintype "passive"))
      (node (ref "C53") (pin "2") (pinfunction "2_2") (pintype "passive"))
      (node (ref "C54") (pin "2") (pinfunction "2_2") (pintype "passive"))
      (node (ref "C55") (pin "2") (pinfunction "2_2") (pintype "passive"))
      (node (ref "C56") (pin "2") (pinfunction "2_2") (pintype "passive"))
      (node (ref "C57") (pin "2") (pinfunction "2_2") (pintype "passive"))
      (node (ref "C58") (pin "2") (pinfunction "2_2") (pintype "passive"))
      (node (ref "C59") (pin "2") (pinfunction "2_2") (pintype "passive"))
      (node (ref "C6") (pin "2") (pinfunction "2_2") (pintype "passive"))
      (node (ref "C60") (pin "2") (pinfunction "2_2") (pintype "passive"))
      (node (ref "C61") (pin "2") (pinfunction "2_2") (pintype "passive"))
      (node (ref "C62") (pin "2") (pinfunction "2_2") (pintype "passive"))
      (node (ref "C63") (pin "2") (pinfunction "2_2") (pintype "passive"))
      (node (ref "C64") (pin "2") (pinfunction "2_2") (pintype "passive"))
      (node (ref "C65") (pin "2") (pinfunction "2_2") (pintype "passive"))
      (node (ref "C66") (pin "2") (pinfunction "2_2") (pintype "passive"))
      (node (ref "C67") (pin "2") (pinfunction "2_2") (pintype "passive"))
      (node (ref "C68") (pin "2") (pinfunction "2_2") (pintype "passive"))
      (node (ref "C69") (pin "2") (pinfunction "2_2") (pintype "passive"))
      (node (ref "C7") (pin "2") (pinfunction "2_2") (pintype "passive"))
      (node (ref "C70") (pin "2") (pinfunction "2_2") (pintype "passive"))
      (node (ref "C71") (pin "2") (pinfunction "2_2") (pintype "passive"))
      (node (ref "C72") (pin "2") (pinfunction "2_2") (pintype "passive"))
      (node (ref "C73") (pin "2") (pinfunction "2_2") (pintype "passive"))
      (node (ref "C74") (pin "2") (pinfunction "2_2") (pintype "passive"))
      (node (ref "C75") (pin "2") (pinfunction "2_2") (pintype "passive"))
      (node (ref "C76") (pin "2") (pinfunction "2_2") (pintype "passive"))
      (node (ref "C77") (pin "2") (pinfunction "2_2") (pintype "passive"))
      (node (ref "C78") (pin "2") (pinfunction "2_2") (pintype "passive"))
      (node (ref "C79") (pin "2") (pinfunction "2_2") (pintype "passive"))
      (node (ref "C8") (pin "2") (pinfunction "2_2") (pintype "passive"))
      (node (ref "C80") (pin "2") (pinfunction "2_2") (pintype "passive"))
      (node (ref "C81") (pin "2") (pinfunction "2_2") (pintype "passive"))
      (node (ref "C82") (pin "2") (pinfunction "2_2") (pintype "passive"))
      (node (ref "C83") (pin "2") (pinfunction "2_2") (pintype "passive"))
      (node (ref "C84") (pin "2") (pinfunction "2_2") (pintype "passive"))
      (node (ref "C85") (pin "2") (pinfunction "2_2") (pintype "passive"))
      (node (ref "C86") (pin "2") (pinfunction "2_2") (pintype "passive"))
      (node (ref "C87") (pin "2") (pinfunction "2_2") (pintype "passive"))
      (node (ref "C88") (pin "2") (pinfunction "2_2") (pintype "passive"))
      (node (ref "C89") (pin "2") (pinfunction "2_2") (pintype "passive"))
      (node (ref "C90") (pin "2") (pinfunction "2_2") (pintype "passive"))
      (node (ref "C91") (pin "2") (pinfunction "2_2") (pintype "passive"))
      (node (ref "C92") (pin "2") (pinfunction "2_2") (pintype "passive"))
      (node (ref "C93") (pin "2") (pinfunction "2_2") (pintype "passive"))
      (node (ref "C94") (pin "2") (pinfunction "2_2") (pintype "passive"))
      (node (ref "C95") (pin "2") (pinfunction "2_2") (pintype "passive"))
      (node (ref "C96") (pin "2") (pinfunction "2_2") (pintype "passive"))
      (node (ref "C97") (pin "2") (pinfunction "2_2") (pintype "passive"))
      (node (ref "C98") (pin "2") (pinfunction "2_2") (pintype "passive"))
      (node (ref "C99") (pin "2") (pinfunction "2_2") (pintype "passive"))
      (node (ref "J1") (pin "2") (pinfunction "2_2") (pintype "passive"))
      (node (ref "N1") (pin "20") (pinfunction "DGNDIO_20") (pintype "power_in"))
      (node (ref "N1") (pin "5") (pinfunction "DGND_5") (pintype "power_in"))
      (node (ref "R28") (pin "1") (pinfunction "1_1") (pintype "passive"))
      (node (ref "R30") (pin "1") (pinfunction "1_1") (pintype "passive"))
      (node (ref "R35") (pin "1") (pinfunction "1_1") (pintype "passive"))
      (node (ref "R47") (pin "1") (pinfunction "1_1") (pintype "passive"))
      (node (ref "SV1") (pin "9") (pinfunction "9_9") (pintype "passive"))
      (node (ref "SV4") (pin "10") (pinfunction "10_10") (pintype "passive"))
      (node (ref "SV9") (pin "4") (pinfunction "4_4") (pintype "passive"))
      (node (ref "U$1") (pin "A12") (pinfunction "A12_A12") (pintype "passive"))
      (node (ref "U$1") (pin "A16") (pinfunction "A16_A16") (pintype "passive"))
      (node (ref "U$1") (pin "A19") (pinfunction "A19_A19") (pintype "passive"))
      (node (ref "U$1") (pin "A20") (pinfunction "A20_A20") (pintype "passive"))
      (node (ref "U$1") (pin "A24") (pinfunction "A24_A24") (pintype "passive"))
      (node (ref "U$1") (pin "A28") (pinfunction "A28_A28") (pintype "passive"))
      (node (ref "U$1") (pin "A31") (pinfunction "A31_A31") (pintype "passive"))
      (node (ref "U$1") (pin "A32") (pinfunction "A32_A32") (pintype "passive"))
      (node (ref "U$1") (pin "A36") (pinfunction "A36_A36") (pintype "passive"))
      (node (ref "U$1") (pin "A40") (pinfunction "A40_A40") (pintype "passive"))
      (node (ref "U$1") (pin "A43") (pinfunction "A43_A43") (pintype "passive"))
      (node (ref "U$1") (pin "A44") (pinfunction "A44_A44") (pintype "passive"))
      (node (ref "U$1") (pin "A48") (pinfunction "A48_A48") (pintype "passive"))
      (node (ref "U$1") (pin "A52") (pinfunction "A52_A52") (pintype "passive"))
      (node (ref "U$1") (pin "A55") (pinfunction "A55_A55") (pintype "passive"))
      (node (ref "U$1") (pin "A7") (pinfunction "A7_A7") (pintype "passive"))
      (node (ref "U$1") (pin "A8") (pinfunction "A8_A8") (pintype "passive"))
      (node (ref "U$1") (pin "B10") (pinfunction "B10_B10") (pintype "passive"))
      (node (ref "U$1") (pin "B14") (pinfunction "B14_B14") (pintype "passive"))
      (node (ref "U$1") (pin "B18") (pinfunction "B18_B18") (pintype "passive"))
      (node (ref "U$1") (pin "B19") (pinfunction "B19_B19") (pintype "passive"))
      (node (ref "U$1") (pin "B22") (pinfunction "B22_B22") (pintype "passive"))
      (node (ref "U$1") (pin "B26") (pinfunction "B26_B26") (pintype "passive"))
      (node (ref "U$1") (pin "B30") (pinfunction "B30_B30") (pintype "passive"))
      (node (ref "U$1") (pin "B31") (pinfunction "B31_B31") (pintype "passive"))
      (node (ref "U$1") (pin "B34") (pinfunction "B34_B34") (pintype "passive"))
      (node (ref "U$1") (pin "B38") (pinfunction "B38_B38") (pintype "passive"))
      (node (ref "U$1") (pin "B42") (pinfunction "B42_B42") (pintype "passive"))
      (node (ref "U$1") (pin "B43") (pinfunction "B43_B43") (pintype "passive"))
      (node (ref "U$1") (pin "B46") (pinfunction "B46_B46") (pintype "passive"))
      (node (ref "U$1") (pin "B50") (pinfunction "B50_B50") (pintype "passive"))
      (node (ref "U$1") (pin "B54") (pinfunction "B54_B54") (pintype "passive"))
      (node (ref "U$1") (pin "B55") (pinfunction "B55_B55") (pintype "passive"))
      (node (ref "U$1") (pin "B7") (pinfunction "B7_B7") (pintype "passive"))
      (node (ref "U$1") (pin "C12") (pinfunction "C12_C12") (pintype "passive"))
      (node (ref "U$1") (pin "C16") (pinfunction "C16_C16") (pintype "passive"))
      (node (ref "U$1") (pin "C19") (pinfunction "C19_C19") (pintype "passive"))
      (node (ref "U$1") (pin "C20") (pinfunction "C20_C20") (pintype "passive"))
      (node (ref "U$1") (pin "C24") (pinfunction "C24_C24") (pintype "passive"))
      (node (ref "U$1") (pin "C28") (pinfunction "C28_C28") (pintype "passive"))
      (node (ref "U$1") (pin "C31") (pinfunction "C31_C31") (pintype "passive"))
      (node (ref "U$1") (pin "C32") (pinfunction "C32_C32") (pintype "passive"))
      (node (ref "U$1") (pin "C36") (pinfunction "C36_C36") (pintype "passive"))
      (node (ref "U$1") (pin "C40") (pinfunction "C40_C40") (pintype "passive"))
      (node (ref "U$1") (pin "C43") (pinfunction "C43_C43") (pintype "passive"))
      (node (ref "U$1") (pin "C44") (pinfunction "C44_C44") (pintype "passive"))
      (node (ref "U$1") (pin "C48") (pinfunction "C48_C48") (pintype "passive"))
      (node (ref "U$1") (pin "C52") (pinfunction "C52_C52") (pintype "passive"))
      (node (ref "U$1") (pin "C55") (pinfunction "C55_C55") (pintype "passive"))
      (node (ref "U$1") (pin "C7") (pinfunction "C7_C7") (pintype "passive"))
      (node (ref "U$1") (pin "C8") (pinfunction "C8_C8") (pintype "passive"))
      (node (ref "U$1") (pin "D10") (pinfunction "D10_D10") (pintype "passive"))
      (node (ref "U$1") (pin "D14") (pinfunction "D14_D14") (pintype "passive"))
      (node (ref "U$1") (pin "D18") (pinfunction "D18_D18") (pintype "passive"))
      (node (ref "U$1") (pin "D19") (pinfunction "D19_D19") (pintype "passive"))
      (node (ref "U$1") (pin "D22") (pinfunction "D22_D22") (pintype "passive"))
      (node (ref "U$1") (pin "D26") (pinfunction "D26_D26") (pintype "passive"))
      (node (ref "U$1") (pin "D30") (pinfunction "D30_D30") (pintype "passive"))
      (node (ref "U$1") (pin "D31") (pinfunction "D31_D31") (pintype "passive"))
      (node (ref "U$1") (pin "D34") (pinfunction "D34_D34") (pintype "passive"))
      (node (ref "U$1") (pin "D38") (pinfunction "D38_D38") (pintype "passive"))
      (node (ref "U$1") (pin "D42") (pinfunction "D42_D42") (pintype "passive"))
      (node (ref "U$1") (pin "D43") (pinfunction "D43_D43") (pintype "passive"))
      (node (ref "U$1") (pin "D46") (pinfunction "D46_D46") (pintype "passive"))
      (node (ref "U$1") (pin "D50") (pinfunction "D50_D50") (pintype "passive"))
      (node (ref "U$1") (pin "D54") (pinfunction "D54_D54") (pintype "passive"))
      (node (ref "U$1") (pin "D55") (pinfunction "D55_D55") (pintype "passive"))
      (node (ref "U$1") (pin "D7") (pinfunction "D7_D7") (pintype "passive"))
      (node (ref "U$2") (pin "12") (pinfunction "GND3_12") (pintype "passive"))
      (node (ref "U$2") (pin "4") (pinfunction "GND1_4") (pintype "passive"))
      (node (ref "U$2") (pin "7") (pinfunction "GND2_7") (pintype "passive"))
      (node (ref "U1") (pin "A1") (pinfunction "1_GND_A1") (pintype "passive"))
      (node (ref "U1") (pin "A13") (pinfunction "2_GND_A13") (pintype "passive"))
      (node (ref "U1") (pin "A14") (pinfunction "3_GND_A14") (pintype "passive"))
      (node (ref "U1") (pin "A15") (pinfunction "4_GND_A15") (pintype "passive"))
      (node (ref "U1") (pin "A16") (pinfunction "5_GND_A16") (pintype "passive"))
      (node (ref "U1") (pin "A17") (pinfunction "6_GND_A17") (pintype "passive"))
      (node (ref "U1") (pin "A18") (pinfunction "7_GND_A18") (pintype "passive"))
      (node (ref "U1") (pin "A27") (pinfunction "8_GND_A27") (pintype "passive"))
      (node (ref "U1") (pin "B10") (pinfunction "9_GND_B10") (pintype "passive"))
      (node (ref "U1") (pin "B13") (pinfunction "10_GND_B13") (pintype "passive"))
      (node (ref "U1") (pin "B14") (pinfunction "11_GND_B14") (pintype "passive"))
      (node (ref "U1") (pin "B15") (pinfunction "12_GND_B15") (pintype "passive"))
      (node (ref "U1") (pin "B17") (pinfunction "13_GND_B17") (pintype "passive"))
      (node (ref "U1") (pin "B18") (pinfunction "14_GND_B18") (pintype "passive"))
      (node (ref "U1") (pin "C10") (pinfunction "15_GND_C10") (pintype "passive"))
      (node (ref "U1") (pin "C11") (pinfunction "16_GND_C11") (pintype "passive"))
      (node (ref "U1") (pin "C12") (pinfunction "17_GND_C12") (pintype "passive"))
      (node (ref "U1") (pin "C13") (pinfunction "18_GND_C13") (pintype "passive"))
      (node (ref "U1") (pin "C14") (pinfunction "19_GND_C14") (pintype "passive"))
      (node (ref "U1") (pin "C15") (pinfunction "20_GND_C15") (pintype "passive"))
      (node (ref "U1") (pin "C17") (pinfunction "21_GND_C17") (pintype "passive"))
      (node (ref "U1") (pin "C18") (pinfunction "22_GND_C18") (pintype "passive"))
      (node (ref "U1") (pin "C19") (pinfunction "23_GND_C19") (pintype "passive"))
      (node (ref "U1") (pin "C20") (pinfunction "24_GND_C20") (pintype "passive"))
      (node (ref "U1") (pin "C21") (pinfunction "25_GND_C21") (pintype "passive"))
      (node (ref "U1") (pin "C22") (pinfunction "26_GND_C22") (pintype "passive"))
      (node (ref "U1") (pin "C23") (pinfunction "27_GND_C23") (pintype "passive"))
      (node (ref "U1") (pin "C24") (pinfunction "28_GND_C24") (pintype "passive"))
      (node (ref "U1") (pin "C25") (pinfunction "29_GND_C25") (pintype "passive"))
      (node (ref "U1") (pin "C26") (pinfunction "30_GND_C26") (pintype "passive"))
      (node (ref "U1") (pin "C4") (pinfunction "31_GND_C4") (pintype "passive"))
      (node (ref "U1") (pin "C5") (pinfunction "32_GND_C5") (pintype "passive"))
      (node (ref "U1") (pin "C6") (pinfunction "33_GND_C6") (pintype "passive"))
      (node (ref "U1") (pin "C7") (pinfunction "34_GND_C7") (pintype "passive"))
      (node (ref "U1") (pin "C8") (pinfunction "35_GND_C8") (pintype "passive"))
      (node (ref "U1") (pin "C9") (pinfunction "36_GND_C9") (pintype "passive"))
      (node (ref "U1") (pin "D10") (pinfunction "37_GND_D10") (pintype "passive"))
      (node (ref "U1") (pin "D11") (pinfunction "38_GND_D11") (pintype "passive"))
      (node (ref "U1") (pin "D12") (pinfunction "39_GND_D12") (pintype "passive"))
      (node (ref "U1") (pin "D13") (pinfunction "40_GND_D13") (pintype "passive"))
      (node (ref "U1") (pin "D14") (pinfunction "41_GND_D14") (pintype "passive"))
      (node (ref "U1") (pin "D15") (pinfunction "42_GND_D15") (pintype "passive"))
      (node (ref "U1") (pin "D17") (pinfunction "43_GND_D17") (pintype "passive"))
      (node (ref "U1") (pin "D18") (pinfunction "44_GND_D18") (pintype "passive"))
      (node (ref "U1") (pin "D19") (pinfunction "45_GND_D19") (pintype "passive"))
      (node (ref "U1") (pin "D20") (pinfunction "46_GND_D20") (pintype "passive"))
      (node (ref "U1") (pin "D21") (pinfunction "47_GND_D21") (pintype "passive"))
      (node (ref "U1") (pin "D22") (pinfunction "48_GND_D22") (pintype "passive"))
      (node (ref "U1") (pin "D23") (pinfunction "49_GND_D23") (pintype "passive"))
      (node (ref "U1") (pin "D24") (pinfunction "50_GND_D24") (pintype "passive"))
      (node (ref "U1") (pin "D25") (pinfunction "51_GND_D25") (pintype "passive"))
      (node (ref "U1") (pin "D26") (pinfunction "52_GND_D26") (pintype "passive"))
      (node (ref "U1") (pin "D4") (pinfunction "53_GND_D4") (pintype "passive"))
      (node (ref "U1") (pin "D5") (pinfunction "54_GND_D5") (pintype "passive"))
      (node (ref "U1") (pin "D6") (pinfunction "55_GND_D6") (pintype "passive"))
      (node (ref "U1") (pin "D7") (pinfunction "56_GND_D7") (pintype "passive"))
      (node (ref "U1") (pin "D8") (pinfunction "57_GND_D8") (pintype "passive"))
      (node (ref "U1") (pin "D9") (pinfunction "58_GND_D9") (pintype "passive"))
      (node (ref "U1") (pin "E10") (pinfunction "59_GND_E10") (pintype "passive"))
      (node (ref "U1") (pin "E11") (pinfunction "60_GND_E11") (pintype "passive"))
      (node (ref "U1") (pin "E12") (pinfunction "61_GND_E12") (pintype "passive"))
      (node (ref "U1") (pin "E13") (pinfunction "62_GND_E13") (pintype "passive"))
      (node (ref "U1") (pin "E14") (pinfunction "63_GND_E14") (pintype "passive"))
      (node (ref "U1") (pin "E15") (pinfunction "64_GND_E15") (pintype "passive"))
      (node (ref "U1") (pin "E17") (pinfunction "65_GND_E17") (pintype "passive"))
      (node (ref "U1") (pin "E18") (pinfunction "66_GND_E18") (pintype "passive"))
      (node (ref "U1") (pin "E19") (pinfunction "67_GND_E19") (pintype "passive"))
      (node (ref "U1") (pin "E20") (pinfunction "68_GND_E20") (pintype "passive"))
      (node (ref "U1") (pin "E21") (pinfunction "69_GND_E21") (pintype "passive"))
      (node (ref "U1") (pin "E22") (pinfunction "70_GND_E22") (pintype "passive"))
      (node (ref "U1") (pin "E23") (pinfunction "71_GND_E23") (pintype "passive"))
      (node (ref "U1") (pin "E24") (pinfunction "72_GND_E24") (pintype "passive"))
      (node (ref "U1") (pin "E25") (pinfunction "73_GND_E25") (pintype "passive"))
      (node (ref "U1") (pin "E26") (pinfunction "74_GND_E26") (pintype "passive"))
      (node (ref "U1") (pin "E4") (pinfunction "75_GND_E4") (pintype "passive"))
      (node (ref "U1") (pin "E5") (pinfunction "76_GND_E5") (pintype "passive"))
      (node (ref "U1") (pin "E6") (pinfunction "77_GND_E6") (pintype "passive"))
      (node (ref "U1") (pin "E7") (pinfunction "78_GND_E7") (pintype "passive"))
      (node (ref "U1") (pin "E8") (pinfunction "79_GND_E8") (pintype "passive"))
      (node (ref "U1") (pin "E9") (pinfunction "80_GND_E9") (pintype "passive"))
      (node (ref "U1") (pin "F1") (pinfunction "81_GND_F1") (pintype "passive"))
      (node (ref "U1") (pin "F10") (pinfunction "82_GND_F10") (pintype "passive"))
      (node (ref "U1") (pin "F11") (pinfunction "83_GND_F11") (pintype "passive"))
      (node (ref "U1") (pin "F12") (pinfunction "84_GND_F12") (pintype "passive"))
      (node (ref "U1") (pin "F13") (pinfunction "85_GND_F13") (pintype "passive"))
      (node (ref "U1") (pin "F14") (pinfunction "86_GND_F14") (pintype "passive"))
      (node (ref "U1") (pin "F15") (pinfunction "87_GND_F15") (pintype "passive"))
      (node (ref "U1") (pin "F16") (pinfunction "88_GND_F16") (pintype "passive"))
      (node (ref "U1") (pin "F17") (pinfunction "89_GND_F17") (pintype "passive"))
      (node (ref "U1") (pin "F19") (pinfunction "90_GND_F19") (pintype "passive"))
      (node (ref "U1") (pin "F2") (pinfunction "91_GND_F2") (pintype "passive"))
      (node (ref "U1") (pin "F20") (pinfunction "92_GND_F20") (pintype "passive"))
      (node (ref "U1") (pin "F21") (pinfunction "93_GND_F21") (pintype "passive"))
      (node (ref "U1") (pin "F22") (pinfunction "94_GND_F22") (pintype "passive"))
      (node (ref "U1") (pin "F23") (pinfunction "95_GND_F23") (pintype "passive"))
      (node (ref "U1") (pin "F24") (pinfunction "96_GND_F24") (pintype "passive"))
      (node (ref "U1") (pin "F25") (pinfunction "97_GND_F25") (pintype "passive"))
      (node (ref "U1") (pin "F3") (pinfunction "98_GND_F3") (pintype "passive"))
      (node (ref "U1") (pin "F4") (pinfunction "99_GND_F4") (pintype "passive"))
      (node (ref "U1") (pin "F5") (pinfunction "100_GND_F5") (pintype "passive"))
      (node (ref "U1") (pin "F6") (pinfunction "101_GND_F6") (pintype "passive"))
      (node (ref "U1") (pin "F7") (pinfunction "102_GND_F7") (pintype "passive"))
      (node (ref "U1") (pin "F8") (pinfunction "103_GND_F8") (pintype "passive"))
      (node (ref "U1") (pin "F9") (pinfunction "104_GND_F9") (pintype "passive"))
      (node (ref "U1") (pin "G1") (pinfunction "105_GND_G1") (pintype "passive"))
      (node (ref "U1") (pin "G10") (pinfunction "106_GND_G10") (pintype "passive"))
      (node (ref "U1") (pin "G11") (pinfunction "107_GND_G11") (pintype "passive"))
      (node (ref "U1") (pin "G12") (pinfunction "108_GND_G12") (pintype "passive"))
      (node (ref "U1") (pin "G13") (pinfunction "109_GND_G13") (pintype "passive"))
      (node (ref "U1") (pin "G14") (pinfunction "110_GND_G14") (pintype "passive"))
      (node (ref "U1") (pin "G15") (pinfunction "111_GND_G15") (pintype "passive"))
      (node (ref "U1") (pin "G16") (pinfunction "112_GND_G16") (pintype "passive"))
      (node (ref "U1") (pin "G17") (pinfunction "113_GND_G17") (pintype "passive"))
      (node (ref "U1") (pin "G19") (pinfunction "114_GND_G19") (pintype "passive"))
      (node (ref "U1") (pin "G2") (pinfunction "115_GND_G2") (pintype "passive"))
      (node (ref "U1") (pin "G20") (pinfunction "116_GND_G20") (pintype "passive"))
      (node (ref "U1") (pin "G21") (pinfunction "117_GND_G21") (pintype "passive"))
      (node (ref "U1") (pin "G22") (pinfunction "118_GND_G22") (pintype "passive"))
      (node (ref "U1") (pin "G23") (pinfunction "119_GND_G23") (pintype "passive"))
      (node (ref "U1") (pin "G24") (pinfunction "120_GND_G24") (pintype "passive"))
      (node (ref "U1") (pin "G25") (pinfunction "121_GND_G25") (pintype "passive"))
      (node (ref "U1") (pin "G3") (pinfunction "122_GND_G3") (pintype "passive"))
      (node (ref "U1") (pin "G4") (pinfunction "123_GND_G4") (pintype "passive"))
      (node (ref "U1") (pin "G5") (pinfunction "124_GND_G5") (pintype "passive"))
      (node (ref "U1") (pin "G6") (pinfunction "125_GND_G6") (pintype "passive"))
      (node (ref "U1") (pin "G7") (pinfunction "126_GND_G7") (pintype "passive"))
      (node (ref "U1") (pin "G8") (pinfunction "127_GND_G8") (pintype "passive"))
      (node (ref "U1") (pin "G9") (pinfunction "128_GND_G9") (pintype "passive"))
      (node (ref "U1") (pin "H10") (pinfunction "129_GND_H10") (pintype "passive"))
      (node (ref "U1") (pin "H11") (pinfunction "130_GND_H11") (pintype "passive"))
      (node (ref "U1") (pin "H12") (pinfunction "131_GND_H12") (pintype "passive"))
      (node (ref "U1") (pin "H13") (pinfunction "132_GND_H13") (pintype "passive"))
      (node (ref "U1") (pin "H14") (pinfunction "133_GND_H14") (pintype "passive"))
      (node (ref "U1") (pin "H15") (pinfunction "134_GND_H15") (pintype "passive"))
      (node (ref "U1") (pin "H17") (pinfunction "135_GND_H17") (pintype "passive"))
      (node (ref "U1") (pin "H18") (pinfunction "136_GND_H18") (pintype "passive"))
      (node (ref "U1") (pin "H19") (pinfunction "137_GND_H19") (pintype "passive"))
      (node (ref "U1") (pin "H20") (pinfunction "138_GND_H20") (pintype "passive"))
      (node (ref "U1") (pin "H21") (pinfunction "139_GND_H21") (pintype "passive"))
      (node (ref "U1") (pin "H22") (pinfunction "140_GND_H22") (pintype "passive"))
      (node (ref "U1") (pin "H23") (pinfunction "141_GND_H23") (pintype "passive"))
      (node (ref "U1") (pin "H24") (pinfunction "142_GND_H24") (pintype "passive"))
      (node (ref "U1") (pin "H25") (pinfunction "143_GND_H25") (pintype "passive"))
      (node (ref "U1") (pin "H26") (pinfunction "144_GND_H26") (pintype "passive"))
      (node (ref "U1") (pin "H4") (pinfunction "145_GND_H4") (pintype "passive"))
      (node (ref "U1") (pin "H5") (pinfunction "146_GND_H5") (pintype "passive"))
      (node (ref "U1") (pin "H6") (pinfunction "147_GND_H6") (pintype "passive"))
      (node (ref "U1") (pin "H7") (pinfunction "148_GND_H7") (pintype "passive"))
      (node (ref "U1") (pin "H8") (pinfunction "149_GND_H8") (pintype "passive"))
      (node (ref "U1") (pin "H9") (pinfunction "150_GND_H9") (pintype "passive"))
      (node (ref "U1") (pin "J10") (pinfunction "151_GND_J10") (pintype "passive"))
      (node (ref "U1") (pin "J11") (pinfunction "152_GND_J11") (pintype "passive"))
      (node (ref "U1") (pin "J12") (pinfunction "153_GND_J12") (pintype "passive"))
      (node (ref "U1") (pin "J13") (pinfunction "154_GND_J13") (pintype "passive"))
      (node (ref "U1") (pin "J14") (pinfunction "155_GND_J14") (pintype "passive"))
      (node (ref "U1") (pin "J15") (pinfunction "156_GND_J15") (pintype "passive"))
      (node (ref "U1") (pin "J17") (pinfunction "157_GND_J17") (pintype "passive"))
      (node (ref "U1") (pin "J18") (pinfunction "158_GND_J18") (pintype "passive"))
      (node (ref "U1") (pin "J19") (pinfunction "159_GND_J19") (pintype "passive"))
      (node (ref "U1") (pin "J20") (pinfunction "160_GND_J20") (pintype "passive"))
      (node (ref "U1") (pin "J21") (pinfunction "161_GND_J21") (pintype "passive"))
      (node (ref "U1") (pin "J22") (pinfunction "162_GND_J22") (pintype "passive"))
      (node (ref "U1") (pin "J23") (pinfunction "163_GND_J23") (pintype "passive"))
      (node (ref "U1") (pin "J24") (pinfunction "164_GND_J24") (pintype "passive"))
      (node (ref "U1") (pin "J25") (pinfunction "165_GND_J25") (pintype "passive"))
      (node (ref "U1") (pin "J26") (pinfunction "166_GND_J26") (pintype "passive"))
      (node (ref "U1") (pin "J4") (pinfunction "167_GND_J4") (pintype "passive"))
      (node (ref "U1") (pin "J5") (pinfunction "168_GND_J5") (pintype "passive"))
      (node (ref "U1") (pin "J6") (pinfunction "169_GND_J6") (pintype "passive"))
      (node (ref "U1") (pin "J7") (pinfunction "170_GND_J7") (pintype "passive"))
      (node (ref "U1") (pin "J8") (pinfunction "171_GND_J8") (pintype "passive"))
      (node (ref "U1") (pin "J9") (pinfunction "172_GND_J9") (pintype "passive"))
      (node (ref "U1") (pin "K10") (pinfunction "173_GND_K10") (pintype "passive"))
      (node (ref "U1") (pin "K11") (pinfunction "174_GND_K11") (pintype "passive"))
      (node (ref "U1") (pin "K12") (pinfunction "175_GND_K12") (pintype "passive"))
      (node (ref "U1") (pin "K13") (pinfunction "176_GND_K13") (pintype "passive"))
      (node (ref "U1") (pin "K14") (pinfunction "177_GND_K14") (pintype "passive"))
      (node (ref "U1") (pin "K15") (pinfunction "178_GND_K15") (pintype "passive"))
      (node (ref "U1") (pin "K17") (pinfunction "179_GND_K17") (pintype "passive"))
      (node (ref "U1") (pin "K18") (pinfunction "180_GND_K18") (pintype "passive"))
      (node (ref "U1") (pin "K19") (pinfunction "181_GND_K19") (pintype "passive"))
      (node (ref "U1") (pin "K20") (pinfunction "182_GND_K20") (pintype "passive"))
      (node (ref "U1") (pin "K21") (pinfunction "183_GND_K21") (pintype "passive"))
      (node (ref "U1") (pin "K22") (pinfunction "184_GND_K22") (pintype "passive"))
      (node (ref "U1") (pin "K23") (pinfunction "185_GND_K23") (pintype "passive"))
      (node (ref "U1") (pin "K24") (pinfunction "186_GND_K24") (pintype "passive"))
      (node (ref "U1") (pin "K25") (pinfunction "187_GND_K25") (pintype "passive"))
      (node (ref "U1") (pin "K26") (pinfunction "188_GND_K26") (pintype "passive"))
      (node (ref "U1") (pin "K4") (pinfunction "189_GND_K4") (pintype "passive"))
      (node (ref "U1") (pin "K5") (pinfunction "190_GND_K5") (pintype "passive"))
      (node (ref "U1") (pin "K6") (pinfunction "191_GND_K6") (pintype "passive"))
      (node (ref "U1") (pin "K7") (pinfunction "192_GND_K7") (pintype "passive"))
      (node (ref "U1") (pin "K8") (pinfunction "193_GND_K8") (pintype "passive"))
      (node (ref "U1") (pin "K9") (pinfunction "194_GND_K9") (pintype "passive"))
      (node (ref "U1") (pin "L10") (pinfunction "TEN_L10") (pintype "passive"))
      (node (ref "U1") (pin "L13") (pinfunction "195_GND_L13") (pintype "passive"))
      (node (ref "U1") (pin "L14") (pinfunction "196_GND_L14") (pintype "passive"))
      (node (ref "U1") (pin "L15") (pinfunction "197_GND_L15") (pintype "passive"))
      (node (ref "U1") (pin "L17") (pinfunction "198_GND_L17") (pintype "passive"))
      (node (ref "U1") (pin "L18") (pinfunction "199_GND_L18") (pintype "passive"))
      (node (ref "U1") (pin "L25") (pinfunction "200_GND_L25") (pintype "passive"))
      (node (ref "U1") (pin "M1") (pinfunction "201_GND_M1") (pintype "passive"))
      (node (ref "U1") (pin "M13") (pinfunction "202_GND_M13") (pintype "passive"))
      (node (ref "U1") (pin "M14") (pinfunction "203_GND_M14") (pintype "passive"))
      (node (ref "U1") (pin "M15") (pinfunction "204_GND_M15") (pintype "passive"))
      (node (ref "U1") (pin "M16") (pinfunction "205_GND_M16") (pintype "passive"))
      (node (ref "U1") (pin "M17") (pinfunction "206_GND_M17") (pintype "passive"))
      (node (ref "U1") (pin "M18") (pinfunction "207_GND_M18") (pintype "passive"))
      (node (ref "U1") (pin "M25") (pinfunction "208_GND_M25") (pintype "passive"))
      (node (ref "U10") (pin "17") (pinfunction "GND_17") (pintype "power_in"))
      (node (ref "U11") (pin "1") (pinfunction "GND_1") (pintype "power_in"))
      (node (ref "U12") (pin "1") (pinfunction "GND_1") (pintype "power_in"))
      (node (ref "U16") (pin "1") (pinfunction "GND_1") (pintype "power_in"))
      (node (ref "U19") (pin "3") (pinfunction "GND_3") (pintype "power_in"))
      (node (ref "U2") (pin "4") (pinfunction "GND_4") (pintype "power_in"))
      (node (ref "U20") (pin "2") (pinfunction "GND_2") (pintype "power_in"))
      (node (ref "U3") (pin "17") (pinfunction "GND_17") (pintype "power_in"))
      (node (ref "U4") (pin "17") (pinfunction "GND_17") (pintype "power_in"))
      (node (ref "U5") (pin "17") (pinfunction "GND_17") (pintype "power_in"))
      (node (ref "U6") (pin "17") (pinfunction "GND_17") (pintype "power_in"))
      (node (ref "U7") (pin "17") (pinfunction "GND_17") (pintype "power_in"))
      (node (ref "U8") (pin "17") (pinfunction "GND_17") (pintype "power_in"))
      (node (ref "U9") (pin "17") (pinfunction "GND_17") (pintype "power_in"))
      (node (ref "X1") (pin "2") (pinfunction "KL_2") (pintype "passive"))
      (node (ref "X2") (pin "1") (pinfunction "KL_1") (pintype "passive"))
      (node (ref "X3") (pin "1") (pinfunction "KL_1") (pintype "passive"))
      (node (ref "X4") (pin "1") (pinfunction "KL_1") (pintype "passive"))
    )
    (net (code "258") (name "Net-(C46-+)") (class "Default")
      (node (ref "C46") (pin "1") (pinfunction "+_1") (pintype "passive"))
      (node (ref "U19") (pin "2") (pinfunction "CAP+_2") (pintype "passive"))
    )
    (net (code "259") (name "Net-(C46--)") (class "Default")
      (node (ref "C46") (pin "2") (pinfunction "-_2") (pintype "passive"))
      (node (ref "U19") (pin "4") (pinfunction "CAP-_4") (pintype "passive"))
    )
    (net (code "260") (name "Net-(N1-N0)") (class "Default")
      (node (ref "N1") (pin "3") (pinfunction "N0_3") (pintype "output"))
      (node (ref "R15") (pin "2") (pinfunction "2_2") (pintype "passive"))
    )
    (net (code "261") (name "Net-(N1-N1)") (class "Default")
      (node (ref "N1") (pin "1") (pinfunction "N1_1") (pintype "output"))
      (node (ref "R1") (pin "2") (pinfunction "2_2") (pintype "passive"))
    )
    (net (code "262") (name "Net-(N1-N2)") (class "Default")
      (node (ref "N1") (pin "31") (pinfunction "N2_31") (pintype "output"))
      (node (ref "R4") (pin "1") (pinfunction "1_1") (pintype "passive"))
    )
    (net (code "263") (name "Net-(N1-N3)") (class "Default")
      (node (ref "N1") (pin "29") (pinfunction "N3_29") (pintype "output"))
      (node (ref "R6") (pin "1") (pinfunction "1_1") (pintype "passive"))
    )
    (net (code "264") (name "Net-(N1-N4)") (class "Default")
      (node (ref "N1") (pin "27") (pinfunction "N4_27") (pintype "output"))
      (node (ref "R8") (pin "1") (pinfunction "1_1") (pintype "passive"))
    )
    (net (code "265") (name "Net-(N1-N5)") (class "Default")
      (node (ref "N1") (pin "25") (pinfunction "N5_25") (pintype "output"))
      (node (ref "R10") (pin "1") (pinfunction "1_1") (pintype "passive"))
    )
    (net (code "266") (name "Net-(N1-N6)") (class "Default")
      (node (ref "N1") (pin "23") (pinfunction "N6_23") (pintype "output"))
      (node (ref "R12") (pin "1") (pinfunction "1_1") (pintype "passive"))
    )
    (net (code "267") (name "Net-(N1-N7)") (class "Default")
      (node (ref "N1") (pin "21") (pinfunction "N7_21") (pintype "output"))
      (node (ref "R14") (pin "1") (pinfunction "1_1") (pintype "passive"))
    )
    (net (code "268") (name "Net-(N1-P0)") (class "Default")
      (node (ref "N1") (pin "4") (pinfunction "P0_4") (pintype "output"))
      (node (ref "R16") (pin "2") (pinfunction "2_2") (pintype "passive"))
    )
    (net (code "269") (name "Net-(N1-P1)") (class "Default")
      (node (ref "N1") (pin "2") (pinfunction "P1_2") (pintype "output"))
      (node (ref "R2") (pin "2") (pinfunction "2_2") (pintype "passive"))
    )
    (net (code "270") (name "Net-(N1-P2)") (class "Default")
      (node (ref "N1") (pin "32") (pinfunction "P2_32") (pintype "output"))
      (node (ref "R3") (pin "1") (pinfunction "1_1") (pintype "passive"))
    )
    (net (code "271") (name "Net-(N1-P3)") (class "Default")
      (node (ref "N1") (pin "30") (pinfunction "P3_30") (pintype "output"))
      (node (ref "R5") (pin "1") (pinfunction "1_1") (pintype "passive"))
    )
    (net (code "272") (name "Net-(N1-P4)") (class "Default")
      (node (ref "N1") (pin "28") (pinfunction "P4_28") (pintype "output"))
      (node (ref "R7") (pin "1") (pinfunction "1_1") (pintype "passive"))
    )
    (net (code "273") (name "Net-(N1-P5)") (class "Default")
      (node (ref "N1") (pin "26") (pinfunction "P5_26") (pintype "output"))
      (node (ref "R9") (pin "1") (pinfunction "1_1") (pintype "passive"))
    )
    (net (code "274") (name "Net-(N1-P6)") (class "Default")
      (node (ref "N1") (pin "24") (pinfunction "P6_24") (pintype "output"))
      (node (ref "R11") (pin "1") (pinfunction "1_1") (pintype "passive"))
    )
    (net (code "275") (name "Net-(N1-P7)") (class "Default")
      (node (ref "N1") (pin "22") (pinfunction "P7_22") (pintype "output"))
      (node (ref "R13") (pin "1") (pinfunction "1_1") (pintype "passive"))
    )
    (net (code "276") (name "Net-(N1-PLL_CLK+)") (class "Default")
      (node (ref "C49") (pin "1") (pinfunction "1_1") (pintype "passive"))
      (node (ref "N1") (pin "13") (pinfunction "PLL_CLK+_13") (pintype "passive"))
    )
    (net (code "277") (name "Net-(N1-PLL_CLK-)") (class "Default")
      (node (ref "C16") (pin "1") (pinfunction "1_1") (pintype "passive"))
      (node (ref "N1") (pin "14") (pinfunction "PLL_CLK-_14") (pintype "passive"))
    )
    (net (code "278") (name "Net-(N1-PLL_LIN)") (class "Default")
      (node (ref "C44") (pin "1") (pinfunction "1_1") (pintype "passive"))
      (node (ref "N1") (pin "17") (pinfunction "PLL_LIN_17") (pintype "passive"))
      (node (ref "R33") (pin "2") (pinfunction "2_2") (pintype "passive"))
    )
    (net (code "279") (name "Net-(N1-PLL_VIN)") (class "Default")
      (node (ref "C43") (pin "1") (pinfunction "1_1") (pintype "passive"))
      (node (ref "N1") (pin "16") (pinfunction "PLL_VIN_16") (pintype "passive"))
      (node (ref "R31") (pin "1") (pinfunction "1_1") (pintype "passive"))
      (node (ref "R32") (pin "2") (pinfunction "2_2") (pintype "passive"))
    )
    (net (code "280") (name "Net-(N1-RST)") (class "Default")
      (node (ref "N1") (pin "8") (pinfunction "RST_8") (pintype "passive"))
      (node (ref "R18") (pin "2") (pinfunction "2_2") (pintype "passive"))
    )
    (net (code "281") (name "Net-(N1-SCLK)") (class "Default")
      (node (ref "N1") (pin "12") (pinfunction "SCLK_12") (pintype "passive"))
      (node (ref "R22") (pin "2") (pinfunction "2_2") (pintype "passive"))
    )
    (net (code "282") (name "Net-(N1-SLE)") (class "Default")
      (node (ref "N1") (pin "10") (pinfunction "SLE_10") (pintype "passive"))
      (node (ref "R20") (pin "2") (pinfunction "2_2") (pintype "passive"))
    )
    (net (code "283") (name "Net-(N1-SRD)") (class "Default")
      (node (ref "N1") (pin "9") (pinfunction "SRD_9") (pintype "output"))
      (node (ref "R19") (pin "2") (pinfunction "2_2") (pintype "passive"))
    )
    (net (code "284") (name "Net-(N1-SWR)") (class "Default")
      (node (ref "N1") (pin "11") (pinfunction "SWR_11") (pintype "passive"))
      (node (ref "R21") (pin "2") (pinfunction "2_2") (pintype "passive"))
    )
    (net (code "285") (name "Net-(N1-TX_EN)") (class "Default")
      (node (ref "N1") (pin "7") (pinfunction "TX_EN_7") (pintype "passive"))
      (node (ref "R17") (pin "2") (pinfunction "2_2") (pintype "passive"))
    )
    (net (code "286") (name "Net-(Q1-G)") (class "Default")
      (node (ref "Q1") (pin "1") (pinfunction "G_1") (pintype "passive"))
      (node (ref "U20") (pin "5") (pinfunction "GATE_5") (pintype "output"))
    )
    (net (code "287") (name "Net-(R17-Pad1)") (class "Default")
      (node (ref "R17") (pin "1") (pinfunction "1_1") (pintype "passive"))
      (node (ref "SV7") (pin "8") (pinfunction "8_8") (pintype "passive"))
    )
    (net (code "288") (name "Net-(R18-Pad1)") (class "Default")
      (node (ref "R18") (pin "1") (pinfunction "1_1") (pintype "passive"))
      (node (ref "SV7") (pin "7") (pinfunction "7_7") (pintype "passive"))
    )
    (net (code "289") (name "Net-(R19-Pad1)") (class "Default")
      (node (ref "R19") (pin "1") (pinfunction "1_1") (pintype "passive"))
      (node (ref "SV7") (pin "6") (pinfunction "6_6") (pintype "passive"))
    )
    (net (code "290") (name "Net-(R20-Pad1)") (class "Default")
      (node (ref "R20") (pin "1") (pinfunction "1_1") (pintype "passive"))
      (node (ref "SV7") (pin "5") (pinfunction "5_5") (pintype "passive"))
    )
    (net (code "291") (name "Net-(R21-Pad1)") (class "Default")
      (node (ref "R21") (pin "1") (pinfunction "1_1") (pintype "passive"))
      (node (ref "SV7") (pin "4") (pinfunction "4_4") (pintype "passive"))
    )
    (net (code "292") (name "Net-(R22-Pad1)") (class "Default")
      (node (ref "R22") (pin "1") (pinfunction "1_1") (pintype "passive"))
      (node (ref "SV7") (pin "3") (pinfunction "3_3") (pintype "passive"))
    )
    (net (code "293") (name "Net-(U1D-1_TVNNA)") (class "Default")
      (node (ref "C22") (pin "1") (pinfunction "1_1") (pintype "passive"))
      (node (ref "C23") (pin "1") (pinfunction "1_1") (pintype "passive"))
      (node (ref "C24") (pin "1") (pinfunction "1_1") (pintype "passive"))
      (node (ref "C25") (pin "1") (pinfunction "1_1") (pintype "passive"))
      (node (ref "U1") (pin "A2") (pinfunction "1_TVNNA_A2") (pintype "passive"))
      (node (ref "U1") (pin "B2") (pinfunction "2_TVNNA_B2") (pintype "passive"))
      (node (ref "U1") (pin "C2") (pinfunction "3_TVNNA_C2") (pintype "passive"))
      (node (ref "U1") (pin "D2") (pinfunction "4_TVNNA_D2") (pintype "passive"))
      (node (ref "U1") (pin "E2") (pinfunction "5_TVNNA_E2") (pintype "passive"))
      (node (ref "U1") (pin "H2") (pinfunction "1_TVNNB_H2") (pintype "passive"))
      (node (ref "U1") (pin "J2") (pinfunction "2_TVNNB_J2") (pintype "passive"))
      (node (ref "U1") (pin "K2") (pinfunction "3_TVNNB_K2") (pintype "passive"))
      (node (ref "U1") (pin "L2") (pinfunction "4_TVNNB_L2") (pintype "passive"))
      (node (ref "U1") (pin "M2") (pinfunction "5_TVNNB_M2") (pintype "passive"))
      (node (ref "X3") (pin "2") (pinfunction "KL_2") (pintype "passive"))
    )
    (net (code "294") (name "Net-(U1D-1_TVPPA)") (class "Default")
      (node (ref "C18") (pin "1") (pinfunction "1_1") (pintype "passive"))
      (node (ref "C19") (pin "1") (pinfunction "1_1") (pintype "passive"))
      (node (ref "C20") (pin "1") (pinfunction "1_1") (pintype "passive"))
      (node (ref "C21") (pin "1") (pinfunction "1_1") (pintype "passive"))
      (node (ref "U1") (pin "A3") (pinfunction "1_TVPPA_A3") (pintype "passive"))
      (node (ref "U1") (pin "B3") (pinfunction "2_TVPPA_B3") (pintype "passive"))
      (node (ref "U1") (pin "C3") (pinfunction "3_TVPPA_C3") (pintype "passive"))
      (node (ref "U1") (pin "D3") (pinfunction "4_TVPPA_D3") (pintype "passive"))
      (node (ref "U1") (pin "E3") (pinfunction "5_TVPPA_E3") (pintype "passive"))
      (node (ref "U1") (pin "H3") (pinfunction "1_TVPPB_H3") (pintype "passive"))
      (node (ref "U1") (pin "J3") (pinfunction "2_TVPPB_J3") (pintype "passive"))
      (node (ref "U1") (pin "K3") (pinfunction "3_TVPPB_K3") (pintype "passive"))
      (node (ref "U1") (pin "L3") (pinfunction "4_TVPPB_L3") (pintype "passive"))
      (node (ref "U1") (pin "M3") (pinfunction "5_TVPPB_M3") (pintype "passive"))
      (node (ref "X2") (pin "2") (pinfunction "KL_2") (pintype "passive"))
    )
    (net (code "295") (name "Net-(U1D-TVGNA)") (class "Default")
      (node (ref "C22") (pin "2") (pinfunction "2_2") (pintype "passive"))
      (node (ref "U1") (pin "B4") (pinfunction "TVGNA_B4") (pintype "passive"))
    )
    (net (code "296") (name "Net-(U1D-TVGNB)") (class "Default")
      (node (ref "C24") (pin "2") (pinfunction "2_2") (pintype "passive"))
      (node (ref "U1") (pin "L4") (pinfunction "TVGNB_L4") (pintype "passive"))
    )
    (net (code "297") (name "Net-(U1D-TVGPA)") (class "Default")
      (node (ref "C19") (pin "2") (pinfunction "2_2") (pintype "passive"))
      (node (ref "U1") (pin "A4") (pinfunction "TVGPA_A4") (pintype "passive"))
    )
    (net (code "298") (name "Net-(U1D-TVGPB)") (class "Default")
      (node (ref "C21") (pin "2") (pinfunction "2_2") (pintype "passive"))
      (node (ref "U1") (pin "M4") (pinfunction "TVGPB_M4") (pintype "passive"))
    )
    (net (code "299") (name "Net-(U1E-CWD)") (class "Default")
      (node (ref "SV8") (pin "5") (pinfunction "5_5") (pintype "passive"))
      (node (ref "U1") (pin "A26") (pinfunction "CWD_A26") (pintype "passive"))
    )
    (net (code "300") (name "Net-(U1E-GC+)") (class "Default")
      (node (ref "SV8") (pin "4") (pinfunction "4_4") (pintype "passive"))
      (node (ref "U1") (pin "M21") (pinfunction "GC+_M21") (pintype "passive"))
    )
    (net (code "301") (name "Net-(U1E-GC-)") (class "Default")
      (node (ref "SV8") (pin "3") (pinfunction "3_3") (pintype "passive"))
      (node (ref "U1") (pin "L21") (pinfunction "GC-_L21") (pintype "passive"))
    )
    (net (code "302") (name "Net-(U1E-REFIO)") (class "Default")
      (node (ref "C17") (pin "1") (pinfunction "1_1") (pintype "passive"))
      (node (ref "U1") (pin "A25") (pinfunction "REFIO_A25") (pintype "passive"))
    )
    (net (code "303") (name "Net-(U1E-SCLK)") (class "Default")
      (node (ref "SV5") (pin "2") (pinfunction "2_2") (pintype "passive"))
      (node (ref "U1") (pin "M26") (pinfunction "SCLK_M26") (pintype "passive"))
    )
    (net (code "304") (name "Net-(U1E-SDIO)") (class "Default")
      (node (ref "SV5") (pin "3") (pinfunction "3_3") (pintype "passive"))
      (node (ref "U1") (pin "L26") (pinfunction "SDIO_L26") (pintype "passive"))
    )
    (net (code "305") (name "Net-(U1E-SHDN)") (class "Default")
      (node (ref "SV8") (pin "6") (pinfunction "6_6") (pintype "passive"))
      (node (ref "U1") (pin "B26") (pinfunction "SHDN_B26") (pintype "passive"))
    )
    (net (code "306") (name "Net-(U1E-TCC0)") (class "Default")
      (node (ref "SV3") (pin "2") (pinfunction "2_2") (pintype "passive"))
      (node (ref "U1") (pin "B12") (pinfunction "TCC0_B12") (pintype "passive"))
    )
    (net (code "307") (name "Net-(U1E-TCC1)") (class "Default")
      (node (ref "SV3") (pin "1") (pinfunction "1_1") (pintype "passive"))
      (node (ref "U1") (pin "A12") (pinfunction "TCC1_A12") (pintype "passive"))
    )
    (net (code "308") (name "Net-(U1E-THP)") (class "Default")
      (node (ref "SV8") (pin "1") (pinfunction "1_1") (pintype "passive"))
      (node (ref "U1") (pin "L11") (pinfunction "THP_L11") (pintype "passive"))
    )
    (net (code "309") (name "Net-(U1E-TMODE0)") (class "Default")
      (node (ref "SV3") (pin "4") (pinfunction "4_4") (pintype "passive"))
      (node (ref "U1") (pin "B11") (pinfunction "TMODE0_B11") (pintype "passive"))
    )
    (net (code "310") (name "Net-(U1E-TMODE1)") (class "Default")
      (node (ref "SV3") (pin "3") (pinfunction "3_3") (pintype "passive"))
      (node (ref "U1") (pin "A11") (pinfunction "TMODE1_A11") (pintype "passive"))
    )
    (net (code "311") (name "Net-(U1E-TSYNC)") (class "Default")
      (node (ref "SV8") (pin "2") (pinfunction "2_2") (pintype "passive"))
      (node (ref "U1") (pin "M11") (pinfunction "TSYNC_M11") (pintype "passive"))
    )
    (net (code "312") (name "Net-(U1E-~{CS})") (class "Default")
      (node (ref "SV5") (pin "1") (pinfunction "1_1") (pintype "passive"))
      (node (ref "U1") (pin "M27") (pinfunction "~{CS}_M27") (pintype "passive"))
    )
    (net (code "313") (name "Net-(U13-ADJ)") (class "Default")
      (node (ref "R28") (pin "2") (pinfunction "2_2") (pintype "passive"))
      (node (ref "R29") (pin "1") (pinfunction "1_1") (pintype "passive"))
      (node (ref "U13") (pin "1") (pinfunction "ADJ_1") (pintype "passive"))
    )
    (net (code "314") (name "Net-(U14-ADJ)") (class "Default")
      (node (ref "R23") (pin "1") (pinfunction "1_1") (pintype "passive"))
      (node (ref "R30") (pin "2") (pinfunction "2_2") (pintype "passive"))
      (node (ref "U14") (pin "1") (pinfunction "ADJ_1") (pintype "passive"))
    )
    (net (code "315") (name "Net-(U15-ADJ)") (class "Default")
      (node (ref "R34") (pin "1") (pinfunction "1_1") (pintype "passive"))
      (node (ref "R35") (pin "2") (pinfunction "2_2") (pintype "passive"))
      (node (ref "U15") (pin "1") (pinfunction "ADJ_1") (pintype "passive"))
    )
    (net (code "316") (name "Net-(U20-SETV)") (class "Default")
      (node (ref "R46") (pin "1") (pinfunction "1_1") (pintype "passive"))
      (node (ref "R47") (pin "2") (pinfunction "2_2") (pintype "passive"))
      (node (ref "U20") (pin "3") (pinfunction "SETV_3") (pintype "passive"))
    )
    (net (code "317") (name "Net-(X1A-KL)") (class "Default")
      (node (ref "J1") (pin "1") (pinfunction "1_1") (pintype "passive"))
      (node (ref "L1") (pin "1") (pinfunction "1_1") (pintype "passive"))
      (node (ref "X1") (pin "1") (pinfunction "KL_1") (pintype "passive"))
    )
    (net (code "318") (name "VDDA") (class "Default")
      (node (ref "C42") (pin "1") (pinfunction "1_1") (pintype "passive"))
      (node (ref "FB1") (pin "2") (pinfunction "2_2") (pintype "passive"))
      (node (ref "N1") (pin "15") (pinfunction "VDDA_15") (pintype "power_in"))
      (node (ref "R33") (pin "1") (pinfunction "1_1") (pintype "passive"))
      (node (ref "SV9") (pin "2") (pinfunction "2_2") (pintype "passive"))
    )
    (net (code "319") (name "VDDC") (class "Default")
      (node (ref "C41") (pin "1") (pinfunction "1_1") (pintype "passive"))
      (node (ref "FB1") (pin "1") (pinfunction "1_1") (pintype "passive"))
      (node (ref "N1") (pin "6") (pinfunction "VDDC_6") (pintype "power_in"))
      (node (ref "Q1") (pin "3") (pinfunction "S_3") (pintype "passive"))
      (node (ref "SV9") (pin "3") (pinfunction "3_3") (pintype "passive"))
    )
    (net (code "320") (name "unconnected-(J1-Pad3)") (class "Default")
      (node (ref "J1") (pin "3") (pinfunction "3_3") (pintype "passive"))
    )
    (net (code "321") (name "unconnected-(J2-PadA1)") (class "Default")
      (node (ref "J2") (pin "A1") (pinfunction "A1_A1") (pintype "passive"))
    )
    (net (code "322") (name "unconnected-(J2-PadA2)") (class "Default")
      (node (ref "J2") (pin "A2") (pinfunction "A2_A2") (pintype "passive"))
    )
    (net (code "323") (name "unconnected-(J2-PadA3)") (class "Default")
      (node (ref "J2") (pin "A3") (pinfunction "A3_A3") (pintype "passive"))
    )
    (net (code "324") (name "unconnected-(J2-PadA4)") (class "Default")
      (node (ref "J2") (pin "A4") (pinfunction "A4_A4") (pintype "passive"))
    )
    (net (code "325") (name "unconnected-(J2-PadA5)") (class "Default")
      (node (ref "J2") (pin "A5") (pinfunction "A5_A5") (pintype "passive"))
    )
    (net (code "326") (name "unconnected-(J2-PadA6)") (class "Default")
      (node (ref "J2") (pin "A6") (pinfunction "A6_A6") (pintype "passive"))
    )
    (net (code "327") (name "unconnected-(J2-PadA7)") (class "Default")
      (node (ref "J2") (pin "A7") (pinfunction "A7_A7") (pintype "passive"))
    )
    (net (code "328") (name "unconnected-(J2-PadA8)") (class "Default")
      (node (ref "J2") (pin "A8") (pinfunction "A8_A8") (pintype "passive"))
    )
    (net (code "329") (name "unconnected-(J2-PadA9)") (class "Default")
      (node (ref "J2") (pin "A9") (pinfunction "A9_A9") (pintype "passive"))
    )
    (net (code "330") (name "unconnected-(J2-PadA10)") (class "Default")
      (node (ref "J2") (pin "A10") (pinfunction "A10_A10") (pintype "passive"))
    )
    (net (code "331") (name "unconnected-(J2-PadA11)") (class "Default")
      (node (ref "J2") (pin "A11") (pinfunction "A11_A11") (pintype "passive"))
    )
    (net (code "332") (name "unconnected-(J2-PadA12)") (class "Default")
      (node (ref "J2") (pin "A12") (pinfunction "A12_A12") (pintype "passive"))
    )
    (net (code "333") (name "unconnected-(J2-PadA13)") (class "Default")
      (node (ref "J2") (pin "A13") (pinfunction "A13_A13") (pintype "passive"))
    )
    (net (code "334") (name "unconnected-(J2-PadA14)") (class "Default")
      (node (ref "J2") (pin "A14") (pinfunction "A14_A14") (pintype "passive"))
    )
    (net (code "335") (name "unconnected-(J2-PadA15)") (class "Default")
      (node (ref "J2") (pin "A15") (pinfunction "A15_A15") (pintype "passive"))
    )
    (net (code "336") (name "unconnected-(J2-PadA16)") (class "Default")
      (node (ref "J2") (pin "A16") (pinfunction "A16_A16") (pintype "passive"))
    )
    (net (code "337") (name "unconnected-(J2-PadA17)") (class "Default")
      (node (ref "J2") (pin "A17") (pinfunction "A17_A17") (pintype "passive"))
    )
    (net (code "338") (name "unconnected-(J2-PadA18)") (class "Default")
      (node (ref "J2") (pin "A18") (pinfunction "A18_A18") (pintype "passive"))
    )
    (net (code "339") (name "unconnected-(J2-PadA19)") (class "Default")
      (node (ref "J2") (pin "A19") (pinfunction "A19_A19") (pintype "passive"))
    )
    (net (code "340") (name "unconnected-(J2-PadA20)") (class "Default")
      (node (ref "J2") (pin "A20") (pinfunction "A20_A20") (pintype "passive"))
    )
    (net (code "341") (name "unconnected-(J2-PadA21)") (class "Default")
      (node (ref "J2") (pin "A21") (pinfunction "A21_A21") (pintype "passive"))
    )
    (net (code "342") (name "unconnected-(J2-PadA22)") (class "Default")
      (node (ref "J2") (pin "A22") (pinfunction "A22_A22") (pintype "passive"))
    )
    (net (code "343") (name "unconnected-(J2-PadA23)") (class "Default")
      (node (ref "J2") (pin "A23") (pinfunction "A23_A23") (pintype "passive"))
    )
    (net (code "344") (name "unconnected-(J2-PadA24)") (class "Default")
      (node (ref "J2") (pin "A24") (pinfunction "A24_A24") (pintype "passive"))
    )
    (net (code "345") (name "unconnected-(J2-PadA25)") (class "Default")
      (node (ref "J2") (pin "A25") (pinfunction "A25_A25") (pintype "passive"))
    )
    (net (code "346") (name "unconnected-(J2-PadA26)") (class "Default")
      (node (ref "J2") (pin "A26") (pinfunction "A26_A26") (pintype "passive"))
    )
    (net (code "347") (name "unconnected-(J2-PadA27)") (class "Default")
      (node (ref "J2") (pin "A27") (pinfunction "A27_A27") (pintype "passive"))
    )
    (net (code "348") (name "unconnected-(J2-PadA28)") (class "Default")
      (node (ref "J2") (pin "A28") (pinfunction "A28_A28") (pintype "passive"))
    )
    (net (code "349") (name "unconnected-(J2-PadA29)") (class "Default")
      (node (ref "J2") (pin "A29") (pinfunction "A29_A29") (pintype "passive"))
    )
    (net (code "350") (name "unconnected-(J2-PadA30)") (class "Default")
      (node (ref "J2") (pin "A30") (pinfunction "A30_A30") (pintype "passive"))
    )
    (net (code "351") (name "unconnected-(J2-PadA31)") (class "Default")
      (node (ref "J2") (pin "A31") (pinfunction "A31_A31") (pintype "passive"))
    )
    (net (code "352") (name "unconnected-(J2-PadA32)") (class "Default")
      (node (ref "J2") (pin "A32") (pinfunction "A32_A32") (pintype "passive"))
    )
    (net (code "353") (name "unconnected-(J2-PadA33)") (class "Default")
      (node (ref "J2") (pin "A33") (pinfunction "A33_A33") (pintype "passive"))
    )
    (net (code "354") (name "unconnected-(J2-PadA34)") (class "Default")
      (node (ref "J2") (pin "A34") (pinfunction "A34_A34") (pintype "passive"))
    )
    (net (code "355") (name "unconnected-(J2-PadA35)") (class "Default")
      (node (ref "J2") (pin "A35") (pinfunction "A35_A35") (pintype "passive"))
    )
    (net (code "356") (name "unconnected-(J2-PadA36)") (class "Default")
      (node (ref "J2") (pin "A36") (pinfunction "A36_A36") (pintype "passive"))
    )
    (net (code "357") (name "unconnected-(J2-PadA37)") (class "Default")
      (node (ref "J2") (pin "A37") (pinfunction "A37_A37") (pintype "passive"))
    )
    (net (code "358") (name "unconnected-(J2-PadA38)") (class "Default")
      (node (ref "J2") (pin "A38") (pinfunction "A38_A38") (pintype "passive"))
    )
    (net (code "359") (name "unconnected-(J2-PadA39)") (class "Default")
      (node (ref "J2") (pin "A39") (pinfunction "A39_A39") (pintype "passive"))
    )
    (net (code "360") (name "unconnected-(J2-PadA40)") (class "Default")
      (node (ref "J2") (pin "A40") (pinfunction "A40_A40") (pintype "passive"))
    )
    (net (code "361") (name "unconnected-(J2-PadB1)") (class "Default")
      (node (ref "J2") (pin "B1") (pinfunction "B1_B1") (pintype "passive"))
    )
    (net (code "362") (name "unconnected-(J2-PadB2)") (class "Default")
      (node (ref "J2") (pin "B2") (pinfunction "B2_B2") (pintype "passive"))
    )
    (net (code "363") (name "unconnected-(J2-PadB3)") (class "Default")
      (node (ref "J2") (pin "B3") (pinfunction "B3_B3") (pintype "passive"))
    )
    (net (code "364") (name "unconnected-(J2-PadB4)") (class "Default")
      (node (ref "J2") (pin "B4") (pinfunction "B4_B4") (pintype "passive"))
    )
    (net (code "365") (name "unconnected-(J2-PadB5)") (class "Default")
      (node (ref "J2") (pin "B5") (pinfunction "B5_B5") (pintype "passive"))
    )
    (net (code "366") (name "unconnected-(J2-PadB6)") (class "Default")
      (node (ref "J2") (pin "B6") (pinfunction "B6_B6") (pintype "passive"))
    )
    (net (code "367") (name "unconnected-(J2-PadB7)") (class "Default")
      (node (ref "J2") (pin "B7") (pinfunction "B7_B7") (pintype "passive"))
    )
    (net (code "368") (name "unconnected-(J2-PadB8)") (class "Default")
      (node (ref "J2") (pin "B8") (pinfunction "B8_B8") (pintype "passive"))
    )
    (net (code "369") (name "unconnected-(J2-PadB9)") (class "Default")
      (node (ref "J2") (pin "B9") (pinfunction "B9_B9") (pintype "passive"))
    )
    (net (code "370") (name "unconnected-(J2-PadB10)") (class "Default")
      (node (ref "J2") (pin "B10") (pinfunction "B10_B10") (pintype "passive"))
    )
    (net (code "371") (name "unconnected-(J2-PadB11)") (class "Default")
      (node (ref "J2") (pin "B11") (pinfunction "B11_B11") (pintype "passive"))
    )
    (net (code "372") (name "unconnected-(J2-PadB12)") (class "Default")
      (node (ref "J2") (pin "B12") (pinfunction "B12_B12") (pintype "passive"))
    )
    (net (code "373") (name "unconnected-(J2-PadB13)") (class "Default")
      (node (ref "J2") (pin "B13") (pinfunction "B13_B13") (pintype "passive"))
    )
    (net (code "374") (name "unconnected-(J2-PadB14)") (class "Default")
      (node (ref "J2") (pin "B14") (pinfunction "B14_B14") (pintype "passive"))
    )
    (net (code "375") (name "unconnected-(J2-PadB15)") (class "Default")
      (node (ref "J2") (pin "B15") (pinfunction "B15_B15") (pintype "passive"))
    )
    (net (code "376") (name "unconnected-(J2-PadB16)") (class "Default")
      (node (ref "J2") (pin "B16") (pinfunction "B16_B16") (pintype "passive"))
    )
    (net (code "377") (name "unconnected-(J2-PadB17)") (class "Default")
      (node (ref "J2") (pin "B17") (pinfunction "B17_B17") (pintype "passive"))
    )
    (net (code "378") (name "unconnected-(J2-PadB18)") (class "Default")
      (node (ref "J2") (pin "B18") (pinfunction "B18_B18") (pintype "passive"))
    )
    (net (code "379") (name "unconnected-(J2-PadB19)") (class "Default")
      (node (ref "J2") (pin "B19") (pinfunction "B19_B19") (pintype "passive"))
    )
    (net (code "380") (name "unconnected-(J2-PadB20)") (class "Default")
      (node (ref "J2") (pin "B20") (pinfunction "B20_B20") (pintype "passive"))
    )
    (net (code "381") (name "unconnected-(J2-PadB21)") (class "Default")
      (node (ref "J2") (pin "B21") (pinfunction "B21_B21") (pintype "passive"))
    )
    (net (code "382") (name "unconnected-(J2-PadB22)") (class "Default")
      (node (ref "J2") (pin "B22") (pinfunction "B22_B22") (pintype "passive"))
    )
    (net (code "383") (name "unconnected-(J2-PadB23)") (class "Default")
      (node (ref "J2") (pin "B23") (pinfunction "B23_B23") (pintype "passive"))
    )
    (net (code "384") (name "unconnected-(J2-PadB24)") (class "Default")
      (node (ref "J2") (pin "B24") (pinfunction "B24_B24") (pintype "passive"))
    )
    (net (code "385") (name "unconnected-(J2-PadB25)") (class "Default")
      (node (ref "J2") (pin "B25") (pinfunction "B25_B25") (pintype "passive"))
    )
    (net (code "386") (name "unconnected-(J2-PadB26)") (class "Default")
      (node (ref "J2") (pin "B26") (pinfunction "B26_B26") (pintype "passive"))
    )
    (net (code "387") (name "unconnected-(J2-PadB27)") (class "Default")
      (node (ref "J2") (pin "B27") (pinfunction "B27_B27") (pintype "passive"))
    )
    (net (code "388") (name "unconnected-(J2-PadB28)") (class "Default")
      (node (ref "J2") (pin "B28") (pinfunction "B28_B28") (pintype "passive"))
    )
    (net (code "389") (name "unconnected-(J2-PadB29)") (class "Default")
      (node (ref "J2") (pin "B29") (pinfunction "B29_B29") (pintype "passive"))
    )
    (net (code "390") (name "unconnected-(J2-PadB30)") (class "Default")
      (node (ref "J2") (pin "B30") (pinfunction "B30_B30") (pintype "passive"))
    )
    (net (code "391") (name "unconnected-(J2-PadB31)") (class "Default")
      (node (ref "J2") (pin "B31") (pinfunction "B31_B31") (pintype "passive"))
    )
    (net (code "392") (name "unconnected-(J2-PadB32)") (class "Default")
      (node (ref "J2") (pin "B32") (pinfunction "B32_B32") (pintype "passive"))
    )
    (net (code "393") (name "unconnected-(J2-PadB33)") (class "Default")
      (node (ref "J2") (pin "B33") (pinfunction "B33_B33") (pintype "passive"))
    )
    (net (code "394") (name "unconnected-(J2-PadB34)") (class "Default")
      (node (ref "J2") (pin "B34") (pinfunction "B34_B34") (pintype "passive"))
    )
    (net (code "395") (name "unconnected-(J2-PadB35)") (class "Default")
      (node (ref "J2") (pin "B35") (pinfunction "B35_B35") (pintype "passive"))
    )
    (net (code "396") (name "unconnected-(J2-PadB36)") (class "Default")
      (node (ref "J2") (pin "B36") (pinfunction "B36_B36") (pintype "passive"))
    )
    (net (code "397") (name "unconnected-(J2-PadB37)") (class "Default")
      (node (ref "J2") (pin "B37") (pinfunction "B37_B37") (pintype "passive"))
    )
    (net (code "398") (name "unconnected-(J2-PadB38)") (class "Default")
      (node (ref "J2") (pin "B38") (pinfunction "B38_B38") (pintype "passive"))
    )
    (net (code "399") (name "unconnected-(J2-PadB39)") (class "Default")
      (node (ref "J2") (pin "B39") (pinfunction "B39_B39") (pintype "passive"))
    )
    (net (code "400") (name "unconnected-(J2-PadB40)") (class "Default")
      (node (ref "J2") (pin "B40") (pinfunction "B40_B40") (pintype "passive"))
    )
    (net (code "401") (name "unconnected-(J2-PadC1)") (class "Default")
      (node (ref "J2") (pin "C1") (pinfunction "C1_C1") (pintype "passive"))
    )
    (net (code "402") (name "unconnected-(J2-PadC2)") (class "Default")
      (node (ref "J2") (pin "C2") (pinfunction "C2_C2") (pintype "passive"))
    )
    (net (code "403") (name "unconnected-(J2-PadC3)") (class "Default")
      (node (ref "J2") (pin "C3") (pinfunction "C3_C3") (pintype "passive"))
    )
    (net (code "404") (name "unconnected-(J2-PadC4)") (class "Default")
      (node (ref "J2") (pin "C4") (pinfunction "C4_C4") (pintype "passive"))
    )
    (net (code "405") (name "unconnected-(J2-PadC5)") (class "Default")
      (node (ref "J2") (pin "C5") (pinfunction "C5_C5") (pintype "passive"))
    )
    (net (code "406") (name "unconnected-(J2-PadC6)") (class "Default")
      (node (ref "J2") (pin "C6") (pinfunction "C6_C6") (pintype "passive"))
    )
    (net (code "407") (name "unconnected-(J2-PadC7)") (class "Default")
      (node (ref "J2") (pin "C7") (pinfunction "C7_C7") (pintype "passive"))
    )
    (net (code "408") (name "unconnected-(J2-PadC8)") (class "Default")
      (node (ref "J2") (pin "C8") (pinfunction "C8_C8") (pintype "passive"))
    )
    (net (code "409") (name "unconnected-(J2-PadC9)") (class "Default")
      (node (ref "J2") (pin "C9") (pinfunction "C9_C9") (pintype "passive"))
    )
    (net (code "410") (name "unconnected-(J2-PadC10)") (class "Default")
      (node (ref "J2") (pin "C10") (pinfunction "C10_C10") (pintype "passive"))
    )
    (net (code "411") (name "unconnected-(J2-PadC11)") (class "Default")
      (node (ref "J2") (pin "C11") (pinfunction "C11_C11") (pintype "passive"))
    )
    (net (code "412") (name "unconnected-(J2-PadC12)") (class "Default")
      (node (ref "J2") (pin "C12") (pinfunction "C12_C12") (pintype "passive"))
    )
    (net (code "413") (name "unconnected-(J2-PadC13)") (class "Default")
      (node (ref "J2") (pin "C13") (pinfunction "C13_C13") (pintype "passive"))
    )
    (net (code "414") (name "unconnected-(J2-PadC14)") (class "Default")
      (node (ref "J2") (pin "C14") (pinfunction "C14_C14") (pintype "passive"))
    )
    (net (code "415") (name "unconnected-(J2-PadC15)") (class "Default")
      (node (ref "J2") (pin "C15") (pinfunction "C15_C15") (pintype "passive"))
    )
    (net (code "416") (name "unconnected-(J2-PadC16)") (class "Default")
      (node (ref "J2") (pin "C16") (pinfunction "C16_C16") (pintype "passive"))
    )
    (net (code "417") (name "unconnected-(J2-PadC17)") (class "Default")
      (node (ref "J2") (pin "C17") (pinfunction "C17_C17") (pintype "passive"))
    )
    (net (code "418") (name "unconnected-(J2-PadC18)") (class "Default")
      (node (ref "J2") (pin "C18") (pinfunction "C18_C18") (pintype "passive"))
    )
    (net (code "419") (name "unconnected-(J2-PadC19)") (class "Default")
      (node (ref "J2") (pin "C19") (pinfunction "C19_C19") (pintype "passive"))
    )
    (net (code "420") (name "unconnected-(J2-PadC20)") (class "Default")
      (node (ref "J2") (pin "C20") (pinfunction "C20_C20") (pintype "passive"))
    )
    (net (code "421") (name "unconnected-(J2-PadC21)") (class "Default")
      (node (ref "J2") (pin "C21") (pinfunction "C21_C21") (pintype "passive"))
    )
    (net (code "422") (name "unconnected-(J2-PadC22)") (class "Default")
      (node (ref "J2") (pin "C22") (pinfunction "C22_C22") (pintype "passive"))
    )
    (net (code "423") (name "unconnected-(J2-PadC23)") (class "Default")
      (node (ref "J2") (pin "C23") (pinfunction "C23_C23") (pintype "passive"))
    )
    (net (code "424") (name "unconnected-(J2-PadC24)") (class "Default")
      (node (ref "J2") (pin "C24") (pinfunction "C24_C24") (pintype "passive"))
    )
    (net (code "425") (name "unconnected-(J2-PadC25)") (class "Default")
      (node (ref "J2") (pin "C25") (pinfunction "C25_C25") (pintype "passive"))
    )
    (net (code "426") (name "unconnected-(J2-PadC26)") (class "Default")
      (node (ref "J2") (pin "C26") (pinfunction "C26_C26") (pintype "passive"))
    )
    (net (code "427") (name "unconnected-(J2-PadC27)") (class "Default")
      (node (ref "J2") (pin "C27") (pinfunction "C27_C27") (pintype "passive"))
    )
    (net (code "428") (name "unconnected-(J2-PadC28)") (class "Default")
      (node (ref "J2") (pin "C28") (pinfunction "C28_C28") (pintype "passive"))
    )
    (net (code "429") (name "unconnected-(J2-PadC29)") (class "Default")
      (node (ref "J2") (pin "C29") (pinfunction "C29_C29") (pintype "passive"))
    )
    (net (code "430") (name "unconnected-(J2-PadC30)") (class "Default")
      (node (ref "J2") (pin "C30") (pinfunction "C30_C30") (pintype "passive"))
    )
    (net (code "431") (name "unconnected-(J2-PadC31)") (class "Default")
      (node (ref "J2") (pin "C31") (pinfunction "C31_C31") (pintype "passive"))
    )
    (net (code "432") (name "unconnected-(J2-PadC32)") (class "Default")
      (node (ref "J2") (pin "C32") (pinfunction "C32_C32") (pintype "passive"))
    )
    (net (code "433") (name "unconnected-(J2-PadC33)") (class "Default")
      (node (ref "J2") (pin "C33") (pinfunction "C33_C33") (pintype "passive"))
    )
    (net (code "434") (name "unconnected-(J2-PadC34)") (class "Default")
      (node (ref "J2") (pin "C34") (pinfunction "C34_C34") (pintype "passive"))
    )
    (net (code "435") (name "unconnected-(J2-PadC35)") (class "Default")
      (node (ref "J2") (pin "C35") (pinfunction "C35_C35") (pintype "passive"))
    )
    (net (code "436") (name "unconnected-(J2-PadC36)") (class "Default")
      (node (ref "J2") (pin "C36") (pinfunction "C36_C36") (pintype "passive"))
    )
    (net (code "437") (name "unconnected-(J2-PadC37)") (class "Default")
      (node (ref "J2") (pin "C37") (pinfunction "C37_C37") (pintype "passive"))
    )
    (net (code "438") (name "unconnected-(J2-PadC38)") (class "Default")
      (node (ref "J2") (pin "C38") (pinfunction "C38_C38") (pintype "passive"))
    )
    (net (code "439") (name "unconnected-(J2-PadC39)") (class "Default")
      (node (ref "J2") (pin "C39") (pinfunction "C39_C39") (pintype "passive"))
    )
    (net (code "440") (name "unconnected-(J2-PadC40)") (class "Default")
      (node (ref "J2") (pin "C40") (pinfunction "C40_C40") (pintype "passive"))
    )
    (net (code "441") (name "unconnected-(J2-PadD1)") (class "Default")
      (node (ref "J2") (pin "D1") (pinfunction "D1_D1") (pintype "passive"))
    )
    (net (code "442") (name "unconnected-(J2-PadD2)") (class "Default")
      (node (ref "J2") (pin "D2") (pinfunction "D2_D2") (pintype "passive"))
    )
    (net (code "443") (name "unconnected-(J2-PadD3)") (class "Default")
      (node (ref "J2") (pin "D3") (pinfunction "D3_D3") (pintype "passive"))
    )
    (net (code "444") (name "unconnected-(J2-PadD4)") (class "Default")
      (node (ref "J2") (pin "D4") (pinfunction "D4_D4") (pintype "passive"))
    )
    (net (code "445") (name "unconnected-(J2-PadD5)") (class "Default")
      (node (ref "J2") (pin "D5") (pinfunction "D5_D5") (pintype "passive"))
    )
    (net (code "446") (name "unconnected-(J2-PadD6)") (class "Default")
      (node (ref "J2") (pin "D6") (pinfunction "D6_D6") (pintype "passive"))
    )
    (net (code "447") (name "unconnected-(J2-PadD7)") (class "Default")
      (node (ref "J2") (pin "D7") (pinfunction "D7_D7") (pintype "passive"))
    )
    (net (code "448") (name "unconnected-(J2-PadD10)") (class "Default")
      (node (ref "J2") (pin "D10") (pinfunction "D10_D10") (pintype "passive"))
    )
    (net (code "449") (name "unconnected-(J2-PadD11)") (class "Default")
      (node (ref "J2") (pin "D11") (pinfunction "D11_D11") (pintype "passive"))
    )
    (net (code "450") (name "unconnected-(J2-PadD12)") (class "Default")
      (node (ref "J2") (pin "D12") (pinfunction "D12_D12") (pintype "passive"))
    )
    (net (code "451") (name "unconnected-(J2-PadD13)") (class "Default")
      (node (ref "J2") (pin "D13") (pinfunction "D13_D13") (pintype "passive"))
    )
    (net (code "452") (name "unconnected-(J2-PadD14)") (class "Default")
      (node (ref "J2") (pin "D14") (pinfunction "D14_D14") (pintype "passive"))
    )
    (net (code "453") (name "unconnected-(J2-PadD15)") (class "Default")
      (node (ref "J2") (pin "D15") (pinfunction "D15_D15") (pintype "passive"))
    )
    (net (code "454") (name "unconnected-(J2-PadD16)") (class "Default")
      (node (ref "J2") (pin "D16") (pinfunction "D16_D16") (pintype "passive"))
    )
    (net (code "455") (name "unconnected-(J2-PadD17)") (class "Default")
      (node (ref "J2") (pin "D17") (pinfunction "D17_D17") (pintype "passive"))
    )
    (net (code "456") (name "unconnected-(J2-PadD18)") (class "Default")
      (node (ref "J2") (pin "D18") (pinfunction "D18_D18") (pintype "passive"))
    )
    (net (code "457") (name "unconnected-(J2-PadD19)") (class "Default")
      (node (ref "J2") (pin "D19") (pinfunction "D19_D19") (pintype "passive"))
    )
    (net (code "458") (name "unconnected-(J2-PadD20)") (class "Default")
      (node (ref "J2") (pin "D20") (pinfunction "D20_D20") (pintype "passive"))
    )
    (net (code "459") (name "unconnected-(J2-PadD21)") (class "Default")
      (node (ref "J2") (pin "D21") (pinfunction "D21_D21") (pintype "passive"))
    )
    (net (code "460") (name "unconnected-(J2-PadD22)") (class "Default")
      (node (ref "J2") (pin "D22") (pinfunction "D22_D22") (pintype "passive"))
    )
    (net (code "461") (name "unconnected-(J2-PadD23)") (class "Default")
      (node (ref "J2") (pin "D23") (pinfunction "D23_D23") (pintype "passive"))
    )
    (net (code "462") (name "unconnected-(J2-PadD24)") (class "Default")
      (node (ref "J2") (pin "D24") (pinfunction "D24_D24") (pintype "passive"))
    )
    (net (code "463") (name "unconnected-(J2-PadD25)") (class "Default")
      (node (ref "J2") (pin "D25") (pinfunction "D25_D25") (pintype "passive"))
    )
    (net (code "464") (name "unconnected-(J2-PadD26)") (class "Default")
      (node (ref "J2") (pin "D26") (pinfunction "D26_D26") (pintype "passive"))
    )
    (net (code "465") (name "unconnected-(J2-PadD27)") (class "Default")
      (node (ref "J2") (pin "D27") (pinfunction "D27_D27") (pintype "passive"))
    )
    (net (code "466") (name "unconnected-(J2-PadD28)") (class "Default")
      (node (ref "J2") (pin "D28") (pinfunction "D28_D28") (pintype "passive"))
    )
    (net (code "467") (name "unconnected-(J2-PadD29)") (class "Default")
      (node (ref "J2") (pin "D29") (pinfunction "D29_D29") (pintype "passive"))
    )
    (net (code "468") (name "unconnected-(J2-PadD30)") (class "Default")
      (node (ref "J2") (pin "D30") (pinfunction "D30_D30") (pintype "passive"))
    )
    (net (code "469") (name "unconnected-(J2-PadD31)") (class "Default")
      (node (ref "J2") (pin "D31") (pinfunction "D31_D31") (pintype "passive"))
    )
    (net (code "470") (name "unconnected-(J2-PadD32)") (class "Default")
      (node (ref "J2") (pin "D32") (pinfunction "D32_D32") (pintype "passive"))
    )
    (net (code "471") (name "unconnected-(J2-PadD33)") (class "Default")
      (node (ref "J2") (pin "D33") (pinfunction "D33_D33") (pintype "passive"))
    )
    (net (code "472") (name "unconnected-(J2-PadD34)") (class "Default")
      (node (ref "J2") (pin "D34") (pinfunction "D34_D34") (pintype "passive"))
    )
    (net (code "473") (name "unconnected-(J2-PadD35)") (class "Default")
      (node (ref "J2") (pin "D35") (pinfunction "D35_D35") (pintype "passive"))
    )
    (net (code "474") (name "unconnected-(J2-PadD36)") (class "Default")
      (node (ref "J2") (pin "D36") (pinfunction "D36_D36") (pintype "passive"))
    )
    (net (code "475") (name "unconnected-(J2-PadD37)") (class "Default")
      (node (ref "J2") (pin "D37") (pinfunction "D37_D37") (pintype "passive"))
    )
    (net (code "476") (name "unconnected-(J2-PadD38)") (class "Default")
      (node (ref "J2") (pin "D38") (pinfunction "D38_D38") (pintype "passive"))
    )
    (net (code "477") (name "unconnected-(J2-PadD39)") (class "Default")
      (node (ref "J2") (pin "D39") (pinfunction "D39_D39") (pintype "passive"))
    )
    (net (code "478") (name "unconnected-(J2-PadD40)") (class "Default")
      (node (ref "J2") (pin "D40") (pinfunction "D40_D40") (pintype "passive"))
    )
    (net (code "479") (name "unconnected-(J2-PadE1)") (class "Default")
      (node (ref "J2") (pin "E1") (pinfunction "E1_E1") (pintype "passive"))
    )
    (net (code "480") (name "unconnected-(J2-PadE2)") (class "Default")
      (node (ref "J2") (pin "E2") (pinfunction "E2_E2") (pintype "passive"))
    )
    (net (code "481") (name "unconnected-(J2-PadE3)") (class "Default")
      (node (ref "J2") (pin "E3") (pinfunction "E3_E3") (pintype "passive"))
    )
    (net (code "482") (name "unconnected-(J2-PadE4)") (class "Default")
      (node (ref "J2") (pin "E4") (pinfunction "E4_E4") (pintype "passive"))
    )
    (net (code "483") (name "unconnected-(J2-PadE5)") (class "Default")
      (node (ref "J2") (pin "E5") (pinfunction "E5_E5") (pintype "passive"))
    )
    (net (code "484") (name "unconnected-(J2-PadE6)") (class "Default")
      (node (ref "J2") (pin "E6") (pinfunction "E6_E6") (pintype "passive"))
    )
    (net (code "485") (name "unconnected-(J2-PadE7)") (class "Default")
      (node (ref "J2") (pin "E7") (pinfunction "E7_E7") (pintype "passive"))
    )
    (net (code "486") (name "unconnected-(J2-PadE8)") (class "Default")
      (node (ref "J2") (pin "E8") (pinfunction "E8_E8") (pintype "passive"))
    )
    (net (code "487") (name "unconnected-(J2-PadE9)") (class "Default")
      (node (ref "J2") (pin "E9") (pinfunction "E9_E9") (pintype "passive"))
    )
    (net (code "488") (name "unconnected-(J2-PadE10)") (class "Default")
      (node (ref "J2") (pin "E10") (pinfunction "E10_E10") (pintype "passive"))
    )
    (net (code "489") (name "unconnected-(J2-PadE11)") (class "Default")
      (node (ref "J2") (pin "E11") (pinfunction "E11_E11") (pintype "passive"))
    )
    (net (code "490") (name "unconnected-(J2-PadE12)") (class "Default")
      (node (ref "J2") (pin "E12") (pinfunction "E12_E12") (pintype "passive"))
    )
    (net (code "491") (name "unconnected-(J2-PadE13)") (class "Default")
      (node (ref "J2") (pin "E13") (pinfunction "E13_E13") (pintype "passive"))
    )
    (net (code "492") (name "unconnected-(J2-PadE14)") (class "Default")
      (node (ref "J2") (pin "E14") (pinfunction "E14_E14") (pintype "passive"))
    )
    (net (code "493") (name "unconnected-(J2-PadE15)") (class "Default")
      (node (ref "J2") (pin "E15") (pinfunction "E15_E15") (pintype "passive"))
    )
    (net (code "494") (name "unconnected-(J2-PadE16)") (class "Default")
      (node (ref "J2") (pin "E16") (pinfunction "E16_E16") (pintype "passive"))
    )
    (net (code "495") (name "unconnected-(J2-PadE17)") (class "Default")
      (node (ref "J2") (pin "E17") (pinfunction "E17_E17") (pintype "passive"))
    )
    (net (code "496") (name "unconnected-(J2-PadE18)") (class "Default")
      (node (ref "J2") (pin "E18") (pinfunction "E18_E18") (pintype "passive"))
    )
    (net (code "497") (name "unconnected-(J2-PadE19)") (class "Default")
      (node (ref "J2") (pin "E19") (pinfunction "E19_E19") (pintype "passive"))
    )
    (net (code "498") (name "unconnected-(J2-PadE20)") (class "Default")
      (node (ref "J2") (pin "E20") (pinfunction "E20_E20") (pintype "passive"))
    )
    (net (code "499") (name "unconnected-(J2-PadE21)") (class "Default")
      (node (ref "J2") (pin "E21") (pinfunction "E21_E21") (pintype "passive"))
    )
    (net (code "500") (name "unconnected-(J2-PadE22)") (class "Default")
      (node (ref "J2") (pin "E22") (pinfunction "E22_E22") (pintype "passive"))
    )
    (net (code "501") (name "unconnected-(J2-PadE23)") (class "Default")
      (node (ref "J2") (pin "E23") (pinfunction "E23_E23") (pintype "passive"))
    )
    (net (code "502") (name "unconnected-(J2-PadE24)") (class "Default")
      (node (ref "J2") (pin "E24") (pinfunction "E24_E24") (pintype "passive"))
    )
    (net (code "503") (name "unconnected-(J2-PadE25)") (class "Default")
      (node (ref "J2") (pin "E25") (pinfunction "E25_E25") (pintype "passive"))
    )
    (net (code "504") (name "unconnected-(J2-PadE26)") (class "Default")
      (node (ref "J2") (pin "E26") (pinfunction "E26_E26") (pintype "passive"))
    )
    (net (code "505") (name "unconnected-(J2-PadE27)") (class "Default")
      (node (ref "J2") (pin "E27") (pinfunction "E27_E27") (pintype "passive"))
    )
    (net (code "506") (name "unconnected-(J2-PadE28)") (class "Default")
      (node (ref "J2") (pin "E28") (pinfunction "E28_E28") (pintype "passive"))
    )
    (net (code "507") (name "unconnected-(J2-PadE29)") (class "Default")
      (node (ref "J2") (pin "E29") (pinfunction "E29_E29") (pintype "passive"))
    )
    (net (code "508") (name "unconnected-(J2-PadE30)") (class "Default")
      (node (ref "J2") (pin "E30") (pinfunction "E30_E30") (pintype "passive"))
    )
    (net (code "509") (name "unconnected-(J2-PadE31)") (class "Default")
      (node (ref "J2") (pin "E31") (pinfunction "E31_E31") (pintype "passive"))
    )
    (net (code "510") (name "unconnected-(J2-PadE32)") (class "Default")
      (node (ref "J2") (pin "E32") (pinfunction "E32_E32") (pintype "passive"))
    )
    (net (code "511") (name "unconnected-(J2-PadE33)") (class "Default")
      (node (ref "J2") (pin "E33") (pinfunction "E33_E33") (pintype "passive"))
    )
    (net (code "512") (name "unconnected-(J2-PadE34)") (class "Default")
      (node (ref "J2") (pin "E34") (pinfunction "E34_E34") (pintype "passive"))
    )
    (net (code "513") (name "unconnected-(J2-PadE35)") (class "Default")
      (node (ref "J2") (pin "E35") (pinfunction "E35_E35") (pintype "passive"))
    )
    (net (code "514") (name "unconnected-(J2-PadE36)") (class "Default")
      (node (ref "J2") (pin "E36") (pinfunction "E36_E36") (pintype "passive"))
    )
    (net (code "515") (name "unconnected-(J2-PadE37)") (class "Default")
      (node (ref "J2") (pin "E37") (pinfunction "E37_E37") (pintype "passive"))
    )
    (net (code "516") (name "unconnected-(J2-PadE38)") (class "Default")
      (node (ref "J2") (pin "E38") (pinfunction "E38_E38") (pintype "passive"))
    )
    (net (code "517") (name "unconnected-(J2-PadE39)") (class "Default")
      (node (ref "J2") (pin "E39") (pinfunction "E39_E39") (pintype "passive"))
    )
    (net (code "518") (name "unconnected-(J2-PadE40)") (class "Default")
      (node (ref "J2") (pin "E40") (pinfunction "E40_E40") (pintype "passive"))
    )
    (net (code "519") (name "unconnected-(J2-PadF1)") (class "Default")
      (node (ref "J2") (pin "F1") (pinfunction "F1_F1") (pintype "passive"))
    )
    (net (code "520") (name "unconnected-(J2-PadF2)") (class "Default")
      (node (ref "J2") (pin "F2") (pinfunction "F2_F2") (pintype "passive"))
    )
    (net (code "521") (name "unconnected-(J2-PadF3)") (class "Default")
      (node (ref "J2") (pin "F3") (pinfunction "F3_F3") (pintype "passive"))
    )
    (net (code "522") (name "unconnected-(J2-PadF4)") (class "Default")
      (node (ref "J2") (pin "F4") (pinfunction "F4_F4") (pintype "passive"))
    )
    (net (code "523") (name "unconnected-(J2-PadF5)") (class "Default")
      (node (ref "J2") (pin "F5") (pinfunction "F5_F5") (pintype "passive"))
    )
    (net (code "524") (name "unconnected-(J2-PadF6)") (class "Default")
      (node (ref "J2") (pin "F6") (pinfunction "F6_F6") (pintype "passive"))
    )
    (net (code "525") (name "unconnected-(J2-PadF7)") (class "Default")
      (node (ref "J2") (pin "F7") (pinfunction "F7_F7") (pintype "passive"))
    )
    (net (code "526") (name "unconnected-(J2-PadF8)") (class "Default")
      (node (ref "J2") (pin "F8") (pinfunction "F8_F8") (pintype "passive"))
    )
    (net (code "527") (name "unconnected-(J2-PadF9)") (class "Default")
      (node (ref "J2") (pin "F9") (pinfunction "F9_F9") (pintype "passive"))
    )
    (net (code "528") (name "unconnected-(J2-PadF10)") (class "Default")
      (node (ref "J2") (pin "F10") (pinfunction "F10_F10") (pintype "passive"))
    )
    (net (code "529") (name "unconnected-(J2-PadF11)") (class "Default")
      (node (ref "J2") (pin "F11") (pinfunction "F11_F11") (pintype "passive"))
    )
    (net (code "530") (name "unconnected-(J2-PadF12)") (class "Default")
      (node (ref "J2") (pin "F12") (pinfunction "F12_F12") (pintype "passive"))
    )
    (net (code "531") (name "unconnected-(J2-PadF13)") (class "Default")
      (node (ref "J2") (pin "F13") (pinfunction "F13_F13") (pintype "passive"))
    )
    (net (code "532") (name "unconnected-(J2-PadF14)") (class "Default")
      (node (ref "J2") (pin "F14") (pinfunction "F14_F14") (pintype "passive"))
    )
    (net (code "533") (name "unconnected-(J2-PadF15)") (class "Default")
      (node (ref "J2") (pin "F15") (pinfunction "F15_F15") (pintype "passive"))
    )
    (net (code "534") (name "unconnected-(J2-PadF16)") (class "Default")
      (node (ref "J2") (pin "F16") (pinfunction "F16_F16") (pintype "passive"))
    )
    (net (code "535") (name "unconnected-(J2-PadF17)") (class "Default")
      (node (ref "J2") (pin "F17") (pinfunction "F17_F17") (pintype "passive"))
    )
    (net (code "536") (name "unconnected-(J2-PadF18)") (class "Default")
      (node (ref "J2") (pin "F18") (pinfunction "F18_F18") (pintype "passive"))
    )
    (net (code "537") (name "unconnected-(J2-PadF19)") (class "Default")
      (node (ref "J2") (pin "F19") (pinfunction "F19_F19") (pintype "passive"))
    )
    (net (code "538") (name "unconnected-(J2-PadF20)") (class "Default")
      (node (ref "J2") (pin "F20") (pinfunction "F20_F20") (pintype "passive"))
    )
    (net (code "539") (name "unconnected-(J2-PadF21)") (class "Default")
      (node (ref "J2") (pin "F21") (pinfunction "F21_F21") (pintype "passive"))
    )
    (net (code "540") (name "unconnected-(J2-PadF22)") (class "Default")
      (node (ref "J2") (pin "F22") (pinfunction "F22_F22") (pintype "passive"))
    )
    (net (code "541") (name "unconnected-(J2-PadF23)") (class "Default")
      (node (ref "J2") (pin "F23") (pinfunction "F23_F23") (pintype "passive"))
    )
    (net (code "542") (name "unconnected-(J2-PadF24)") (class "Default")
      (node (ref "J2") (pin "F24") (pinfunction "F24_F24") (pintype "passive"))
    )
    (net (code "543") (name "unconnected-(J2-PadF25)") (class "Default")
      (node (ref "J2") (pin "F25") (pinfunction "F25_F25") (pintype "passive"))
    )
    (net (code "544") (name "unconnected-(J2-PadF26)") (class "Default")
      (node (ref "J2") (pin "F26") (pinfunction "F26_F26") (pintype "passive"))
    )
    (net (code "545") (name "unconnected-(J2-PadF27)") (class "Default")
      (node (ref "J2") (pin "F27") (pinfunction "F27_F27") (pintype "passive"))
    )
    (net (code "546") (name "unconnected-(J2-PadF28)") (class "Default")
      (node (ref "J2") (pin "F28") (pinfunction "F28_F28") (pintype "passive"))
    )
    (net (code "547") (name "unconnected-(J2-PadF29)") (class "Default")
      (node (ref "J2") (pin "F29") (pinfunction "F29_F29") (pintype "passive"))
    )
    (net (code "548") (name "unconnected-(J2-PadF30)") (class "Default")
      (node (ref "J2") (pin "F30") (pinfunction "F30_F30") (pintype "passive"))
    )
    (net (code "549") (name "unconnected-(J2-PadF31)") (class "Default")
      (node (ref "J2") (pin "F31") (pinfunction "F31_F31") (pintype "passive"))
    )
    (net (code "550") (name "unconnected-(J2-PadF32)") (class "Default")
      (node (ref "J2") (pin "F32") (pinfunction "F32_F32") (pintype "passive"))
    )
    (net (code "551") (name "unconnected-(J2-PadF33)") (class "Default")
      (node (ref "J2") (pin "F33") (pinfunction "F33_F33") (pintype "passive"))
    )
    (net (code "552") (name "unconnected-(J2-PadF34)") (class "Default")
      (node (ref "J2") (pin "F34") (pinfunction "F34_F34") (pintype "passive"))
    )
    (net (code "553") (name "unconnected-(J2-PadF35)") (class "Default")
      (node (ref "J2") (pin "F35") (pinfunction "F35_F35") (pintype "passive"))
    )
    (net (code "554") (name "unconnected-(J2-PadF36)") (class "Default")
      (node (ref "J2") (pin "F36") (pinfunction "F36_F36") (pintype "passive"))
    )
    (net (code "555") (name "unconnected-(J2-PadF37)") (class "Default")
      (node (ref "J2") (pin "F37") (pinfunction "F37_F37") (pintype "passive"))
    )
    (net (code "556") (name "unconnected-(J2-PadF38)") (class "Default")
      (node (ref "J2") (pin "F38") (pinfunction "F38_F38") (pintype "passive"))
    )
    (net (code "557") (name "unconnected-(J2-PadF39)") (class "Default")
      (node (ref "J2") (pin "F39") (pinfunction "F39_F39") (pintype "passive"))
    )
    (net (code "558") (name "unconnected-(J2-PadF40)") (class "Default")
      (node (ref "J2") (pin "F40") (pinfunction "F40_F40") (pintype "passive"))
    )
    (net (code "559") (name "unconnected-(J2-PadG1)") (class "Default")
      (node (ref "J2") (pin "G1") (pinfunction "G1_G1") (pintype "passive"))
    )
    (net (code "560") (name "unconnected-(J2-PadG4)") (class "Default")
      (node (ref "J2") (pin "G4") (pinfunction "G4_G4") (pintype "passive"))
    )
    (net (code "561") (name "unconnected-(J2-PadG5)") (class "Default")
      (node (ref "J2") (pin "G5") (pinfunction "G5_G5") (pintype "passive"))
    )
    (net (code "562") (name "unconnected-(J2-PadG8)") (class "Default")
      (node (ref "J2") (pin "G8") (pinfunction "G8_G8") (pintype "passive"))
    )
    (net (code "563") (name "unconnected-(J2-PadG11)") (class "Default")
      (node (ref "J2") (pin "G11") (pinfunction "G11_G11") (pintype "passive"))
    )
    (net (code "564") (name "unconnected-(J2-PadG14)") (class "Default")
      (node (ref "J2") (pin "G14") (pinfunction "G14_G14") (pintype "passive"))
    )
    (net (code "565") (name "unconnected-(J2-PadG17)") (class "Default")
      (node (ref "J2") (pin "G17") (pinfunction "G17_G17") (pintype "passive"))
    )
    (net (code "566") (name "unconnected-(J2-PadG20)") (class "Default")
      (node (ref "J2") (pin "G20") (pinfunction "G20_G20") (pintype "passive"))
    )
    (net (code "567") (name "unconnected-(J2-PadG21)") (class "Default")
      (node (ref "J2") (pin "G21") (pinfunction "G21_G21") (pintype "passive"))
    )
    (net (code "568") (name "unconnected-(J2-PadG22)") (class "Default")
      (node (ref "J2") (pin "G22") (pinfunction "G22_G22") (pintype "passive"))
    )
    (net (code "569") (name "unconnected-(J2-PadG23)") (class "Default")
      (node (ref "J2") (pin "G23") (pinfunction "G23_G23") (pintype "passive"))
    )
    (net (code "570") (name "unconnected-(J2-PadG24)") (class "Default")
      (node (ref "J2") (pin "G24") (pinfunction "G24_G24") (pintype "passive"))
    )
    (net (code "571") (name "unconnected-(J2-PadG25)") (class "Default")
      (node (ref "J2") (pin "G25") (pinfunction "G25_G25") (pintype "passive"))
    )
    (net (code "572") (name "unconnected-(J2-PadG26)") (class "Default")
      (node (ref "J2") (pin "G26") (pinfunction "G26_G26") (pintype "passive"))
    )
    (net (code "573") (name "unconnected-(J2-PadG27)") (class "Default")
      (node (ref "J2") (pin "G27") (pinfunction "G27_G27") (pintype "passive"))
    )
    (net (code "574") (name "unconnected-(J2-PadG28)") (class "Default")
      (node (ref "J2") (pin "G28") (pinfunction "G28_G28") (pintype "passive"))
    )
    (net (code "575") (name "unconnected-(J2-PadG29)") (class "Default")
      (node (ref "J2") (pin "G29") (pinfunction "G29_G29") (pintype "passive"))
    )
    (net (code "576") (name "unconnected-(J2-PadG30)") (class "Default")
      (node (ref "J2") (pin "G30") (pinfunction "G30_G30") (pintype "passive"))
    )
    (net (code "577") (name "unconnected-(J2-PadG31)") (class "Default")
      (node (ref "J2") (pin "G31") (pinfunction "G31_G31") (pintype "passive"))
    )
    (net (code "578") (name "unconnected-(J2-PadG32)") (class "Default")
      (node (ref "J2") (pin "G32") (pinfunction "G32_G32") (pintype "passive"))
    )
    (net (code "579") (name "unconnected-(J2-PadG33)") (class "Default")
      (node (ref "J2") (pin "G33") (pinfunction "G33_G33") (pintype "passive"))
    )
    (net (code "580") (name "unconnected-(J2-PadG34)") (class "Default")
      (node (ref "J2") (pin "G34") (pinfunction "G34_G34") (pintype "passive"))
    )
    (net (code "581") (name "unconnected-(J2-PadG35)") (class "Default")
      (node (ref "J2") (pin "G35") (pinfunction "G35_G35") (pintype "passive"))
    )
    (net (code "582") (name "unconnected-(J2-PadG36)") (class "Default")
      (node (ref "J2") (pin "G36") (pinfunction "G36_G36") (pintype "passive"))
    )
    (net (code "583") (name "unconnected-(J2-PadG37)") (class "Default")
      (node (ref "J2") (pin "G37") (pinfunction "G37_G37") (pintype "passive"))
    )
    (net (code "584") (name "unconnected-(J2-PadG38)") (class "Default")
      (node (ref "J2") (pin "G38") (pinfunction "G38_G38") (pintype "passive"))
    )
    (net (code "585") (name "unconnected-(J2-PadG39)") (class "Default")
      (node (ref "J2") (pin "G39") (pinfunction "G39_G39") (pintype "passive"))
    )
    (net (code "586") (name "unconnected-(J2-PadG40)") (class "Default")
      (node (ref "J2") (pin "G40") (pinfunction "G40_G40") (pintype "passive"))
    )
    (net (code "587") (name "unconnected-(J2-PadH1)") (class "Default")
      (node (ref "J2") (pin "H1") (pinfunction "H1_H1") (pintype "passive"))
    )
    (net (code "588") (name "unconnected-(J2-PadH2)") (class "Default")
      (node (ref "J2") (pin "H2") (pinfunction "H2_H2") (pintype "passive"))
    )
    (net (code "589") (name "unconnected-(J2-PadH3)") (class "Default")
      (node (ref "J2") (pin "H3") (pinfunction "H3_H3") (pintype "passive"))
    )
    (net (code "590") (name "unconnected-(J2-PadH6)") (class "Default")
      (node (ref "J2") (pin "H6") (pinfunction "H6_H6") (pintype "passive"))
    )
    (net (code "591") (name "unconnected-(J2-PadH9)") (class "Default")
      (node (ref "J2") (pin "H9") (pinfunction "H9_H9") (pintype "passive"))
    )
    (net (code "592") (name "unconnected-(J2-PadH12)") (class "Default")
      (node (ref "J2") (pin "H12") (pinfunction "H12_H12") (pintype "passive"))
    )
    (net (code "593") (name "unconnected-(J2-PadH15)") (class "Default")
      (node (ref "J2") (pin "H15") (pinfunction "H15_H15") (pintype "passive"))
    )
    (net (code "594") (name "unconnected-(J2-PadH18)") (class "Default")
      (node (ref "J2") (pin "H18") (pinfunction "H18_H18") (pintype "passive"))
    )
    (net (code "595") (name "unconnected-(J2-PadH19)") (class "Default")
      (node (ref "J2") (pin "H19") (pinfunction "H19_H19") (pintype "passive"))
    )
    (net (code "596") (name "unconnected-(J2-PadH20)") (class "Default")
      (node (ref "J2") (pin "H20") (pinfunction "H20_H20") (pintype "passive"))
    )
    (net (code "597") (name "unconnected-(J2-PadH21)") (class "Default")
      (node (ref "J2") (pin "H21") (pinfunction "H21_H21") (pintype "passive"))
    )
    (net (code "598") (name "unconnected-(J2-PadH22)") (class "Default")
      (node (ref "J2") (pin "H22") (pinfunction "H22_H22") (pintype "passive"))
    )
    (net (code "599") (name "unconnected-(J2-PadH23)") (class "Default")
      (node (ref "J2") (pin "H23") (pinfunction "H23_H23") (pintype "passive"))
    )
    (net (code "600") (name "unconnected-(J2-PadH24)") (class "Default")
      (node (ref "J2") (pin "H24") (pinfunction "H24_H24") (pintype "passive"))
    )
    (net (code "601") (name "unconnected-(J2-PadH25)") (class "Default")
      (node (ref "J2") (pin "H25") (pinfunction "H25_H25") (pintype "passive"))
    )
    (net (code "602") (name "unconnected-(J2-PadH26)") (class "Default")
      (node (ref "J2") (pin "H26") (pinfunction "H26_H26") (pintype "passive"))
    )
    (net (code "603") (name "unconnected-(J2-PadH27)") (class "Default")
      (node (ref "J2") (pin "H27") (pinfunction "H27_H27") (pintype "passive"))
    )
    (net (code "604") (name "unconnected-(J2-PadH28)") (class "Default")
      (node (ref "J2") (pin "H28") (pinfunction "H28_H28") (pintype "passive"))
    )
    (net (code "605") (name "unconnected-(J2-PadH29)") (class "Default")
      (node (ref "J2") (pin "H29") (pinfunction "H29_H29") (pintype "passive"))
    )
    (net (code "606") (name "unconnected-(J2-PadH30)") (class "Default")
      (node (ref "J2") (pin "H30") (pinfunction "H30_H30") (pintype "passive"))
    )
    (net (code "607") (name "unconnected-(J2-PadH31)") (class "Default")
      (node (ref "J2") (pin "H31") (pinfunction "H31_H31") (pintype "passive"))
    )
    (net (code "608") (name "unconnected-(J2-PadH32)") (class "Default")
      (node (ref "J2") (pin "H32") (pinfunction "H32_H32") (pintype "passive"))
    )
    (net (code "609") (name "unconnected-(J2-PadH33)") (class "Default")
      (node (ref "J2") (pin "H33") (pinfunction "H33_H33") (pintype "passive"))
    )
    (net (code "610") (name "unconnected-(J2-PadH34)") (class "Default")
      (node (ref "J2") (pin "H34") (pinfunction "H34_H34") (pintype "passive"))
    )
    (net (code "611") (name "unconnected-(J2-PadH35)") (class "Default")
      (node (ref "J2") (pin "H35") (pinfunction "H35_H35") (pintype "passive"))
    )
    (net (code "612") (name "unconnected-(J2-PadH36)") (class "Default")
      (node (ref "J2") (pin "H36") (pinfunction "H36_H36") (pintype "passive"))
    )
    (net (code "613") (name "unconnected-(J2-PadH37)") (class "Default")
      (node (ref "J2") (pin "H37") (pinfunction "H37_H37") (pintype "passive"))
    )
    (net (code "614") (name "unconnected-(J2-PadH38)") (class "Default")
      (node (ref "J2") (pin "H38") (pinfunction "H38_H38") (pintype "passive"))
    )
    (net (code "615") (name "unconnected-(J2-PadH39)") (class "Default")
      (node (ref "J2") (pin "H39") (pinfunction "H39_H39") (pintype "passive"))
    )
    (net (code "616") (name "unconnected-(J2-PadH40)") (class "Default")
      (node (ref "J2") (pin "H40") (pinfunction "H40_H40") (pintype "passive"))
    )
    (net (code "617") (name "unconnected-(N1-Pad0)") (class "Default")
      (node (ref "N1") (pin "0") (pinfunction "0_0") (pintype "passive"))
    )
    (net (code "618") (name "unconnected-(SV2-Pad10)") (class "Default")
      (node (ref "SV2") (pin "10") (pinfunction "10_10") (pintype "passive"))
    )
    (net (code "619") (name "unconnected-(SV6-Pad3)") (class "Default")
      (node (ref "SV6") (pin "3") (pinfunction "3_3") (pintype "passive"))
    )
    (net (code "620") (name "unconnected-(SV6-Pad4)") (class "Default")
      (node (ref "SV6") (pin "4") (pinfunction "4_4") (pintype "passive"))
    )
    (net (code "621") (name "unconnected-(U$1-PadA1)") (class "Default")
      (node (ref "U$1") (pin "A1") (pinfunction "A1_A1") (pintype "passive"))
    )
    (net (code "622") (name "unconnected-(U$1-PadA2)") (class "Default")
      (node (ref "U$1") (pin "A2") (pinfunction "A2_A2") (pintype "passive"))
    )
    (net (code "623") (name "unconnected-(U$1-PadA3)") (class "Default")
      (node (ref "U$1") (pin "A3") (pinfunction "A3_A3") (pintype "passive"))
    )
    (net (code "624") (name "unconnected-(U$1-PadA4)") (class "Default")
      (node (ref "U$1") (pin "A4") (pinfunction "A4_A4") (pintype "passive"))
    )
    (net (code "625") (name "unconnected-(U$1-PadA5)") (class "Default")
      (node (ref "U$1") (pin "A5") (pinfunction "A5_A5") (pintype "passive"))
    )
    (net (code "626") (name "unconnected-(U$1-PadA6)") (class "Default")
      (node (ref "U$1") (pin "A6") (pinfunction "A6_A6") (pintype "passive"))
    )
    (net (code "627") (name "unconnected-(U$1-PadA56)") (class "Default")
      (node (ref "U$1") (pin "A56") (pinfunction "A56_A56") (pintype "passive"))
    )
    (net (code "628") (name "unconnected-(U$1-PadA57)") (class "Default")
      (node (ref "U$1") (pin "A57") (pinfunction "A57_A57") (pintype "passive"))
    )
    (net (code "629") (name "unconnected-(U$1-PadA58)") (class "Default")
      (node (ref "U$1") (pin "A58") (pinfunction "A58_A58") (pintype "passive"))
    )
    (net (code "630") (name "unconnected-(U$1-PadA60)") (class "Default")
      (node (ref "U$1") (pin "A60") (pinfunction "A60_A60") (pintype "passive"))
    )
    (net (code "631") (name "unconnected-(U$1-PadA61)") (class "Default")
      (node (ref "U$1") (pin "A61") (pinfunction "A61_A61") (pintype "passive"))
    )
    (net (code "632") (name "unconnected-(U$1-PadA62)") (class "Default")
      (node (ref "U$1") (pin "A62") (pinfunction "A62_A62") (pintype "passive"))
    )
    (net (code "633") (name "unconnected-(U$1-PadA64)") (class "Default")
      (node (ref "U$1") (pin "A64") (pinfunction "A64_A64") (pintype "passive"))
    )
    (net (code "634") (name "unconnected-(U$1-PadA65)") (class "Default")
      (node (ref "U$1") (pin "A65") (pinfunction "A65_A65") (pintype "passive"))
    )
    (net (code "635") (name "unconnected-(U$1-PadB1)") (class "Default")
      (node (ref "U$1") (pin "B1") (pinfunction "B1_B1") (pintype "passive"))
    )
    (net (code "636") (name "unconnected-(U$1-PadB2)") (class "Default")
      (node (ref "U$1") (pin "B2") (pinfunction "B2_B2") (pintype "passive"))
    )
    (net (code "637") (name "unconnected-(U$1-PadB3)") (class "Default")
      (node (ref "U$1") (pin "B3") (pinfunction "B3_B3") (pintype "passive"))
    )
    (net (code "638") (name "unconnected-(U$1-PadB4)") (class "Default")
      (node (ref "U$1") (pin "B4") (pinfunction "B4_B4") (pintype "passive"))
    )
    (net (code "639") (name "unconnected-(U$1-PadB5)") (class "Default")
      (node (ref "U$1") (pin "B5") (pinfunction "B5_B5") (pintype "passive"))
    )
    (net (code "640") (name "unconnected-(U$1-PadB6)") (class "Default")
      (node (ref "U$1") (pin "B6") (pinfunction "B6_B6") (pintype "passive"))
    )
    (net (code "641") (name "unconnected-(U$1-PadB56)") (class "Default")
      (node (ref "U$1") (pin "B56") (pinfunction "B56_B56") (pintype "passive"))
    )
    (net (code "642") (name "unconnected-(U$1-PadB57)") (class "Default")
      (node (ref "U$1") (pin "B57") (pinfunction "B57_B57") (pintype "passive"))
    )
    (net (code "643") (name "unconnected-(U$1-PadB58)") (class "Default")
      (node (ref "U$1") (pin "B58") (pinfunction "B58_B58") (pintype "passive"))
    )
    (net (code "644") (name "unconnected-(U$1-PadB60)") (class "Default")
      (node (ref "U$1") (pin "B60") (pinfunction "B60_B60") (pintype "passive"))
    )
    (net (code "645") (name "unconnected-(U$1-PadB61)") (class "Default")
      (node (ref "U$1") (pin "B61") (pinfunction "B61_B61") (pintype "passive"))
    )
    (net (code "646") (name "unconnected-(U$1-PadB62)") (class "Default")
      (node (ref "U$1") (pin "B62") (pinfunction "B62_B62") (pintype "passive"))
    )
    (net (code "647") (name "unconnected-(U$1-PadB64)") (class "Default")
      (node (ref "U$1") (pin "B64") (pinfunction "B64_B64") (pintype "passive"))
    )
    (net (code "648") (name "unconnected-(U$1-PadB65)") (class "Default")
      (node (ref "U$1") (pin "B65") (pinfunction "B65_B65") (pintype "passive"))
    )
    (net (code "649") (name "unconnected-(U$1-PadC1)") (class "Default")
      (node (ref "U$1") (pin "C1") (pinfunction "C1_C1") (pintype "passive"))
    )
    (net (code "650") (name "unconnected-(U$1-PadC2)") (class "Default")
      (node (ref "U$1") (pin "C2") (pinfunction "C2_C2") (pintype "passive"))
    )
    (net (code "651") (name "unconnected-(U$1-PadC3)") (class "Default")
      (node (ref "U$1") (pin "C3") (pinfunction "C3_C3") (pintype "passive"))
    )
    (net (code "652") (name "unconnected-(U$1-PadC4)") (class "Default")
      (node (ref "U$1") (pin "C4") (pinfunction "C4_C4") (pintype "passive"))
    )
    (net (code "653") (name "unconnected-(U$1-PadC5)") (class "Default")
      (node (ref "U$1") (pin "C5") (pinfunction "C5_C5") (pintype "passive"))
    )
    (net (code "654") (name "unconnected-(U$1-PadC6)") (class "Default")
      (node (ref "U$1") (pin "C6") (pinfunction "C6_C6") (pintype "passive"))
    )
    (net (code "655") (name "unconnected-(U$1-PadC56)") (class "Default")
      (node (ref "U$1") (pin "C56") (pinfunction "C56_C56") (pintype "passive"))
    )
    (net (code "656") (name "unconnected-(U$1-PadC57)") (class "Default")
      (node (ref "U$1") (pin "C57") (pinfunction "C57_C57") (pintype "passive"))
    )
    (net (code "657") (name "unconnected-(U$1-PadC58)") (class "Default")
      (node (ref "U$1") (pin "C58") (pinfunction "C58_C58") (pintype "passive"))
    )
    (net (code "658") (name "unconnected-(U$1-PadC60)") (class "Default")
      (node (ref "U$1") (pin "C60") (pinfunction "C60_C60") (pintype "passive"))
    )
    (net (code "659") (name "unconnected-(U$1-PadC61)") (class "Default")
      (node (ref "U$1") (pin "C61") (pinfunction "C61_C61") (pintype "passive"))
    )
    (net (code "660") (name "unconnected-(U$1-PadC62)") (class "Default")
      (node (ref "U$1") (pin "C62") (pinfunction "C62_C62") (pintype "passive"))
    )
    (net (code "661") (name "unconnected-(U$1-PadC64)") (class "Default")
      (node (ref "U$1") (pin "C64") (pinfunction "C64_C64") (pintype "passive"))
    )
    (net (code "662") (name "unconnected-(U$1-PadC65)") (class "Default")
      (node (ref "U$1") (pin "C65") (pinfunction "C65_C65") (pintype "passive"))
    )
    (net (code "663") (name "unconnected-(U$1-PadD1)") (class "Default")
      (node (ref "U$1") (pin "D1") (pinfunction "D1_D1") (pintype "passive"))
    )
    (net (code "664") (name "unconnected-(U$1-PadD2)") (class "Default")
      (node (ref "U$1") (pin "D2") (pinfunction "D2_D2") (pintype "passive"))
    )
    (net (code "665") (name "unconnected-(U$1-PadD3)") (class "Default")
      (node (ref "U$1") (pin "D3") (pinfunction "D3_D3") (pintype "passive"))
    )
    (net (code "666") (name "unconnected-(U$1-PadD4)") (class "Default")
      (node (ref "U$1") (pin "D4") (pinfunction "D4_D4") (pintype "passive"))
    )
    (net (code "667") (name "unconnected-(U$1-PadD5)") (class "Default")
      (node (ref "U$1") (pin "D5") (pinfunction "D5_D5") (pintype "passive"))
    )
    (net (code "668") (name "unconnected-(U$1-PadD6)") (class "Default")
      (node (ref "U$1") (pin "D6") (pinfunction "D6_D6") (pintype "passive"))
    )
    (net (code "669") (name "unconnected-(U$1-PadD56)") (class "Default")
      (node (ref "U$1") (pin "D56") (pinfunction "D56_D56") (pintype "passive"))
    )
    (net (code "670") (name "unconnected-(U$1-PadD57)") (class "Default")
      (node (ref "U$1") (pin "D57") (pinfunction "D57_D57") (pintype "passive"))
    )
    (net (code "671") (name "unconnected-(U$1-PadD58)") (class "Default")
      (node (ref "U$1") (pin "D58") (pinfunction "D58_D58") (pintype "passive"))
    )
    (net (code "672") (name "unconnected-(U$1-PadD60)") (class "Default")
      (node (ref "U$1") (pin "D60") (pinfunction "D60_D60") (pintype "passive"))
    )
    (net (code "673") (name "unconnected-(U$1-PadD61)") (class "Default")
      (node (ref "U$1") (pin "D61") (pinfunction "D61_D61") (pintype "passive"))
    )
    (net (code "674") (name "unconnected-(U$1-PadD62)") (class "Default")
      (node (ref "U$1") (pin "D62") (pinfunction "D62_D62") (pintype "passive"))
    )
    (net (code "675") (name "unconnected-(U$1-PadD64)") (class "Default")
      (node (ref "U$1") (pin "D64") (pinfunction "D64_D64") (pintype "passive"))
    )
    (net (code "676") (name "unconnected-(U$1-PadD65)") (class "Default")
      (node (ref "U$1") (pin "D65") (pinfunction "D65_D65") (pintype "passive"))
    )
    (net (code "677") (name "unconnected-(U1A-INB1-PadB16)") (class "Default")
      (node (ref "U1") (pin "B16") (pinfunction "INB1_B16") (pintype "passive"))
    )
    (net (code "678") (name "unconnected-(U1A-INB2-PadC16)") (class "Default")
      (node (ref "U1") (pin "C16") (pinfunction "INB2_C16") (pintype "passive"))
    )
    (net (code "679") (name "unconnected-(U1A-INB3-PadD16)") (class "Default")
      (node (ref "U1") (pin "D16") (pinfunction "INB3_D16") (pintype "passive"))
    )
    (net (code "680") (name "unconnected-(U1A-INB4-PadE16)") (class "Default")
      (node (ref "U1") (pin "E16") (pinfunction "INB4_E16") (pintype "passive"))
    )
    (net (code "681") (name "unconnected-(U1A-INB5-PadH16)") (class "Default")
      (node (ref "U1") (pin "H16") (pinfunction "INB5_H16") (pintype "passive"))
    )
    (net (code "682") (name "unconnected-(U1A-INB6-PadJ16)") (class "Default")
      (node (ref "U1") (pin "J16") (pinfunction "INB6_J16") (pintype "passive"))
    )
    (net (code "683") (name "unconnected-(U1A-INB7-PadK16)") (class "Default")
      (node (ref "U1") (pin "K16") (pinfunction "INB7_K16") (pintype "passive"))
    )
    (net (code "684") (name "unconnected-(U1A-INB8-PadL16)") (class "Default")
      (node (ref "U1") (pin "L16") (pinfunction "INB8_L16") (pintype "passive"))
    )
    (net (code "685") (name "unconnected-(U1E-1_AG-PadF18)") (class "Default")
      (node (ref "U1") (pin "F18") (pinfunction "1_AG_F18") (pintype "passive"))
    )
    (net (code "686") (name "unconnected-(U1E-2_AG-PadG18)") (class "Default")
      (node (ref "U1") (pin "G18") (pinfunction "2_AG_G18") (pintype "passive"))
    )
    (net (code "687") (name "unconnected-(U1E-I.C.-PadB25)") (class "Default")
      (node (ref "U1") (pin "B25") (pinfunction "I.C._B25") (pintype "passive"))
    )
    (net (code "688") (name "unconnected-(U1E-N.C.-PadA24)") (class "Default")
      (node (ref "U1") (pin "A24") (pinfunction "N.C._A24") (pintype "passive"))
    )
    (net (code "689") (name "unconnected-(U2-IC-Pad8)") (class "Default")
      (node (ref "U2") (pin "8") (pinfunction "IC_8") (pintype "passive"))
    )
    (net (code "690") (name "unconnected-(U2-IC_2-Pad1)") (class "Default")
      (node (ref "U2") (pin "1") (pinfunction "IC_2_1") (pintype "passive"))
    )
    (net (code "691") (name "unconnected-(U2-IC_3-Pad7)") (class "Default")
      (node (ref "U2") (pin "7") (pinfunction "IC_3_7") (pintype "passive"))
    )
    (net (code "692") (name "unconnected-(U2-NR-Pad3)") (class "Default")
      (node (ref "U2") (pin "3") (pinfunction "NR_3") (pintype "passive"))
    )
    (net (code "693") (name "unconnected-(U2-TRIM-Pad5)") (class "Default")
      (node (ref "U2") (pin "5") (pinfunction "TRIM_5") (pintype "passive"))
    )
    (net (code "694") (name "unconnected-(U3-NC-Pad36)") (class "Default")
      (node (ref "U3") (pin "36") (pinfunction "NC_36") (pintype "passive"))
    )
    (net (code "695") (name "unconnected-(U3-NC_2-Pad1)") (class "Default")
      (node (ref "U3") (pin "1") (pinfunction "NC_2_1") (pintype "passive"))
    )
    (net (code "696") (name "unconnected-(U3-NC_3-Pad2)") (class "Default")
      (node (ref "U3") (pin "2") (pinfunction "NC_3_2") (pintype "passive"))
    )
    (net (code "697") (name "unconnected-(U3-NC_4-Pad14)") (class "Default")
      (node (ref "U3") (pin "14") (pinfunction "NC_4_14") (pintype "passive"))
    )
    (net (code "698") (name "unconnected-(U3-NC_5-Pad16)") (class "Default")
      (node (ref "U3") (pin "16") (pinfunction "NC_5_16") (pintype "power_in"))
    )
    (net (code "699") (name "unconnected-(U3-NC_6-Pad24)") (class "Default")
      (node (ref "U3") (pin "24") (pinfunction "NC_6_24") (pintype "passive"))
    )
    (net (code "700") (name "unconnected-(U3-NC_7-Pad35)") (class "Default")
      (node (ref "U3") (pin "35") (pinfunction "NC_7_35") (pintype "passive"))
    )
    (net (code "701") (name "unconnected-(U4-NC-Pad36)") (class "Default")
      (node (ref "U4") (pin "36") (pinfunction "NC_36") (pintype "passive"))
    )
    (net (code "702") (name "unconnected-(U4-NC_2-Pad1)") (class "Default")
      (node (ref "U4") (pin "1") (pinfunction "NC_2_1") (pintype "passive"))
    )
    (net (code "703") (name "unconnected-(U4-NC_3-Pad2)") (class "Default")
      (node (ref "U4") (pin "2") (pinfunction "NC_3_2") (pintype "passive"))
    )
    (net (code "704") (name "unconnected-(U4-NC_4-Pad14)") (class "Default")
      (node (ref "U4") (pin "14") (pinfunction "NC_4_14") (pintype "passive"))
    )
    (net (code "705") (name "unconnected-(U4-NC_5-Pad16)") (class "Default")
      (node (ref "U4") (pin "16") (pinfunction "NC_5_16") (pintype "power_in"))
    )
    (net (code "706") (name "unconnected-(U4-NC_6-Pad24)") (class "Default")
      (node (ref "U4") (pin "24") (pinfunction "NC_6_24") (pintype "passive"))
    )
    (net (code "707") (name "unconnected-(U4-NC_7-Pad35)") (class "Default")
      (node (ref "U4") (pin "35") (pinfunction "NC_7_35") (pintype "passive"))
    )
    (net (code "708") (name "unconnected-(U5-NC-Pad36)") (class "Default")
      (node (ref "U5") (pin "36") (pinfunction "NC_36") (pintype "passive"))
    )
    (net (code "709") (name "unconnected-(U5-NC_2-Pad1)") (class "Default")
      (node (ref "U5") (pin "1") (pinfunction "NC_2_1") (pintype "passive"))
    )
    (net (code "710") (name "unconnected-(U5-NC_3-Pad2)") (class "Default")
      (node (ref "U5") (pin "2") (pinfunction "NC_3_2") (pintype "passive"))
    )
    (net (code "711") (name "unconnected-(U5-NC_4-Pad14)") (class "Default")
      (node (ref "U5") (pin "14") (pinfunction "NC_4_14") (pintype "passive"))
    )
    (net (code "712") (name "unconnected-(U5-NC_5-Pad16)") (class "Default")
      (node (ref "U5") (pin "16") (pinfunction "NC_5_16") (pintype "power_in"))
    )
    (net (code "713") (name "unconnected-(U5-NC_6-Pad24)") (class "Default")
      (node (ref "U5") (pin "24") (pinfunction "NC_6_24") (pintype "passive"))
    )
    (net (code "714") (name "unconnected-(U5-NC_7-Pad35)") (class "Default")
      (node (ref "U5") (pin "35") (pinfunction "NC_7_35") (pintype "passive"))
    )
    (net (code "715") (name "unconnected-(U6-NC-Pad36)") (class "Default")
      (node (ref "U6") (pin "36") (pinfunction "NC_36") (pintype "passive"))
    )
    (net (code "716") (name "unconnected-(U6-NC_2-Pad1)") (class "Default")
      (node (ref "U6") (pin "1") (pinfunction "NC_2_1") (pintype "passive"))
    )
    (net (code "717") (name "unconnected-(U6-NC_3-Pad2)") (class "Default")
      (node (ref "U6") (pin "2") (pinfunction "NC_3_2") (pintype "passive"))
    )
    (net (code "718") (name "unconnected-(U6-NC_4-Pad14)") (class "Default")
      (node (ref "U6") (pin "14") (pinfunction "NC_4_14") (pintype "passive"))
    )
    (net (code "719") (name "unconnected-(U6-NC_5-Pad16)") (class "Default")
      (node (ref "U6") (pin "16") (pinfunction "NC_5_16") (pintype "power_in"))
    )
    (net (code "720") (name "unconnected-(U6-NC_6-Pad24)") (class "Default")
      (node (ref "U6") (pin "24") (pinfunction "NC_6_24") (pintype "passive"))
    )
    (net (code "721") (name "unconnected-(U6-NC_7-Pad35)") (class "Default")
      (node (ref "U6") (pin "35") (pinfunction "NC_7_35") (pintype "passive"))
    )
    (net (code "722") (name "unconnected-(U7-NC-Pad36)") (class "Default")
      (node (ref "U7") (pin "36") (pinfunction "NC_36") (pintype "passive"))
    )
    (net (code "723") (name "unconnected-(U7-NC_2-Pad1)") (class "Default")
      (node (ref "U7") (pin "1") (pinfunction "NC_2_1") (pintype "passive"))
    )
    (net (code "724") (name "unconnected-(U7-NC_3-Pad2)") (class "Default")
      (node (ref "U7") (pin "2") (pinfunction "NC_3_2") (pintype "passive"))
    )
    (net (code "725") (name "unconnected-(U7-NC_4-Pad14)") (class "Default")
      (node (ref "U7") (pin "14") (pinfunction "NC_4_14") (pintype "passive"))
    )
    (net (code "726") (name "unconnected-(U7-NC_5-Pad16)") (class "Default")
      (node (ref "U7") (pin "16") (pinfunction "NC_5_16") (pintype "power_in"))
    )
    (net (code "727") (name "unconnected-(U7-NC_6-Pad24)") (class "Default")
      (node (ref "U7") (pin "24") (pinfunction "NC_6_24") (pintype "passive"))
    )
    (net (code "728") (name "unconnected-(U7-NC_7-Pad35)") (class "Default")
      (node (ref "U7") (pin "35") (pinfunction "NC_7_35") (pintype "passive"))
    )
    (net (code "729") (name "unconnected-(U8-NC-Pad36)") (class "Default")
      (node (ref "U8") (pin "36") (pinfunction "NC_36") (pintype "passive"))
    )
    (net (code "730") (name "unconnected-(U8-NC_2-Pad1)") (class "Default")
      (node (ref "U8") (pin "1") (pinfunction "NC_2_1") (pintype "passive"))
    )
    (net (code "731") (name "unconnected-(U8-NC_3-Pad2)") (class "Default")
      (node (ref "U8") (pin "2") (pinfunction "NC_3_2") (pintype "passive"))
    )
    (net (code "732") (name "unconnected-(U8-NC_4-Pad14)") (class "Default")
      (node (ref "U8") (pin "14") (pinfunction "NC_4_14") (pintype "passive"))
    )
    (net (code "733") (name "unconnected-(U8-NC_5-Pad16)") (class "Default")
      (node (ref "U8") (pin "16") (pinfunction "NC_5_16") (pintype "power_in"))
    )
    (net (code "734") (name "unconnected-(U8-NC_6-Pad24)") (class "Default")
      (node (ref "U8") (pin "24") (pinfunction "NC_6_24") (pintype "passive"))
    )
    (net (code "735") (name "unconnected-(U8-NC_7-Pad35)") (class "Default")
      (node (ref "U8") (pin "35") (pinfunction "NC_7_35") (pintype "passive"))
    )
    (net (code "736") (name "unconnected-(U9-NC-Pad36)") (class "Default")
      (node (ref "U9") (pin "36") (pinfunction "NC_36") (pintype "passive"))
    )
    (net (code "737") (name "unconnected-(U9-NC_2-Pad1)") (class "Default")
      (node (ref "U9") (pin "1") (pinfunction "NC_2_1") (pintype "passive"))
    )
    (net (code "738") (name "unconnected-(U9-NC_3-Pad2)") (class "Default")
      (node (ref "U9") (pin "2") (pinfunction "NC_3_2") (pintype "passive"))
    )
    (net (code "739") (name "unconnected-(U9-NC_4-Pad14)") (class "Default")
      (node (ref "U9") (pin "14") (pinfunction "NC_4_14") (pintype "passive"))
    )
    (net (code "740") (name "unconnected-(U9-NC_5-Pad16)") (class "Default")
      (node (ref "U9") (pin "16") (pinfunction "NC_5_16") (pintype "power_in"))
    )
    (net (code "741") (name "unconnected-(U9-NC_6-Pad24)") (class "Default")
      (node (ref "U9") (pin "24") (pinfunction "NC_6_24") (pintype "passive"))
    )
    (net (code "742") (name "unconnected-(U9-NC_7-Pad35)") (class "Default")
      (node (ref "U9") (pin "35") (pinfunction "NC_7_35") (pintype "passive"))
    )
    (net (code "743") (name "unconnected-(U10-NC-Pad36)") (class "Default")
      (node (ref "U10") (pin "36") (pinfunction "NC_36") (pintype "passive"))
    )
    (net (code "744") (name "unconnected-(U10-NC_2-Pad1)") (class "Default")
      (node (ref "U10") (pin "1") (pinfunction "NC_2_1") (pintype "passive"))
    )
    (net (code "745") (name "unconnected-(U10-NC_3-Pad2)") (class "Default")
      (node (ref "U10") (pin "2") (pinfunction "NC_3_2") (pintype "passive"))
    )
    (net (code "746") (name "unconnected-(U10-NC_4-Pad14)") (class "Default")
      (node (ref "U10") (pin "14") (pinfunction "NC_4_14") (pintype "passive"))
    )
    (net (code "747") (name "unconnected-(U10-NC_5-Pad16)") (class "Default")
      (node (ref "U10") (pin "16") (pinfunction "NC_5_16") (pintype "power_in"))
    )
    (net (code "748") (name "unconnected-(U10-NC_6-Pad24)") (class "Default")
      (node (ref "U10") (pin "24") (pinfunction "NC_6_24") (pintype "passive"))
    )
    (net (code "749") (name "unconnected-(U10-NC_7-Pad35)") (class "Default")
      (node (ref "U10") (pin "35") (pinfunction "NC_7_35") (pintype "passive"))
    )
    (net (code "750") (name "unconnected-(U19-LV-Pad6)") (class "Default")
      (node (ref "U19") (pin "6") (pinfunction "LV_6") (pintype "passive"))
    )
    (net (code "751") (name "unconnected-(U19-NC-Pad1)") (class "Default")
      (node (ref "U19") (pin "1") (pinfunction "NC_1") (pintype "passive"))
    )
    (net (code "752") (name "unconnected-(U19-OSC-Pad7)") (class "Default")
      (node (ref "U19") (pin "7") (pinfunction "OSC_7") (pintype "passive"))
    )
  )
)
